# automatrix.net
KiCad netlist of a schematic drawn in EAGLE
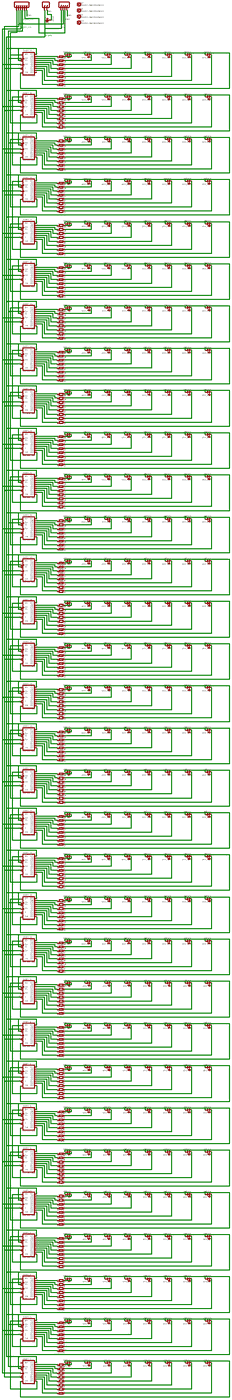
[diagram p0: schematic, sheet 1, overview]
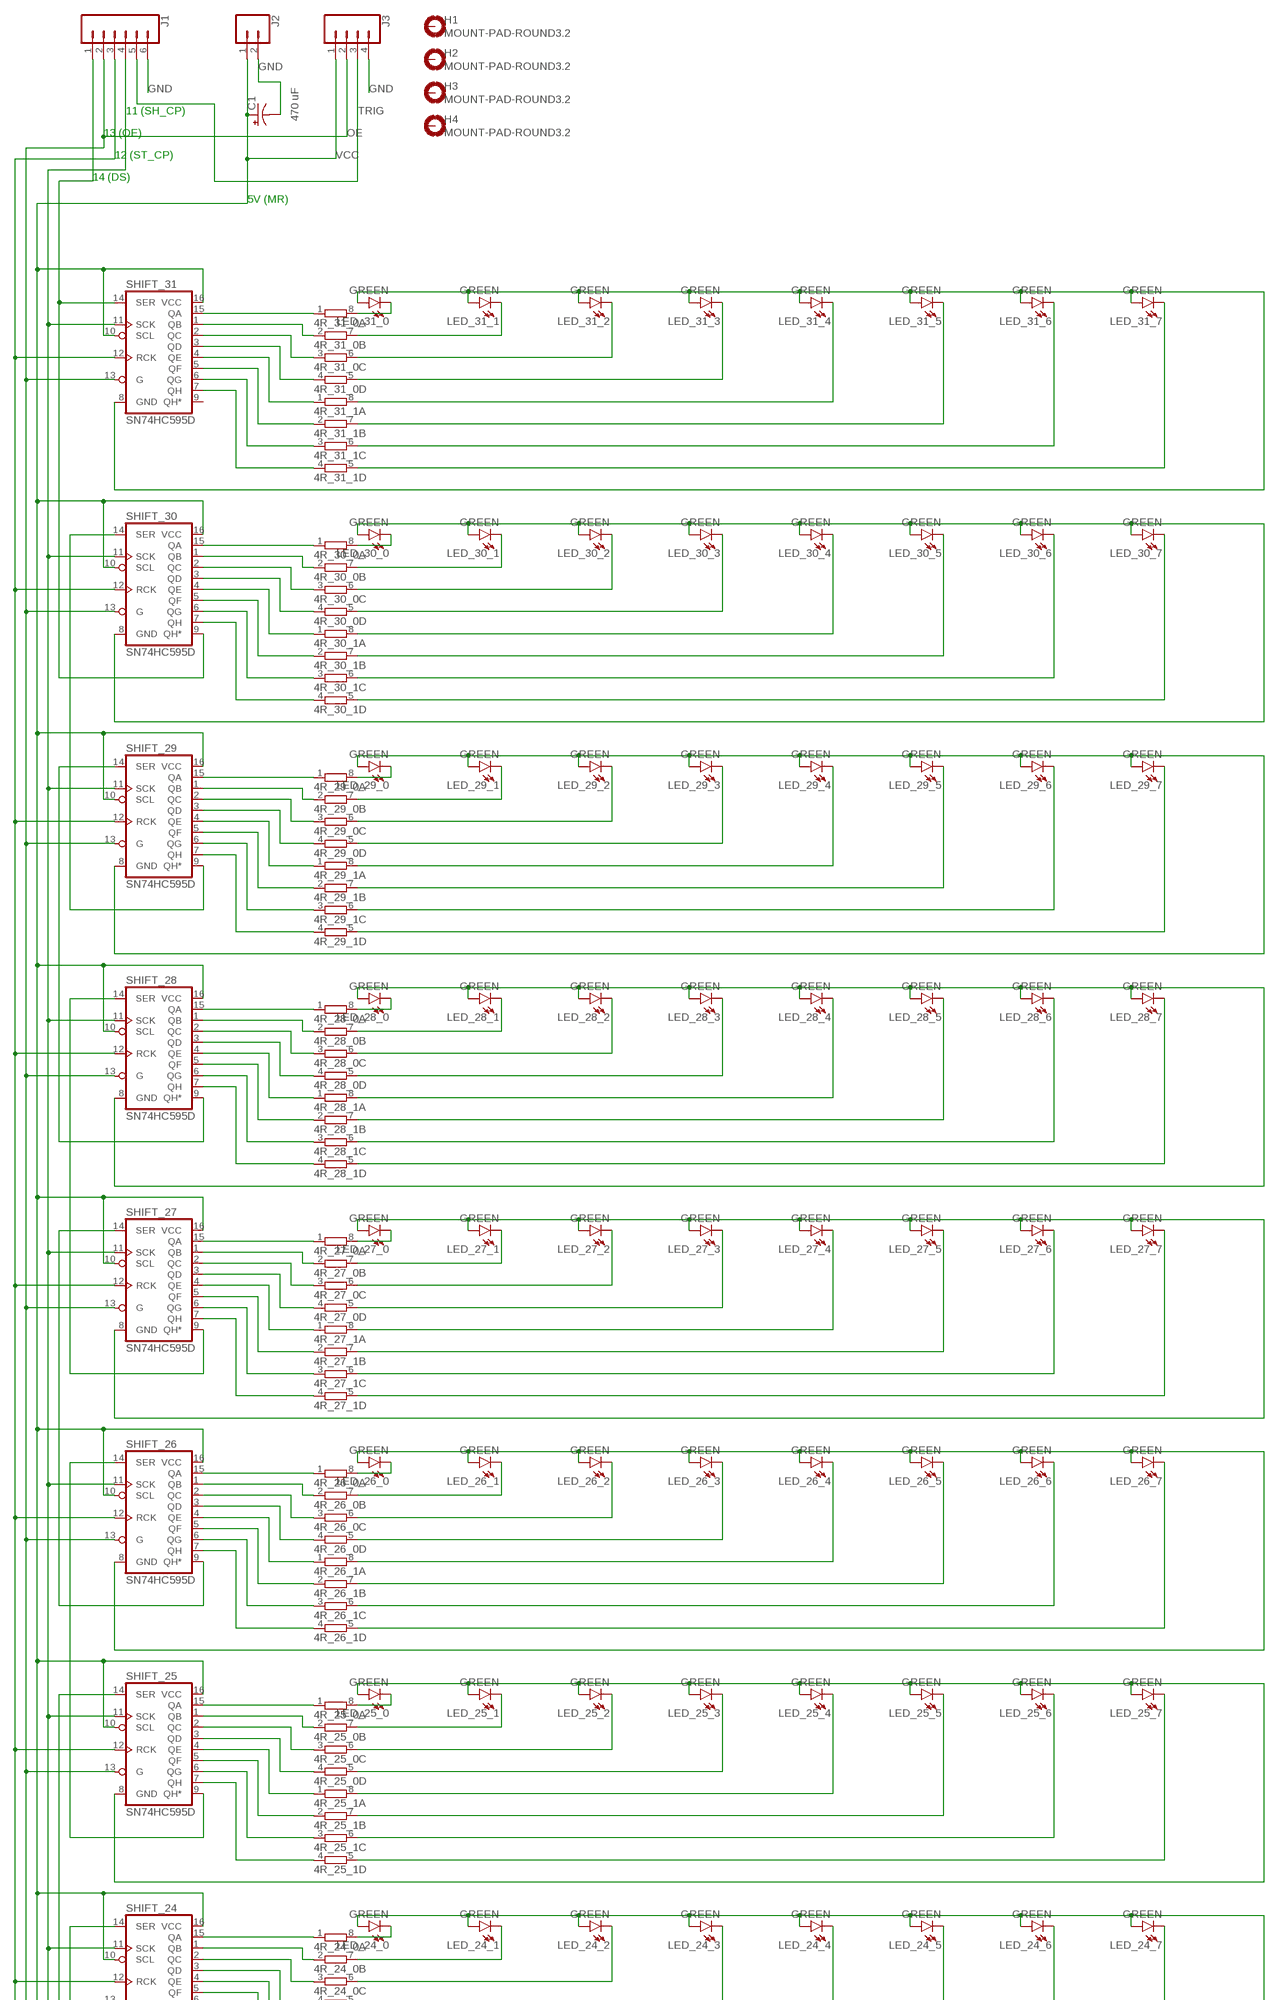
[diagram p1: schematic, sheet 1, part 1 of 4]
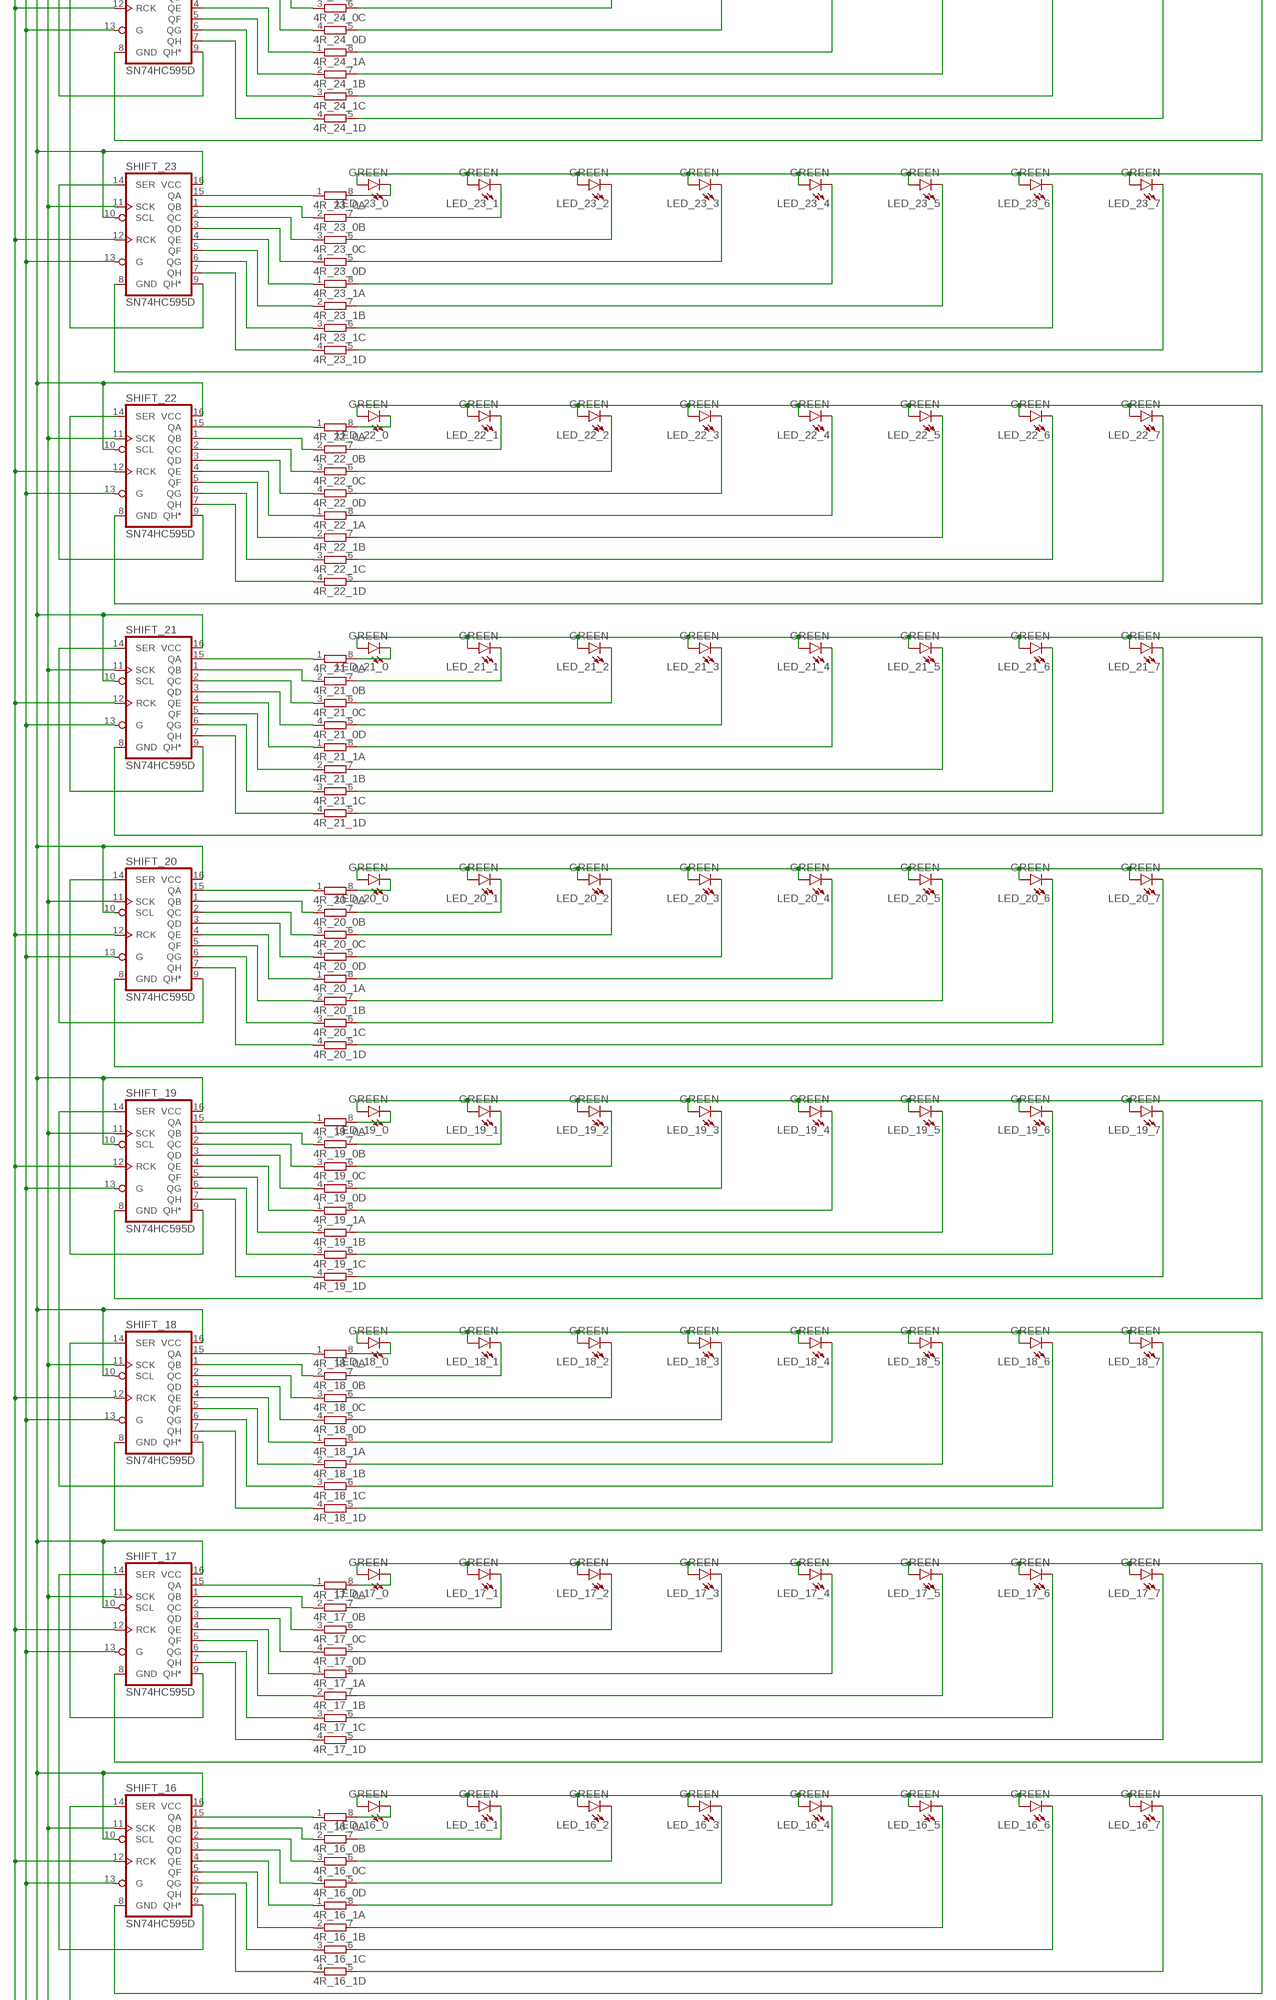
[diagram p2: schematic, sheet 1, part 2 of 4]
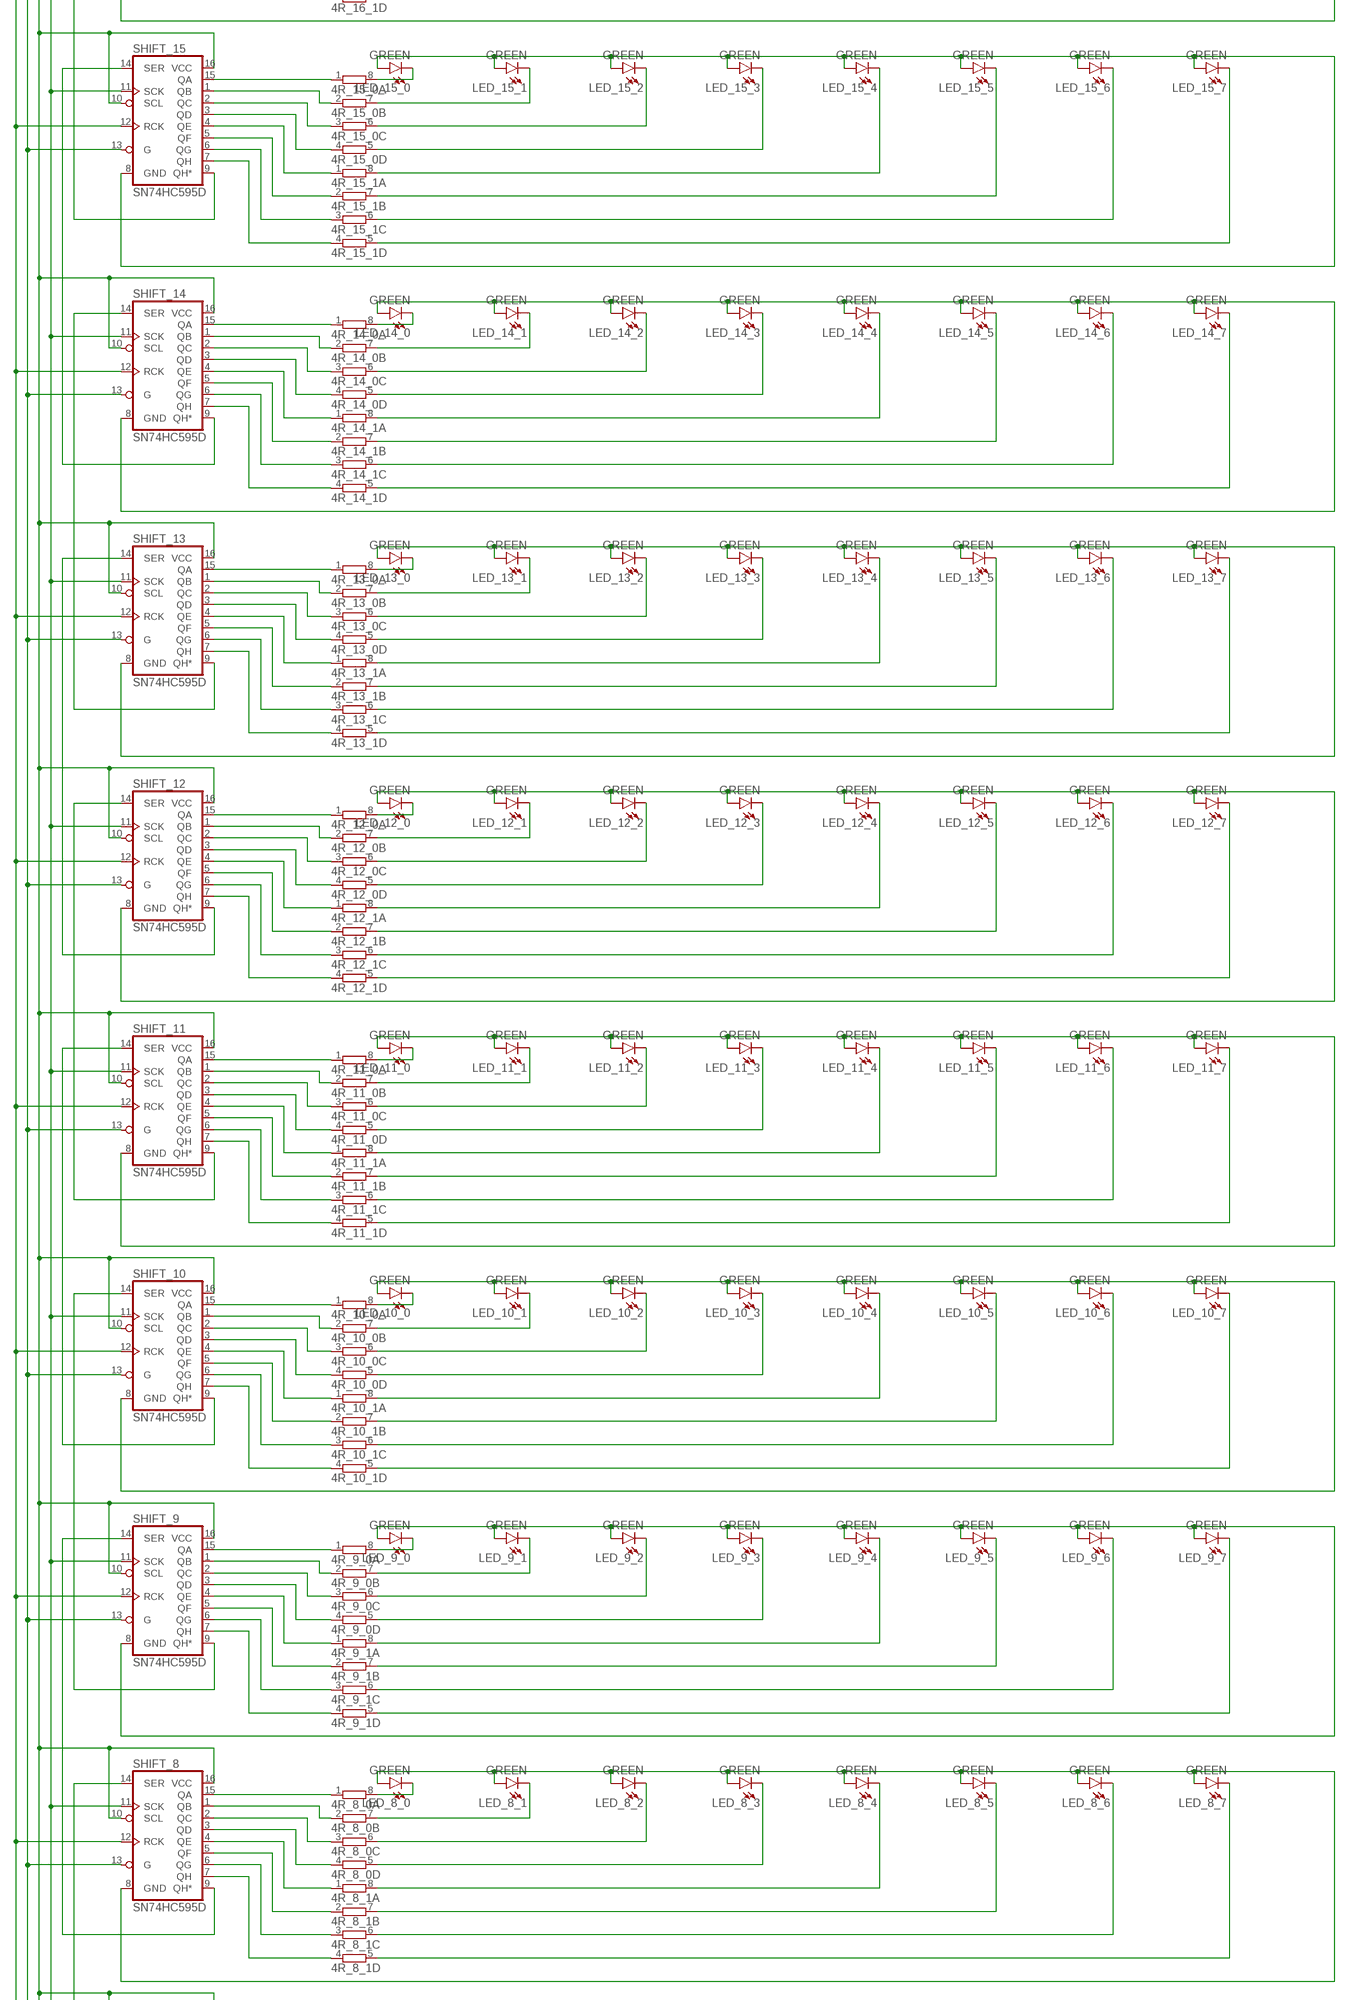
[diagram p3: schematic, sheet 1, part 3 of 4]
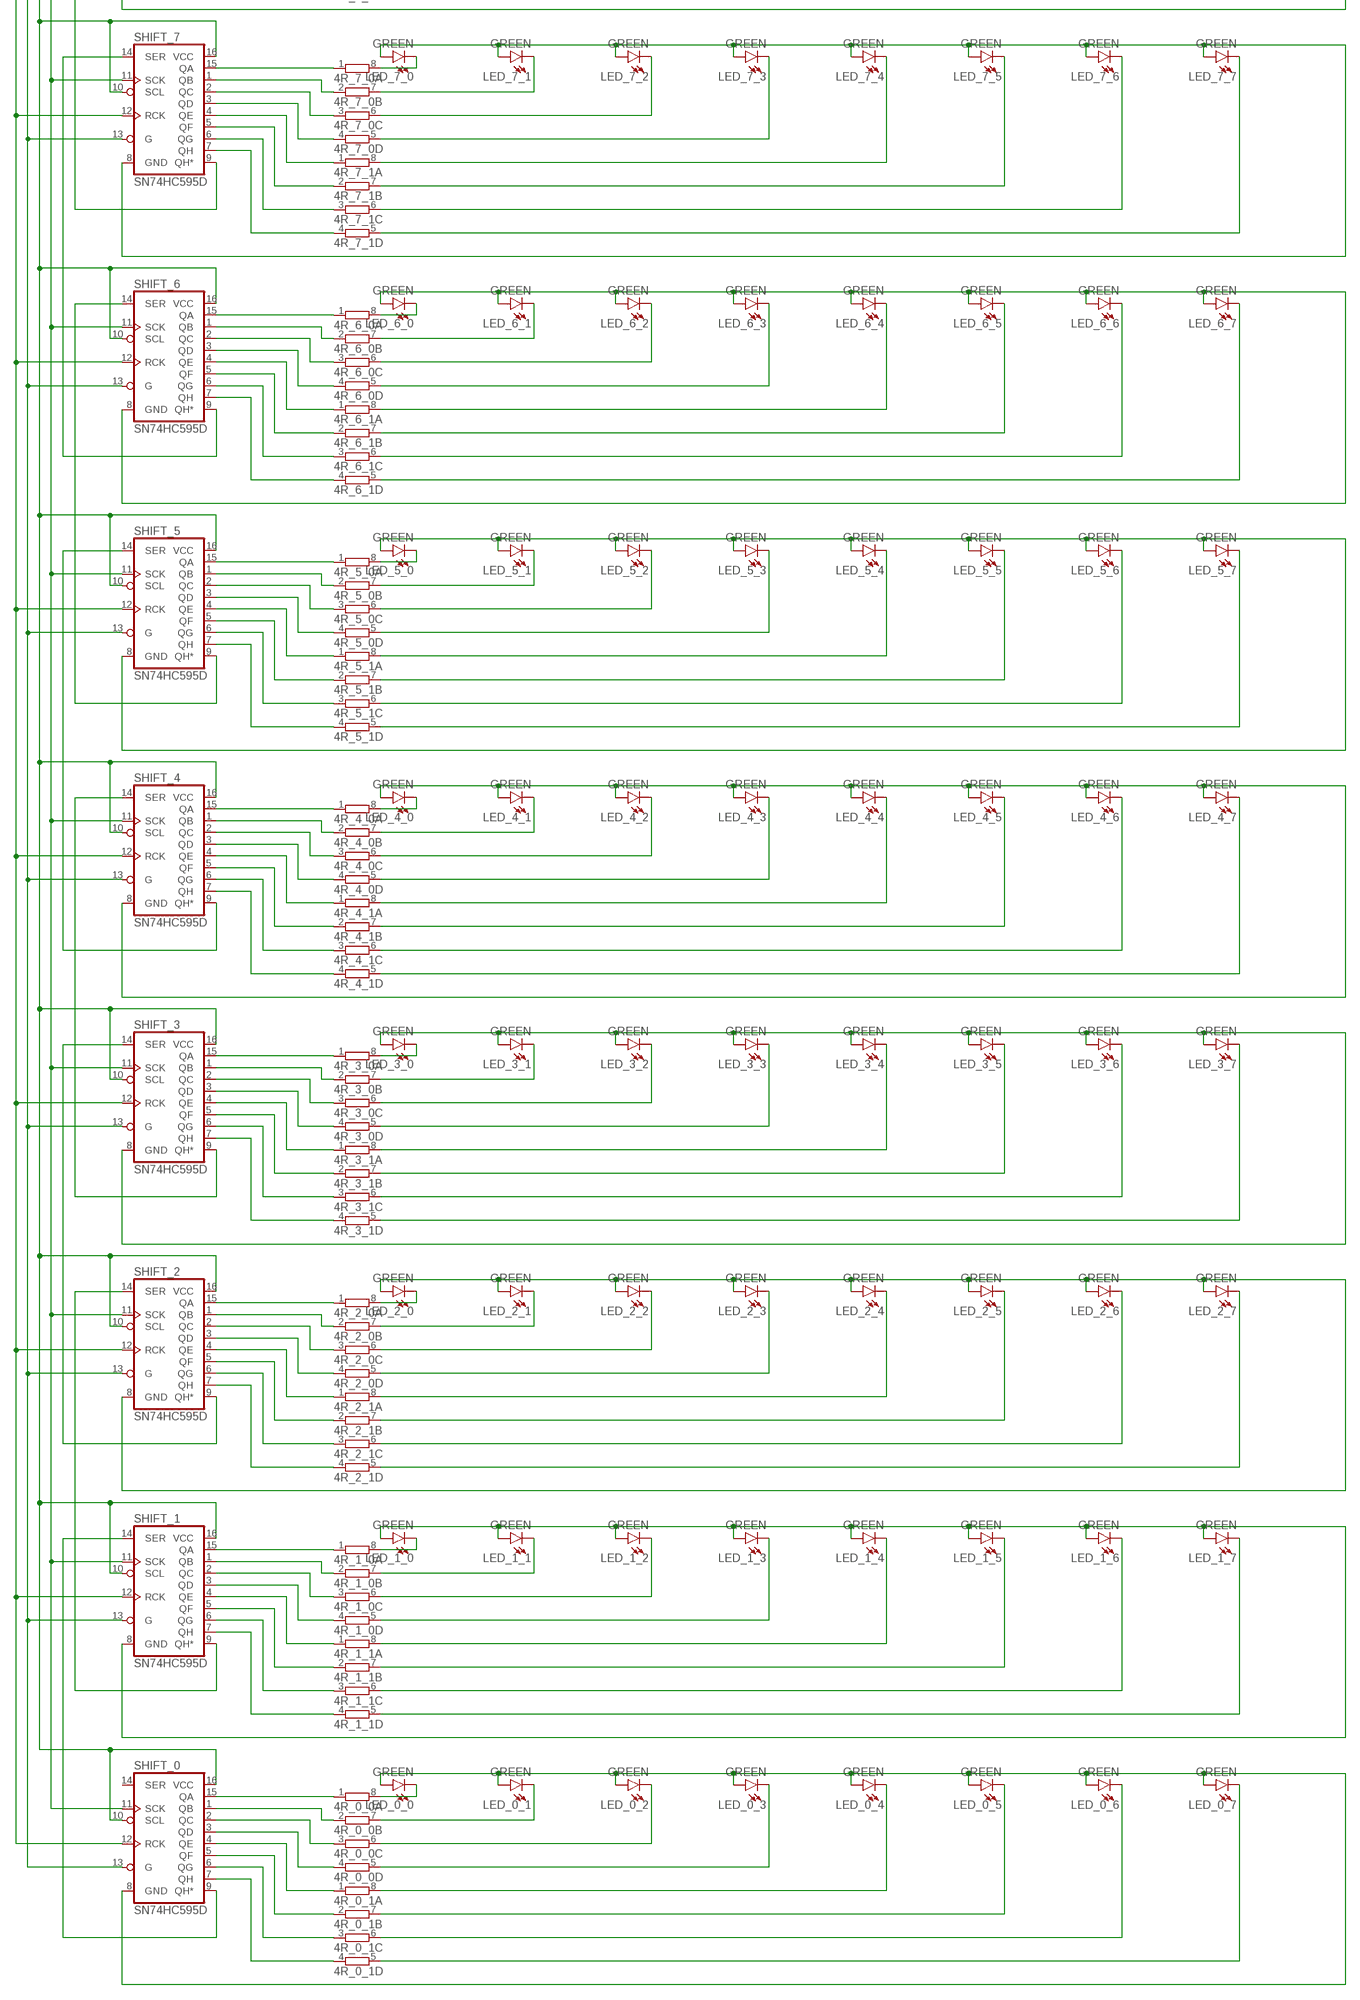
[diagram p4: schematic, sheet 1, part 4 of 4]

(export (version "E")
  (design (tool "Eeschema 10.0.6"))
  (components
    (comp (ref "4R_0_0")
      (value "4R-N0603-ARC")
      (footprint "eagle-import:0603-ARC")
      (libsource (lib "eagle-import") (part "4R-N0603-ARC"))
    )
    (comp (ref "4R_0_1")
      (value "4R-N0603-ARC")
      (footprint "eagle-import:0603-ARC")
      (libsource (lib "eagle-import") (part "4R-N0603-ARC"))
    )
    (comp (ref "4R_1_0")
      (value "4R-N0603-ARC")
      (footprint "eagle-import:0603-ARC")
      (libsource (lib "eagle-import") (part "4R-N0603-ARC"))
    )
    (comp (ref "4R_1_1")
      (value "4R-N0603-ARC")
      (footprint "eagle-import:0603-ARC")
      (libsource (lib "eagle-import") (part "4R-N0603-ARC"))
    )
    (comp (ref "4R_2_0")
      (value "4R-N0603-ARC")
      (footprint "eagle-import:0603-ARC")
      (libsource (lib "eagle-import") (part "4R-N0603-ARC"))
    )
    (comp (ref "4R_2_1")
      (value "4R-N0603-ARC")
      (footprint "eagle-import:0603-ARC")
      (libsource (lib "eagle-import") (part "4R-N0603-ARC"))
    )
    (comp (ref "4R_3_0")
      (value "4R-N0603-ARC")
      (footprint "eagle-import:0603-ARC")
      (libsource (lib "eagle-import") (part "4R-N0603-ARC"))
    )
    (comp (ref "4R_3_1")
      (value "4R-N0603-ARC")
      (footprint "eagle-import:0603-ARC")
      (libsource (lib "eagle-import") (part "4R-N0603-ARC"))
    )
    (comp (ref "4R_4_0")
      (value "4R-N0603-ARC")
      (footprint "eagle-import:0603-ARC")
      (libsource (lib "eagle-import") (part "4R-N0603-ARC"))
    )
    (comp (ref "4R_4_1")
      (value "4R-N0603-ARC")
      (footprint "eagle-import:0603-ARC")
      (libsource (lib "eagle-import") (part "4R-N0603-ARC"))
    )
    (comp (ref "4R_5_0")
      (value "4R-N0603-ARC")
      (footprint "eagle-import:0603-ARC")
      (libsource (lib "eagle-import") (part "4R-N0603-ARC"))
    )
    (comp (ref "4R_5_1")
      (value "4R-N0603-ARC")
      (footprint "eagle-import:0603-ARC")
      (libsource (lib "eagle-import") (part "4R-N0603-ARC"))
    )
    (comp (ref "4R_6_0")
      (value "4R-N0603-ARC")
      (footprint "eagle-import:0603-ARC")
      (libsource (lib "eagle-import") (part "4R-N0603-ARC"))
    )
    (comp (ref "4R_6_1")
      (value "4R-N0603-ARC")
      (footprint "eagle-import:0603-ARC")
      (libsource (lib "eagle-import") (part "4R-N0603-ARC"))
    )
    (comp (ref "4R_7_0")
      (value "4R-N0603-ARC")
      (footprint "eagle-import:0603-ARC")
      (libsource (lib "eagle-import") (part "4R-N0603-ARC"))
    )
    (comp (ref "4R_7_1")
      (value "4R-N0603-ARC")
      (footprint "eagle-import:0603-ARC")
      (libsource (lib "eagle-import") (part "4R-N0603-ARC"))
    )
    (comp (ref "4R_8_0")
      (value "4R-N0603-ARC")
      (footprint "eagle-import:0603-ARC")
      (libsource (lib "eagle-import") (part "4R-N0603-ARC"))
    )
    (comp (ref "4R_8_1")
      (value "4R-N0603-ARC")
      (footprint "eagle-import:0603-ARC")
      (libsource (lib "eagle-import") (part "4R-N0603-ARC"))
    )
    (comp (ref "4R_9_0")
      (value "4R-N0603-ARC")
      (footprint "eagle-import:0603-ARC")
      (libsource (lib "eagle-import") (part "4R-N0603-ARC"))
    )
    (comp (ref "4R_9_1")
      (value "4R-N0603-ARC")
      (footprint "eagle-import:0603-ARC")
      (libsource (lib "eagle-import") (part "4R-N0603-ARC"))
    )
    (comp (ref "4R_10_0")
      (value "4R-N0603-ARC")
      (footprint "eagle-import:0603-ARC")
      (libsource (lib "eagle-import") (part "4R-N0603-ARC"))
    )
    (comp (ref "4R_10_1")
      (value "4R-N0603-ARC")
      (footprint "eagle-import:0603-ARC")
      (libsource (lib "eagle-import") (part "4R-N0603-ARC"))
    )
    (comp (ref "4R_11_0")
      (value "4R-N0603-ARC")
      (footprint "eagle-import:0603-ARC")
      (libsource (lib "eagle-import") (part "4R-N0603-ARC"))
    )
    (comp (ref "4R_11_1")
      (value "4R-N0603-ARC")
      (footprint "eagle-import:0603-ARC")
      (libsource (lib "eagle-import") (part "4R-N0603-ARC"))
    )
    (comp (ref "4R_12_0")
      (value "4R-N0603-ARC")
      (footprint "eagle-import:0603-ARC")
      (libsource (lib "eagle-import") (part "4R-N0603-ARC"))
    )
    (comp (ref "4R_12_1")
      (value "4R-N0603-ARC")
      (footprint "eagle-import:0603-ARC")
      (libsource (lib "eagle-import") (part "4R-N0603-ARC"))
    )
    (comp (ref "4R_13_0")
      (value "4R-N0603-ARC")
      (footprint "eagle-import:0603-ARC")
      (libsource (lib "eagle-import") (part "4R-N0603-ARC"))
    )
    (comp (ref "4R_13_1")
      (value "4R-N0603-ARC")
      (footprint "eagle-import:0603-ARC")
      (libsource (lib "eagle-import") (part "4R-N0603-ARC"))
    )
    (comp (ref "4R_14_0")
      (value "4R-N0603-ARC")
      (footprint "eagle-import:0603-ARC")
      (libsource (lib "eagle-import") (part "4R-N0603-ARC"))
    )
    (comp (ref "4R_14_1")
      (value "4R-N0603-ARC")
      (footprint "eagle-import:0603-ARC")
      (libsource (lib "eagle-import") (part "4R-N0603-ARC"))
    )
    (comp (ref "4R_15_0")
      (value "4R-N0603-ARC")
      (footprint "eagle-import:0603-ARC")
      (libsource (lib "eagle-import") (part "4R-N0603-ARC"))
    )
    (comp (ref "4R_15_1")
      (value "4R-N0603-ARC")
      (footprint "eagle-import:0603-ARC")
      (libsource (lib "eagle-import") (part "4R-N0603-ARC"))
    )
    (comp (ref "4R_16_0")
      (value "4R-N0603-ARC")
      (footprint "eagle-import:0603-ARC")
      (libsource (lib "eagle-import") (part "4R-N0603-ARC"))
    )
    (comp (ref "4R_16_1")
      (value "4R-N0603-ARC")
      (footprint "eagle-import:0603-ARC")
      (libsource (lib "eagle-import") (part "4R-N0603-ARC"))
    )
    (comp (ref "4R_17_0")
      (value "4R-N0603-ARC")
      (footprint "eagle-import:0603-ARC")
      (libsource (lib "eagle-import") (part "4R-N0603-ARC"))
    )
    (comp (ref "4R_17_1")
      (value "4R-N0603-ARC")
      (footprint "eagle-import:0603-ARC")
      (libsource (lib "eagle-import") (part "4R-N0603-ARC"))
    )
    (comp (ref "4R_18_0")
      (value "4R-N0603-ARC")
      (footprint "eagle-import:0603-ARC")
      (libsource (lib "eagle-import") (part "4R-N0603-ARC"))
    )
    (comp (ref "4R_18_1")
      (value "4R-N0603-ARC")
      (footprint "eagle-import:0603-ARC")
      (libsource (lib "eagle-import") (part "4R-N0603-ARC"))
    )
    (comp (ref "4R_19_0")
      (value "4R-N0603-ARC")
      (footprint "eagle-import:0603-ARC")
      (libsource (lib "eagle-import") (part "4R-N0603-ARC"))
    )
    (comp (ref "4R_19_1")
      (value "4R-N0603-ARC")
      (footprint "eagle-import:0603-ARC")
      (libsource (lib "eagle-import") (part "4R-N0603-ARC"))
    )
    (comp (ref "4R_20_0")
      (value "4R-N0603-ARC")
      (footprint "eagle-import:0603-ARC")
      (libsource (lib "eagle-import") (part "4R-N0603-ARC"))
    )
    (comp (ref "4R_20_1")
      (value "4R-N0603-ARC")
      (footprint "eagle-import:0603-ARC")
      (libsource (lib "eagle-import") (part "4R-N0603-ARC"))
    )
    (comp (ref "4R_21_0")
      (value "4R-N0603-ARC")
      (footprint "eagle-import:0603-ARC")
      (libsource (lib "eagle-import") (part "4R-N0603-ARC"))
    )
    (comp (ref "4R_21_1")
      (value "4R-N0603-ARC")
      (footprint "eagle-import:0603-ARC")
      (libsource (lib "eagle-import") (part "4R-N0603-ARC"))
    )
    (comp (ref "4R_22_0")
      (value "4R-N0603-ARC")
      (footprint "eagle-import:0603-ARC")
      (libsource (lib "eagle-import") (part "4R-N0603-ARC"))
    )
    (comp (ref "4R_22_1")
      (value "4R-N0603-ARC")
      (footprint "eagle-import:0603-ARC")
      (libsource (lib "eagle-import") (part "4R-N0603-ARC"))
    )
    (comp (ref "4R_23_0")
      (value "4R-N0603-ARC")
      (footprint "eagle-import:0603-ARC")
      (libsource (lib "eagle-import") (part "4R-N0603-ARC"))
    )
    (comp (ref "4R_23_1")
      (value "4R-N0603-ARC")
      (footprint "eagle-import:0603-ARC")
      (libsource (lib "eagle-import") (part "4R-N0603-ARC"))
    )
    (comp (ref "4R_24_0")
      (value "4R-N0603-ARC")
      (footprint "eagle-import:0603-ARC")
      (libsource (lib "eagle-import") (part "4R-N0603-ARC"))
    )
    (comp (ref "4R_24_1")
      (value "4R-N0603-ARC")
      (footprint "eagle-import:0603-ARC")
      (libsource (lib "eagle-import") (part "4R-N0603-ARC"))
    )
    (comp (ref "4R_25_0")
      (value "4R-N0603-ARC")
      (footprint "eagle-import:0603-ARC")
      (libsource (lib "eagle-import") (part "4R-N0603-ARC"))
    )
    (comp (ref "4R_25_1")
      (value "4R-N0603-ARC")
      (footprint "eagle-import:0603-ARC")
      (libsource (lib "eagle-import") (part "4R-N0603-ARC"))
    )
    (comp (ref "4R_26_0")
      (value "4R-N0603-ARC")
      (footprint "eagle-import:0603-ARC")
      (libsource (lib "eagle-import") (part "4R-N0603-ARC"))
    )
    (comp (ref "4R_26_1")
      (value "4R-N0603-ARC")
      (footprint "eagle-import:0603-ARC")
      (libsource (lib "eagle-import") (part "4R-N0603-ARC"))
    )
    (comp (ref "4R_27_0")
      (value "4R-N0603-ARC")
      (footprint "eagle-import:0603-ARC")
      (libsource (lib "eagle-import") (part "4R-N0603-ARC"))
    )
    (comp (ref "4R_27_1")
      (value "4R-N0603-ARC")
      (footprint "eagle-import:0603-ARC")
      (libsource (lib "eagle-import") (part "4R-N0603-ARC"))
    )
    (comp (ref "4R_28_0")
      (value "4R-N0603-ARC")
      (footprint "eagle-import:0603-ARC")
      (libsource (lib "eagle-import") (part "4R-N0603-ARC"))
    )
    (comp (ref "4R_28_1")
      (value "4R-N0603-ARC")
      (footprint "eagle-import:0603-ARC")
      (libsource (lib "eagle-import") (part "4R-N0603-ARC"))
    )
    (comp (ref "4R_29_0")
      (value "4R-N0603-ARC")
      (footprint "eagle-import:0603-ARC")
      (libsource (lib "eagle-import") (part "4R-N0603-ARC"))
    )
    (comp (ref "4R_29_1")
      (value "4R-N0603-ARC")
      (footprint "eagle-import:0603-ARC")
      (libsource (lib "eagle-import") (part "4R-N0603-ARC"))
    )
    (comp (ref "4R_30_0")
      (value "4R-N0603-ARC")
      (footprint "eagle-import:0603-ARC")
      (libsource (lib "eagle-import") (part "4R-N0603-ARC"))
    )
    (comp (ref "4R_30_1")
      (value "4R-N0603-ARC")
      (footprint "eagle-import:0603-ARC")
      (libsource (lib "eagle-import") (part "4R-N0603-ARC"))
    )
    (comp (ref "4R_31_0")
      (value "4R-N0603-ARC")
      (footprint "eagle-import:0603-ARC")
      (libsource (lib "eagle-import") (part "4R-N0603-ARC"))
    )
    (comp (ref "4R_31_1")
      (value "4R-N0603-ARC")
      (footprint "eagle-import:0603-ARC")
      (libsource (lib "eagle-import") (part "4R-N0603-ARC"))
    )
    (comp (ref "C1")
      (value "470 uF")
      (footprint "eagle-import:CPOL-RADIAL-5MM-10MM")
      (libsource (lib "eagle-import") (part "1000UF-RADIAL-5MM-25V-20%"))
    )
    (comp (ref "H1")
      (value "MOUNT-PAD-ROUND3.2")
      (footprint "eagle-import:3,2-PAD")
      (libsource (lib "eagle-import") (part "MOUNT-PAD-ROUND3.2"))
    )
    (comp (ref "H2")
      (value "MOUNT-PAD-ROUND3.2")
      (footprint "eagle-import:3,2-PAD")
      (libsource (lib "eagle-import") (part "MOUNT-PAD-ROUND3.2"))
    )
    (comp (ref "H3")
      (value "MOUNT-PAD-ROUND3.2")
      (footprint "eagle-import:3,2-PAD")
      (libsource (lib "eagle-import") (part "MOUNT-PAD-ROUND3.2"))
    )
    (comp (ref "H4")
      (value "MOUNT-PAD-ROUND3.2")
      (footprint "eagle-import:3,2-PAD")
      (libsource (lib "eagle-import") (part "MOUNT-PAD-ROUND3.2"))
    )
    (comp (ref "J1")
      (value "CONN_06NO_SILK_FEMALE_PTH")
      (footprint "eagle-import:1X06_NO_SILK")
      (libsource (lib "eagle-import") (part "CONN_06NO_SILK_FEMALE_PTH"))
    )
    (comp (ref "J2")
      (value "CONN_021X02_NO_SILK")
      (footprint "eagle-import:1X02_NO_SILK")
      (libsource (lib "eagle-import") (part "CONN_021X02_NO_SILK"))
    )
    (comp (ref "J3")
      (value "CONN_041X04_NO_SILK")
      (footprint "eagle-import:1X04_NO_SILK")
      (libsource (lib "eagle-import") (part "CONN_041X04_NO_SILK"))
    )
    (comp (ref "LED_0_0")
      (value "GREEN")
      (footprint "eagle-import:LED-0603")
      (libsource (lib "eagle-import") (part "LED-GREEN0603"))
    )
    (comp (ref "LED_0_1")
      (value "GREEN")
      (footprint "eagle-import:LED-0603")
      (libsource (lib "eagle-import") (part "LED-GREEN0603"))
    )
    (comp (ref "LED_0_2")
      (value "GREEN")
      (footprint "eagle-import:LED-0603")
      (libsource (lib "eagle-import") (part "LED-GREEN0603"))
    )
    (comp (ref "LED_0_3")
      (value "GREEN")
      (footprint "eagle-import:LED-0603")
      (libsource (lib "eagle-import") (part "LED-GREEN0603"))
    )
    (comp (ref "LED_0_4")
      (value "GREEN")
      (footprint "eagle-import:LED-0603")
      (libsource (lib "eagle-import") (part "LED-GREEN0603"))
    )
    (comp (ref "LED_0_5")
      (value "GREEN")
      (footprint "eagle-import:LED-0603")
      (libsource (lib "eagle-import") (part "LED-GREEN0603"))
    )
    (comp (ref "LED_0_6")
      (value "GREEN")
      (footprint "eagle-import:LED-0603")
      (libsource (lib "eagle-import") (part "LED-GREEN0603"))
    )
    (comp (ref "LED_0_7")
      (value "GREEN")
      (footprint "eagle-import:LED-0603")
      (libsource (lib "eagle-import") (part "LED-GREEN0603"))
    )
    (comp (ref "LED_1_0")
      (value "GREEN")
      (footprint "eagle-import:LED-0603")
      (libsource (lib "eagle-import") (part "LED-GREEN0603"))
    )
    (comp (ref "LED_1_1")
      (value "GREEN")
      (footprint "eagle-import:LED-0603")
      (libsource (lib "eagle-import") (part "LED-GREEN0603"))
    )
    (comp (ref "LED_1_2")
      (value "GREEN")
      (footprint "eagle-import:LED-0603")
      (libsource (lib "eagle-import") (part "LED-GREEN0603"))
    )
    (comp (ref "LED_1_3")
      (value "GREEN")
      (footprint "eagle-import:LED-0603")
      (libsource (lib "eagle-import") (part "LED-GREEN0603"))
    )
    (comp (ref "LED_1_4")
      (value "GREEN")
      (footprint "eagle-import:LED-0603")
      (libsource (lib "eagle-import") (part "LED-GREEN0603"))
    )
    (comp (ref "LED_1_5")
      (value "GREEN")
      (footprint "eagle-import:LED-0603")
      (libsource (lib "eagle-import") (part "LED-GREEN0603"))
    )
    (comp (ref "LED_1_6")
      (value "GREEN")
      (footprint "eagle-import:LED-0603")
      (libsource (lib "eagle-import") (part "LED-GREEN0603"))
    )
    (comp (ref "LED_1_7")
      (value "GREEN")
      (footprint "eagle-import:LED-0603")
      (libsource (lib "eagle-import") (part "LED-GREEN0603"))
    )
    (comp (ref "LED_2_0")
      (value "GREEN")
      (footprint "eagle-import:LED-0603")
      (libsource (lib "eagle-import") (part "LED-GREEN0603"))
    )
    (comp (ref "LED_2_1")
      (value "GREEN")
      (footprint "eagle-import:LED-0603")
      (libsource (lib "eagle-import") (part "LED-GREEN0603"))
    )
    (comp (ref "LED_2_2")
      (value "GREEN")
      (footprint "eagle-import:LED-0603")
      (libsource (lib "eagle-import") (part "LED-GREEN0603"))
    )
    (comp (ref "LED_2_3")
      (value "GREEN")
      (footprint "eagle-import:LED-0603")
      (libsource (lib "eagle-import") (part "LED-GREEN0603"))
    )
    (comp (ref "LED_2_4")
      (value "GREEN")
      (footprint "eagle-import:LED-0603")
      (libsource (lib "eagle-import") (part "LED-GREEN0603"))
    )
    (comp (ref "LED_2_5")
      (value "GREEN")
      (footprint "eagle-import:LED-0603")
      (libsource (lib "eagle-import") (part "LED-GREEN0603"))
    )
    (comp (ref "LED_2_6")
      (value "GREEN")
      (footprint "eagle-import:LED-0603")
      (libsource (lib "eagle-import") (part "LED-GREEN0603"))
    )
    (comp (ref "LED_2_7")
      (value "GREEN")
      (footprint "eagle-import:LED-0603")
      (libsource (lib "eagle-import") (part "LED-GREEN0603"))
    )
    (comp (ref "LED_3_0")
      (value "GREEN")
      (footprint "eagle-import:LED-0603")
      (libsource (lib "eagle-import") (part "LED-GREEN0603"))
    )
    (comp (ref "LED_3_1")
      (value "GREEN")
      (footprint "eagle-import:LED-0603")
      (libsource (lib "eagle-import") (part "LED-GREEN0603"))
    )
    (comp (ref "LED_3_2")
      (value "GREEN")
      (footprint "eagle-import:LED-0603")
      (libsource (lib "eagle-import") (part "LED-GREEN0603"))
    )
    (comp (ref "LED_3_3")
      (value "GREEN")
      (footprint "eagle-import:LED-0603")
      (libsource (lib "eagle-import") (part "LED-GREEN0603"))
    )
    (comp (ref "LED_3_4")
      (value "GREEN")
      (footprint "eagle-import:LED-0603")
      (libsource (lib "eagle-import") (part "LED-GREEN0603"))
    )
    (comp (ref "LED_3_5")
      (value "GREEN")
      (footprint "eagle-import:LED-0603")
      (libsource (lib "eagle-import") (part "LED-GREEN0603"))
    )
    (comp (ref "LED_3_6")
      (value "GREEN")
      (footprint "eagle-import:LED-0603")
      (libsource (lib "eagle-import") (part "LED-GREEN0603"))
    )
    (comp (ref "LED_3_7")
      (value "GREEN")
      (footprint "eagle-import:LED-0603")
      (libsource (lib "eagle-import") (part "LED-GREEN0603"))
    )
    (comp (ref "LED_4_0")
      (value "GREEN")
      (footprint "eagle-import:LED-0603")
      (libsource (lib "eagle-import") (part "LED-GREEN0603"))
    )
    (comp (ref "LED_4_1")
      (value "GREEN")
      (footprint "eagle-import:LED-0603")
      (libsource (lib "eagle-import") (part "LED-GREEN0603"))
    )
    (comp (ref "LED_4_2")
      (value "GREEN")
      (footprint "eagle-import:LED-0603")
      (libsource (lib "eagle-import") (part "LED-GREEN0603"))
    )
    (comp (ref "LED_4_3")
      (value "GREEN")
      (footprint "eagle-import:LED-0603")
      (libsource (lib "eagle-import") (part "LED-GREEN0603"))
    )
    (comp (ref "LED_4_4")
      (value "GREEN")
      (footprint "eagle-import:LED-0603")
      (libsource (lib "eagle-import") (part "LED-GREEN0603"))
    )
    (comp (ref "LED_4_5")
      (value "GREEN")
      (footprint "eagle-import:LED-0603")
      (libsource (lib "eagle-import") (part "LED-GREEN0603"))
    )
    (comp (ref "LED_4_6")
      (value "GREEN")
      (footprint "eagle-import:LED-0603")
      (libsource (lib "eagle-import") (part "LED-GREEN0603"))
    )
    (comp (ref "LED_4_7")
      (value "GREEN")
      (footprint "eagle-import:LED-0603")
      (libsource (lib "eagle-import") (part "LED-GREEN0603"))
    )
    (comp (ref "LED_5_0")
      (value "GREEN")
      (footprint "eagle-import:LED-0603")
      (libsource (lib "eagle-import") (part "LED-GREEN0603"))
    )
    (comp (ref "LED_5_1")
      (value "GREEN")
      (footprint "eagle-import:LED-0603")
      (libsource (lib "eagle-import") (part "LED-GREEN0603"))
    )
    (comp (ref "LED_5_2")
      (value "GREEN")
      (footprint "eagle-import:LED-0603")
      (libsource (lib "eagle-import") (part "LED-GREEN0603"))
    )
    (comp (ref "LED_5_3")
      (value "GREEN")
      (footprint "eagle-import:LED-0603")
      (libsource (lib "eagle-import") (part "LED-GREEN0603"))
    )
    (comp (ref "LED_5_4")
      (value "GREEN")
      (footprint "eagle-import:LED-0603")
      (libsource (lib "eagle-import") (part "LED-GREEN0603"))
    )
    (comp (ref "LED_5_5")
      (value "GREEN")
      (footprint "eagle-import:LED-0603")
      (libsource (lib "eagle-import") (part "LED-GREEN0603"))
    )
    (comp (ref "LED_5_6")
      (value "GREEN")
      (footprint "eagle-import:LED-0603")
      (libsource (lib "eagle-import") (part "LED-GREEN0603"))
    )
    (comp (ref "LED_5_7")
      (value "GREEN")
      (footprint "eagle-import:LED-0603")
      (libsource (lib "eagle-import") (part "LED-GREEN0603"))
    )
    (comp (ref "LED_6_0")
      (value "GREEN")
      (footprint "eagle-import:LED-0603")
      (libsource (lib "eagle-import") (part "LED-GREEN0603"))
    )
    (comp (ref "LED_6_1")
      (value "GREEN")
      (footprint "eagle-import:LED-0603")
      (libsource (lib "eagle-import") (part "LED-GREEN0603"))
    )
    (comp (ref "LED_6_2")
      (value "GREEN")
      (footprint "eagle-import:LED-0603")
      (libsource (lib "eagle-import") (part "LED-GREEN0603"))
    )
    (comp (ref "LED_6_3")
      (value "GREEN")
      (footprint "eagle-import:LED-0603")
      (libsource (lib "eagle-import") (part "LED-GREEN0603"))
    )
    (comp (ref "LED_6_4")
      (value "GREEN")
      (footprint "eagle-import:LED-0603")
      (libsource (lib "eagle-import") (part "LED-GREEN0603"))
    )
    (comp (ref "LED_6_5")
      (value "GREEN")
      (footprint "eagle-import:LED-0603")
      (libsource (lib "eagle-import") (part "LED-GREEN0603"))
    )
    (comp (ref "LED_6_6")
      (value "GREEN")
      (footprint "eagle-import:LED-0603")
      (libsource (lib "eagle-import") (part "LED-GREEN0603"))
    )
    (comp (ref "LED_6_7")
      (value "GREEN")
      (footprint "eagle-import:LED-0603")
      (libsource (lib "eagle-import") (part "LED-GREEN0603"))
    )
    (comp (ref "LED_7_0")
      (value "GREEN")
      (footprint "eagle-import:LED-0603")
      (libsource (lib "eagle-import") (part "LED-GREEN0603"))
    )
    (comp (ref "LED_7_1")
      (value "GREEN")
      (footprint "eagle-import:LED-0603")
      (libsource (lib "eagle-import") (part "LED-GREEN0603"))
    )
    (comp (ref "LED_7_2")
      (value "GREEN")
      (footprint "eagle-import:LED-0603")
      (libsource (lib "eagle-import") (part "LED-GREEN0603"))
    )
    (comp (ref "LED_7_3")
      (value "GREEN")
      (footprint "eagle-import:LED-0603")
      (libsource (lib "eagle-import") (part "LED-GREEN0603"))
    )
    (comp (ref "LED_7_4")
      (value "GREEN")
      (footprint "eagle-import:LED-0603")
      (libsource (lib "eagle-import") (part "LED-GREEN0603"))
    )
    (comp (ref "LED_7_5")
      (value "GREEN")
      (footprint "eagle-import:LED-0603")
      (libsource (lib "eagle-import") (part "LED-GREEN0603"))
    )
    (comp (ref "LED_7_6")
      (value "GREEN")
      (footprint "eagle-import:LED-0603")
      (libsource (lib "eagle-import") (part "LED-GREEN0603"))
    )
    (comp (ref "LED_7_7")
      (value "GREEN")
      (footprint "eagle-import:LED-0603")
      (libsource (lib "eagle-import") (part "LED-GREEN0603"))
    )
    (comp (ref "LED_8_0")
      (value "GREEN")
      (footprint "eagle-import:LED-0603")
      (libsource (lib "eagle-import") (part "LED-GREEN0603"))
    )
    (comp (ref "LED_8_1")
      (value "GREEN")
      (footprint "eagle-import:LED-0603")
      (libsource (lib "eagle-import") (part "LED-GREEN0603"))
    )
    (comp (ref "LED_8_2")
      (value "GREEN")
      (footprint "eagle-import:LED-0603")
      (libsource (lib "eagle-import") (part "LED-GREEN0603"))
    )
    (comp (ref "LED_8_3")
      (value "GREEN")
      (footprint "eagle-import:LED-0603")
      (libsource (lib "eagle-import") (part "LED-GREEN0603"))
    )
    (comp (ref "LED_8_4")
      (value "GREEN")
      (footprint "eagle-import:LED-0603")
      (libsource (lib "eagle-import") (part "LED-GREEN0603"))
    )
    (comp (ref "LED_8_5")
      (value "GREEN")
      (footprint "eagle-import:LED-0603")
      (libsource (lib "eagle-import") (part "LED-GREEN0603"))
    )
    (comp (ref "LED_8_6")
      (value "GREEN")
      (footprint "eagle-import:LED-0603")
      (libsource (lib "eagle-import") (part "LED-GREEN0603"))
    )
    (comp (ref "LED_8_7")
      (value "GREEN")
      (footprint "eagle-import:LED-0603")
      (libsource (lib "eagle-import") (part "LED-GREEN0603"))
    )
    (comp (ref "LED_9_0")
      (value "GREEN")
      (footprint "eagle-import:LED-0603")
      (libsource (lib "eagle-import") (part "LED-GREEN0603"))
    )
    (comp (ref "LED_9_1")
      (value "GREEN")
      (footprint "eagle-import:LED-0603")
      (libsource (lib "eagle-import") (part "LED-GREEN0603"))
    )
    (comp (ref "LED_9_2")
      (value "GREEN")
      (footprint "eagle-import:LED-0603")
      (libsource (lib "eagle-import") (part "LED-GREEN0603"))
    )
    (comp (ref "LED_9_3")
      (value "GREEN")
      (footprint "eagle-import:LED-0603")
      (libsource (lib "eagle-import") (part "LED-GREEN0603"))
    )
    (comp (ref "LED_9_4")
      (value "GREEN")
      (footprint "eagle-import:LED-0603")
      (libsource (lib "eagle-import") (part "LED-GREEN0603"))
    )
    (comp (ref "LED_9_5")
      (value "GREEN")
      (footprint "eagle-import:LED-0603")
      (libsource (lib "eagle-import") (part "LED-GREEN0603"))
    )
    (comp (ref "LED_9_6")
      (value "GREEN")
      (footprint "eagle-import:LED-0603")
      (libsource (lib "eagle-import") (part "LED-GREEN0603"))
    )
    (comp (ref "LED_9_7")
      (value "GREEN")
      (footprint "eagle-import:LED-0603")
      (libsource (lib "eagle-import") (part "LED-GREEN0603"))
    )
    (comp (ref "LED_10_0")
      (value "GREEN")
      (footprint "eagle-import:LED-0603")
      (libsource (lib "eagle-import") (part "LED-GREEN0603"))
    )
    (comp (ref "LED_10_1")
      (value "GREEN")
      (footprint "eagle-import:LED-0603")
      (libsource (lib "eagle-import") (part "LED-GREEN0603"))
    )
    (comp (ref "LED_10_2")
      (value "GREEN")
      (footprint "eagle-import:LED-0603")
      (libsource (lib "eagle-import") (part "LED-GREEN0603"))
    )
    (comp (ref "LED_10_3")
      (value "GREEN")
      (footprint "eagle-import:LED-0603")
      (libsource (lib "eagle-import") (part "LED-GREEN0603"))
    )
    (comp (ref "LED_10_4")
      (value "GREEN")
      (footprint "eagle-import:LED-0603")
      (libsource (lib "eagle-import") (part "LED-GREEN0603"))
    )
    (comp (ref "LED_10_5")
      (value "GREEN")
      (footprint "eagle-import:LED-0603")
      (libsource (lib "eagle-import") (part "LED-GREEN0603"))
    )
    (comp (ref "LED_10_6")
      (value "GREEN")
      (footprint "eagle-import:LED-0603")
      (libsource (lib "eagle-import") (part "LED-GREEN0603"))
    )
    (comp (ref "LED_10_7")
      (value "GREEN")
      (footprint "eagle-import:LED-0603")
      (libsource (lib "eagle-import") (part "LED-GREEN0603"))
    )
    (comp (ref "LED_11_0")
      (value "GREEN")
      (footprint "eagle-import:LED-0603")
      (libsource (lib "eagle-import") (part "LED-GREEN0603"))
    )
    (comp (ref "LED_11_1")
      (value "GREEN")
      (footprint "eagle-import:LED-0603")
      (libsource (lib "eagle-import") (part "LED-GREEN0603"))
    )
    (comp (ref "LED_11_2")
      (value "GREEN")
      (footprint "eagle-import:LED-0603")
      (libsource (lib "eagle-import") (part "LED-GREEN0603"))
    )
    (comp (ref "LED_11_3")
      (value "GREEN")
      (footprint "eagle-import:LED-0603")
      (libsource (lib "eagle-import") (part "LED-GREEN0603"))
    )
    (comp (ref "LED_11_4")
      (value "GREEN")
      (footprint "eagle-import:LED-0603")
      (libsource (lib "eagle-import") (part "LED-GREEN0603"))
    )
    (comp (ref "LED_11_5")
      (value "GREEN")
      (footprint "eagle-import:LED-0603")
      (libsource (lib "eagle-import") (part "LED-GREEN0603"))
    )
    (comp (ref "LED_11_6")
      (value "GREEN")
      (footprint "eagle-import:LED-0603")
      (libsource (lib "eagle-import") (part "LED-GREEN0603"))
    )
    (comp (ref "LED_11_7")
      (value "GREEN")
      (footprint "eagle-import:LED-0603")
      (libsource (lib "eagle-import") (part "LED-GREEN0603"))
    )
    (comp (ref "LED_12_0")
      (value "GREEN")
      (footprint "eagle-import:LED-0603")
      (libsource (lib "eagle-import") (part "LED-GREEN0603"))
    )
    (comp (ref "LED_12_1")
      (value "GREEN")
      (footprint "eagle-import:LED-0603")
      (libsource (lib "eagle-import") (part "LED-GREEN0603"))
    )
    (comp (ref "LED_12_2")
      (value "GREEN")
      (footprint "eagle-import:LED-0603")
      (libsource (lib "eagle-import") (part "LED-GREEN0603"))
    )
    (comp (ref "LED_12_3")
      (value "GREEN")
      (footprint "eagle-import:LED-0603")
      (libsource (lib "eagle-import") (part "LED-GREEN0603"))
    )
    (comp (ref "LED_12_4")
      (value "GREEN")
      (footprint "eagle-import:LED-0603")
      (libsource (lib "eagle-import") (part "LED-GREEN0603"))
    )
    (comp (ref "LED_12_5")
      (value "GREEN")
      (footprint "eagle-import:LED-0603")
      (libsource (lib "eagle-import") (part "LED-GREEN0603"))
    )
    (comp (ref "LED_12_6")
      (value "GREEN")
      (footprint "eagle-import:LED-0603")
      (libsource (lib "eagle-import") (part "LED-GREEN0603"))
    )
    (comp (ref "LED_12_7")
      (value "GREEN")
      (footprint "eagle-import:LED-0603")
      (libsource (lib "eagle-import") (part "LED-GREEN0603"))
    )
    (comp (ref "LED_13_0")
      (value "GREEN")
      (footprint "eagle-import:LED-0603")
      (libsource (lib "eagle-import") (part "LED-GREEN0603"))
    )
    (comp (ref "LED_13_1")
      (value "GREEN")
      (footprint "eagle-import:LED-0603")
      (libsource (lib "eagle-import") (part "LED-GREEN0603"))
    )
    (comp (ref "LED_13_2")
      (value "GREEN")
      (footprint "eagle-import:LED-0603")
      (libsource (lib "eagle-import") (part "LED-GREEN0603"))
    )
    (comp (ref "LED_13_3")
      (value "GREEN")
      (footprint "eagle-import:LED-0603")
      (libsource (lib "eagle-import") (part "LED-GREEN0603"))
    )
    (comp (ref "LED_13_4")
      (value "GREEN")
      (footprint "eagle-import:LED-0603")
      (libsource (lib "eagle-import") (part "LED-GREEN0603"))
    )
    (comp (ref "LED_13_5")
      (value "GREEN")
      (footprint "eagle-import:LED-0603")
      (libsource (lib "eagle-import") (part "LED-GREEN0603"))
    )
    (comp (ref "LED_13_6")
      (value "GREEN")
      (footprint "eagle-import:LED-0603")
      (libsource (lib "eagle-import") (part "LED-GREEN0603"))
    )
    (comp (ref "LED_13_7")
      (value "GREEN")
      (footprint "eagle-import:LED-0603")
      (libsource (lib "eagle-import") (part "LED-GREEN0603"))
    )
    (comp (ref "LED_14_0")
      (value "GREEN")
      (footprint "eagle-import:LED-0603")
      (libsource (lib "eagle-import") (part "LED-GREEN0603"))
    )
    (comp (ref "LED_14_1")
      (value "GREEN")
      (footprint "eagle-import:LED-0603")
      (libsource (lib "eagle-import") (part "LED-GREEN0603"))
    )
    (comp (ref "LED_14_2")
      (value "GREEN")
      (footprint "eagle-import:LED-0603")
      (libsource (lib "eagle-import") (part "LED-GREEN0603"))
    )
    (comp (ref "LED_14_3")
      (value "GREEN")
      (footprint "eagle-import:LED-0603")
      (libsource (lib "eagle-import") (part "LED-GREEN0603"))
    )
    (comp (ref "LED_14_4")
      (value "GREEN")
      (footprint "eagle-import:LED-0603")
      (libsource (lib "eagle-import") (part "LED-GREEN0603"))
    )
    (comp (ref "LED_14_5")
      (value "GREEN")
      (footprint "eagle-import:LED-0603")
      (libsource (lib "eagle-import") (part "LED-GREEN0603"))
    )
    (comp (ref "LED_14_6")
      (value "GREEN")
      (footprint "eagle-import:LED-0603")
      (libsource (lib "eagle-import") (part "LED-GREEN0603"))
    )
    (comp (ref "LED_14_7")
      (value "GREEN")
      (footprint "eagle-import:LED-0603")
      (libsource (lib "eagle-import") (part "LED-GREEN0603"))
    )
    (comp (ref "LED_15_0")
      (value "GREEN")
      (footprint "eagle-import:LED-0603")
      (libsource (lib "eagle-import") (part "LED-GREEN0603"))
    )
    (comp (ref "LED_15_1")
      (value "GREEN")
      (footprint "eagle-import:LED-0603")
      (libsource (lib "eagle-import") (part "LED-GREEN0603"))
    )
    (comp (ref "LED_15_2")
      (value "GREEN")
      (footprint "eagle-import:LED-0603")
      (libsource (lib "eagle-import") (part "LED-GREEN0603"))
    )
    (comp (ref "LED_15_3")
      (value "GREEN")
      (footprint "eagle-import:LED-0603")
      (libsource (lib "eagle-import") (part "LED-GREEN0603"))
    )
    (comp (ref "LED_15_4")
      (value "GREEN")
      (footprint "eagle-import:LED-0603")
      (libsource (lib "eagle-import") (part "LED-GREEN0603"))
    )
    (comp (ref "LED_15_5")
      (value "GREEN")
      (footprint "eagle-import:LED-0603")
      (libsource (lib "eagle-import") (part "LED-GREEN0603"))
    )
    (comp (ref "LED_15_6")
      (value "GREEN")
      (footprint "eagle-import:LED-0603")
      (libsource (lib "eagle-import") (part "LED-GREEN0603"))
    )
    (comp (ref "LED_15_7")
      (value "GREEN")
      (footprint "eagle-import:LED-0603")
      (libsource (lib "eagle-import") (part "LED-GREEN0603"))
    )
    (comp (ref "LED_16_0")
      (value "GREEN")
      (footprint "eagle-import:LED-0603")
      (libsource (lib "eagle-import") (part "LED-GREEN0603"))
    )
    (comp (ref "LED_16_1")
      (value "GREEN")
      (footprint "eagle-import:LED-0603")
      (libsource (lib "eagle-import") (part "LED-GREEN0603"))
    )
    (comp (ref "LED_16_2")
      (value "GREEN")
      (footprint "eagle-import:LED-0603")
      (libsource (lib "eagle-import") (part "LED-GREEN0603"))
    )
    (comp (ref "LED_16_3")
      (value "GREEN")
      (footprint "eagle-import:LED-0603")
      (libsource (lib "eagle-import") (part "LED-GREEN0603"))
    )
    (comp (ref "LED_16_4")
      (value "GREEN")
      (footprint "eagle-import:LED-0603")
      (libsource (lib "eagle-import") (part "LED-GREEN0603"))
    )
    (comp (ref "LED_16_5")
      (value "GREEN")
      (footprint "eagle-import:LED-0603")
      (libsource (lib "eagle-import") (part "LED-GREEN0603"))
    )
    (comp (ref "LED_16_6")
      (value "GREEN")
      (footprint "eagle-import:LED-0603")
      (libsource (lib "eagle-import") (part "LED-GREEN0603"))
    )
    (comp (ref "LED_16_7")
      (value "GREEN")
      (footprint "eagle-import:LED-0603")
      (libsource (lib "eagle-import") (part "LED-GREEN0603"))
    )
    (comp (ref "LED_17_0")
      (value "GREEN")
      (footprint "eagle-import:LED-0603")
      (libsource (lib "eagle-import") (part "LED-GREEN0603"))
    )
    (comp (ref "LED_17_1")
      (value "GREEN")
      (footprint "eagle-import:LED-0603")
      (libsource (lib "eagle-import") (part "LED-GREEN0603"))
    )
    (comp (ref "LED_17_2")
      (value "GREEN")
      (footprint "eagle-import:LED-0603")
      (libsource (lib "eagle-import") (part "LED-GREEN0603"))
    )
    (comp (ref "LED_17_3")
      (value "GREEN")
      (footprint "eagle-import:LED-0603")
      (libsource (lib "eagle-import") (part "LED-GREEN0603"))
    )
    (comp (ref "LED_17_4")
      (value "GREEN")
      (footprint "eagle-import:LED-0603")
      (libsource (lib "eagle-import") (part "LED-GREEN0603"))
    )
    (comp (ref "LED_17_5")
      (value "GREEN")
      (footprint "eagle-import:LED-0603")
      (libsource (lib "eagle-import") (part "LED-GREEN0603"))
    )
    (comp (ref "LED_17_6")
      (value "GREEN")
      (footprint "eagle-import:LED-0603")
      (libsource (lib "eagle-import") (part "LED-GREEN0603"))
    )
    (comp (ref "LED_17_7")
      (value "GREEN")
      (footprint "eagle-import:LED-0603")
      (libsource (lib "eagle-import") (part "LED-GREEN0603"))
    )
    (comp (ref "LED_18_0")
      (value "GREEN")
      (footprint "eagle-import:LED-0603")
      (libsource (lib "eagle-import") (part "LED-GREEN0603"))
    )
    (comp (ref "LED_18_1")
      (value "GREEN")
      (footprint "eagle-import:LED-0603")
      (libsource (lib "eagle-import") (part "LED-GREEN0603"))
    )
    (comp (ref "LED_18_2")
      (value "GREEN")
      (footprint "eagle-import:LED-0603")
      (libsource (lib "eagle-import") (part "LED-GREEN0603"))
    )
    (comp (ref "LED_18_3")
      (value "GREEN")
      (footprint "eagle-import:LED-0603")
      (libsource (lib "eagle-import") (part "LED-GREEN0603"))
    )
    (comp (ref "LED_18_4")
      (value "GREEN")
      (footprint "eagle-import:LED-0603")
      (libsource (lib "eagle-import") (part "LED-GREEN0603"))
    )
    (comp (ref "LED_18_5")
      (value "GREEN")
      (footprint "eagle-import:LED-0603")
      (libsource (lib "eagle-import") (part "LED-GREEN0603"))
    )
    (comp (ref "LED_18_6")
      (value "GREEN")
      (footprint "eagle-import:LED-0603")
      (libsource (lib "eagle-import") (part "LED-GREEN0603"))
    )
    (comp (ref "LED_18_7")
      (value "GREEN")
      (footprint "eagle-import:LED-0603")
      (libsource (lib "eagle-import") (part "LED-GREEN0603"))
    )
    (comp (ref "LED_19_0")
      (value "GREEN")
      (footprint "eagle-import:LED-0603")
      (libsource (lib "eagle-import") (part "LED-GREEN0603"))
    )
    (comp (ref "LED_19_1")
      (value "GREEN")
      (footprint "eagle-import:LED-0603")
      (libsource (lib "eagle-import") (part "LED-GREEN0603"))
    )
    (comp (ref "LED_19_2")
      (value "GREEN")
      (footprint "eagle-import:LED-0603")
      (libsource (lib "eagle-import") (part "LED-GREEN0603"))
    )
    (comp (ref "LED_19_3")
      (value "GREEN")
      (footprint "eagle-import:LED-0603")
      (libsource (lib "eagle-import") (part "LED-GREEN0603"))
    )
    (comp (ref "LED_19_4")
      (value "GREEN")
      (footprint "eagle-import:LED-0603")
      (libsource (lib "eagle-import") (part "LED-GREEN0603"))
    )
    (comp (ref "LED_19_5")
      (value "GREEN")
      (footprint "eagle-import:LED-0603")
      (libsource (lib "eagle-import") (part "LED-GREEN0603"))
    )
    (comp (ref "LED_19_6")
      (value "GREEN")
      (footprint "eagle-import:LED-0603")
      (libsource (lib "eagle-import") (part "LED-GREEN0603"))
    )
    (comp (ref "LED_19_7")
      (value "GREEN")
      (footprint "eagle-import:LED-0603")
      (libsource (lib "eagle-import") (part "LED-GREEN0603"))
    )
    (comp (ref "LED_20_0")
      (value "GREEN")
      (footprint "eagle-import:LED-0603")
      (libsource (lib "eagle-import") (part "LED-GREEN0603"))
    )
    (comp (ref "LED_20_1")
      (value "GREEN")
      (footprint "eagle-import:LED-0603")
      (libsource (lib "eagle-import") (part "LED-GREEN0603"))
    )
    (comp (ref "LED_20_2")
      (value "GREEN")
      (footprint "eagle-import:LED-0603")
      (libsource (lib "eagle-import") (part "LED-GREEN0603"))
    )
    (comp (ref "LED_20_3")
      (value "GREEN")
      (footprint "eagle-import:LED-0603")
      (libsource (lib "eagle-import") (part "LED-GREEN0603"))
    )
    (comp (ref "LED_20_4")
      (value "GREEN")
      (footprint "eagle-import:LED-0603")
      (libsource (lib "eagle-import") (part "LED-GREEN0603"))
    )
    (comp (ref "LED_20_5")
      (value "GREEN")
      (footprint "eagle-import:LED-0603")
      (libsource (lib "eagle-import") (part "LED-GREEN0603"))
    )
    (comp (ref "LED_20_6")
      (value "GREEN")
      (footprint "eagle-import:LED-0603")
      (libsource (lib "eagle-import") (part "LED-GREEN0603"))
    )
    (comp (ref "LED_20_7")
      (value "GREEN")
      (footprint "eagle-import:LED-0603")
      (libsource (lib "eagle-import") (part "LED-GREEN0603"))
    )
    (comp (ref "LED_21_0")
      (value "GREEN")
      (footprint "eagle-import:LED-0603")
      (libsource (lib "eagle-import") (part "LED-GREEN0603"))
    )
    (comp (ref "LED_21_1")
      (value "GREEN")
      (footprint "eagle-import:LED-0603")
      (libsource (lib "eagle-import") (part "LED-GREEN0603"))
    )
    (comp (ref "LED_21_2")
      (value "GREEN")
      (footprint "eagle-import:LED-0603")
      (libsource (lib "eagle-import") (part "LED-GREEN0603"))
    )
    (comp (ref "LED_21_3")
      (value "GREEN")
      (footprint "eagle-import:LED-0603")
      (libsource (lib "eagle-import") (part "LED-GREEN0603"))
    )
    (comp (ref "LED_21_4")
      (value "GREEN")
      (footprint "eagle-import:LED-0603")
      (libsource (lib "eagle-import") (part "LED-GREEN0603"))
    )
    (comp (ref "LED_21_5")
      (value "GREEN")
      (footprint "eagle-import:LED-0603")
      (libsource (lib "eagle-import") (part "LED-GREEN0603"))
    )
    (comp (ref "LED_21_6")
      (value "GREEN")
      (footprint "eagle-import:LED-0603")
      (libsource (lib "eagle-import") (part "LED-GREEN0603"))
    )
    (comp (ref "LED_21_7")
      (value "GREEN")
      (footprint "eagle-import:LED-0603")
      (libsource (lib "eagle-import") (part "LED-GREEN0603"))
    )
    (comp (ref "LED_22_0")
      (value "GREEN")
      (footprint "eagle-import:LED-0603")
      (libsource (lib "eagle-import") (part "LED-GREEN0603"))
    )
    (comp (ref "LED_22_1")
      (value "GREEN")
      (footprint "eagle-import:LED-0603")
      (libsource (lib "eagle-import") (part "LED-GREEN0603"))
    )
    (comp (ref "LED_22_2")
      (value "GREEN")
      (footprint "eagle-import:LED-0603")
      (libsource (lib "eagle-import") (part "LED-GREEN0603"))
    )
    (comp (ref "LED_22_3")
      (value "GREEN")
      (footprint "eagle-import:LED-0603")
      (libsource (lib "eagle-import") (part "LED-GREEN0603"))
    )
    (comp (ref "LED_22_4")
      (value "GREEN")
      (footprint "eagle-import:LED-0603")
      (libsource (lib "eagle-import") (part "LED-GREEN0603"))
    )
    (comp (ref "LED_22_5")
      (value "GREEN")
      (footprint "eagle-import:LED-0603")
      (libsource (lib "eagle-import") (part "LED-GREEN0603"))
    )
    (comp (ref "LED_22_6")
      (value "GREEN")
      (footprint "eagle-import:LED-0603")
      (libsource (lib "eagle-import") (part "LED-GREEN0603"))
    )
    (comp (ref "LED_22_7")
      (value "GREEN")
      (footprint "eagle-import:LED-0603")
      (libsource (lib "eagle-import") (part "LED-GREEN0603"))
    )
    (comp (ref "LED_23_0")
      (value "GREEN")
      (footprint "eagle-import:LED-0603")
      (libsource (lib "eagle-import") (part "LED-GREEN0603"))
    )
    (comp (ref "LED_23_1")
      (value "GREEN")
      (footprint "eagle-import:LED-0603")
      (libsource (lib "eagle-import") (part "LED-GREEN0603"))
    )
    (comp (ref "LED_23_2")
      (value "GREEN")
      (footprint "eagle-import:LED-0603")
      (libsource (lib "eagle-import") (part "LED-GREEN0603"))
    )
    (comp (ref "LED_23_3")
      (value "GREEN")
      (footprint "eagle-import:LED-0603")
      (libsource (lib "eagle-import") (part "LED-GREEN0603"))
    )
    (comp (ref "LED_23_4")
      (value "GREEN")
      (footprint "eagle-import:LED-0603")
      (libsource (lib "eagle-import") (part "LED-GREEN0603"))
    )
    (comp (ref "LED_23_5")
      (value "GREEN")
      (footprint "eagle-import:LED-0603")
      (libsource (lib "eagle-import") (part "LED-GREEN0603"))
    )
    (comp (ref "LED_23_6")
      (value "GREEN")
      (footprint "eagle-import:LED-0603")
      (libsource (lib "eagle-import") (part "LED-GREEN0603"))
    )
    (comp (ref "LED_23_7")
      (value "GREEN")
      (footprint "eagle-import:LED-0603")
      (libsource (lib "eagle-import") (part "LED-GREEN0603"))
    )
    (comp (ref "LED_24_0")
      (value "GREEN")
      (footprint "eagle-import:LED-0603")
      (libsource (lib "eagle-import") (part "LED-GREEN0603"))
    )
    (comp (ref "LED_24_1")
      (value "GREEN")
      (footprint "eagle-import:LED-0603")
      (libsource (lib "eagle-import") (part "LED-GREEN0603"))
    )
    (comp (ref "LED_24_2")
      (value "GREEN")
      (footprint "eagle-import:LED-0603")
      (libsource (lib "eagle-import") (part "LED-GREEN0603"))
    )
    (comp (ref "LED_24_3")
      (value "GREEN")
      (footprint "eagle-import:LED-0603")
      (libsource (lib "eagle-import") (part "LED-GREEN0603"))
    )
    (comp (ref "LED_24_4")
      (value "GREEN")
      (footprint "eagle-import:LED-0603")
      (libsource (lib "eagle-import") (part "LED-GREEN0603"))
    )
    (comp (ref "LED_24_5")
      (value "GREEN")
      (footprint "eagle-import:LED-0603")
      (libsource (lib "eagle-import") (part "LED-GREEN0603"))
    )
    (comp (ref "LED_24_6")
      (value "GREEN")
      (footprint "eagle-import:LED-0603")
      (libsource (lib "eagle-import") (part "LED-GREEN0603"))
    )
    (comp (ref "LED_24_7")
      (value "GREEN")
      (footprint "eagle-import:LED-0603")
      (libsource (lib "eagle-import") (part "LED-GREEN0603"))
    )
    (comp (ref "LED_25_0")
      (value "GREEN")
      (footprint "eagle-import:LED-0603")
      (libsource (lib "eagle-import") (part "LED-GREEN0603"))
    )
    (comp (ref "LED_25_1")
      (value "GREEN")
      (footprint "eagle-import:LED-0603")
      (libsource (lib "eagle-import") (part "LED-GREEN0603"))
    )
    (comp (ref "LED_25_2")
      (value "GREEN")
      (footprint "eagle-import:LED-0603")
      (libsource (lib "eagle-import") (part "LED-GREEN0603"))
    )
    (comp (ref "LED_25_3")
      (value "GREEN")
      (footprint "eagle-import:LED-0603")
      (libsource (lib "eagle-import") (part "LED-GREEN0603"))
    )
    (comp (ref "LED_25_4")
      (value "GREEN")
      (footprint "eagle-import:LED-0603")
      (libsource (lib "eagle-import") (part "LED-GREEN0603"))
    )
    (comp (ref "LED_25_5")
      (value "GREEN")
      (footprint "eagle-import:LED-0603")
      (libsource (lib "eagle-import") (part "LED-GREEN0603"))
    )
    (comp (ref "LED_25_6")
      (value "GREEN")
      (footprint "eagle-import:LED-0603")
      (libsource (lib "eagle-import") (part "LED-GREEN0603"))
    )
    (comp (ref "LED_25_7")
      (value "GREEN")
      (footprint "eagle-import:LED-0603")
      (libsource (lib "eagle-import") (part "LED-GREEN0603"))
    )
    (comp (ref "LED_26_0")
      (value "GREEN")
      (footprint "eagle-import:LED-0603")
      (libsource (lib "eagle-import") (part "LED-GREEN0603"))
    )
    (comp (ref "LED_26_1")
      (value "GREEN")
      (footprint "eagle-import:LED-0603")
      (libsource (lib "eagle-import") (part "LED-GREEN0603"))
    )
    (comp (ref "LED_26_2")
      (value "GREEN")
      (footprint "eagle-import:LED-0603")
      (libsource (lib "eagle-import") (part "LED-GREEN0603"))
    )
    (comp (ref "LED_26_3")
      (value "GREEN")
      (footprint "eagle-import:LED-0603")
      (libsource (lib "eagle-import") (part "LED-GREEN0603"))
    )
    (comp (ref "LED_26_4")
      (value "GREEN")
      (footprint "eagle-import:LED-0603")
      (libsource (lib "eagle-import") (part "LED-GREEN0603"))
    )
    (comp (ref "LED_26_5")
      (value "GREEN")
      (footprint "eagle-import:LED-0603")
      (libsource (lib "eagle-import") (part "LED-GREEN0603"))
    )
    (comp (ref "LED_26_6")
      (value "GREEN")
      (footprint "eagle-import:LED-0603")
      (libsource (lib "eagle-import") (part "LED-GREEN0603"))
    )
    (comp (ref "LED_26_7")
      (value "GREEN")
      (footprint "eagle-import:LED-0603")
      (libsource (lib "eagle-import") (part "LED-GREEN0603"))
    )
    (comp (ref "LED_27_0")
      (value "GREEN")
      (footprint "eagle-import:LED-0603")
      (libsource (lib "eagle-import") (part "LED-GREEN0603"))
    )
    (comp (ref "LED_27_1")
      (value "GREEN")
      (footprint "eagle-import:LED-0603")
      (libsource (lib "eagle-import") (part "LED-GREEN0603"))
    )
    (comp (ref "LED_27_2")
      (value "GREEN")
      (footprint "eagle-import:LED-0603")
      (libsource (lib "eagle-import") (part "LED-GREEN0603"))
    )
    (comp (ref "LED_27_3")
      (value "GREEN")
      (footprint "eagle-import:LED-0603")
      (libsource (lib "eagle-import") (part "LED-GREEN0603"))
    )
    (comp (ref "LED_27_4")
      (value "GREEN")
      (footprint "eagle-import:LED-0603")
      (libsource (lib "eagle-import") (part "LED-GREEN0603"))
    )
    (comp (ref "LED_27_5")
      (value "GREEN")
      (footprint "eagle-import:LED-0603")
      (libsource (lib "eagle-import") (part "LED-GREEN0603"))
    )
    (comp (ref "LED_27_6")
      (value "GREEN")
      (footprint "eagle-import:LED-0603")
      (libsource (lib "eagle-import") (part "LED-GREEN0603"))
    )
    (comp (ref "LED_27_7")
      (value "GREEN")
      (footprint "eagle-import:LED-0603")
      (libsource (lib "eagle-import") (part "LED-GREEN0603"))
    )
    (comp (ref "LED_28_0")
      (value "GREEN")
      (footprint "eagle-import:LED-0603")
      (libsource (lib "eagle-import") (part "LED-GREEN0603"))
    )
    (comp (ref "LED_28_1")
      (value "GREEN")
      (footprint "eagle-import:LED-0603")
      (libsource (lib "eagle-import") (part "LED-GREEN0603"))
    )
    (comp (ref "LED_28_2")
      (value "GREEN")
      (footprint "eagle-import:LED-0603")
      (libsource (lib "eagle-import") (part "LED-GREEN0603"))
    )
    (comp (ref "LED_28_3")
      (value "GREEN")
      (footprint "eagle-import:LED-0603")
      (libsource (lib "eagle-import") (part "LED-GREEN0603"))
    )
    (comp (ref "LED_28_4")
      (value "GREEN")
      (footprint "eagle-import:LED-0603")
      (libsource (lib "eagle-import") (part "LED-GREEN0603"))
    )
    (comp (ref "LED_28_5")
      (value "GREEN")
      (footprint "eagle-import:LED-0603")
      (libsource (lib "eagle-import") (part "LED-GREEN0603"))
    )
    (comp (ref "LED_28_6")
      (value "GREEN")
      (footprint "eagle-import:LED-0603")
      (libsource (lib "eagle-import") (part "LED-GREEN0603"))
    )
    (comp (ref "LED_28_7")
      (value "GREEN")
      (footprint "eagle-import:LED-0603")
      (libsource (lib "eagle-import") (part "LED-GREEN0603"))
    )
    (comp (ref "LED_29_0")
      (value "GREEN")
      (footprint "eagle-import:LED-0603")
      (libsource (lib "eagle-import") (part "LED-GREEN0603"))
    )
    (comp (ref "LED_29_1")
      (value "GREEN")
      (footprint "eagle-import:LED-0603")
      (libsource (lib "eagle-import") (part "LED-GREEN0603"))
    )
    (comp (ref "LED_29_2")
      (value "GREEN")
      (footprint "eagle-import:LED-0603")
      (libsource (lib "eagle-import") (part "LED-GREEN0603"))
    )
    (comp (ref "LED_29_3")
      (value "GREEN")
      (footprint "eagle-import:LED-0603")
      (libsource (lib "eagle-import") (part "LED-GREEN0603"))
    )
    (comp (ref "LED_29_4")
      (value "GREEN")
      (footprint "eagle-import:LED-0603")
      (libsource (lib "eagle-import") (part "LED-GREEN0603"))
    )
    (comp (ref "LED_29_5")
      (value "GREEN")
      (footprint "eagle-import:LED-0603")
      (libsource (lib "eagle-import") (part "LED-GREEN0603"))
    )
    (comp (ref "LED_29_6")
      (value "GREEN")
      (footprint "eagle-import:LED-0603")
      (libsource (lib "eagle-import") (part "LED-GREEN0603"))
    )
    (comp (ref "LED_29_7")
      (value "GREEN")
      (footprint "eagle-import:LED-0603")
      (libsource (lib "eagle-import") (part "LED-GREEN0603"))
    )
    (comp (ref "LED_30_0")
      (value "GREEN")
      (footprint "eagle-import:LED-0603")
      (libsource (lib "eagle-import") (part "LED-GREEN0603"))
    )
    (comp (ref "LED_30_1")
      (value "GREEN")
      (footprint "eagle-import:LED-0603")
      (libsource (lib "eagle-import") (part "LED-GREEN0603"))
    )
    (comp (ref "LED_30_2")
      (value "GREEN")
      (footprint "eagle-import:LED-0603")
      (libsource (lib "eagle-import") (part "LED-GREEN0603"))
    )
    (comp (ref "LED_30_3")
      (value "GREEN")
      (footprint "eagle-import:LED-0603")
      (libsource (lib "eagle-import") (part "LED-GREEN0603"))
    )
    (comp (ref "LED_30_4")
      (value "GREEN")
      (footprint "eagle-import:LED-0603")
      (libsource (lib "eagle-import") (part "LED-GREEN0603"))
    )
    (comp (ref "LED_30_5")
      (value "GREEN")
      (footprint "eagle-import:LED-0603")
      (libsource (lib "eagle-import") (part "LED-GREEN0603"))
    )
    (comp (ref "LED_30_6")
      (value "GREEN")
      (footprint "eagle-import:LED-0603")
      (libsource (lib "eagle-import") (part "LED-GREEN0603"))
    )
    (comp (ref "LED_30_7")
      (value "GREEN")
      (footprint "eagle-import:LED-0603")
      (libsource (lib "eagle-import") (part "LED-GREEN0603"))
    )
    (comp (ref "LED_31_0")
      (value "GREEN")
      (footprint "eagle-import:LED-0603")
      (libsource (lib "eagle-import") (part "LED-GREEN0603"))
    )
    (comp (ref "LED_31_1")
      (value "GREEN")
      (footprint "eagle-import:LED-0603")
      (libsource (lib "eagle-import") (part "LED-GREEN0603"))
    )
    (comp (ref "LED_31_2")
      (value "GREEN")
      (footprint "eagle-import:LED-0603")
      (libsource (lib "eagle-import") (part "LED-GREEN0603"))
    )
    (comp (ref "LED_31_3")
      (value "GREEN")
      (footprint "eagle-import:LED-0603")
      (libsource (lib "eagle-import") (part "LED-GREEN0603"))
    )
    (comp (ref "LED_31_4")
      (value "GREEN")
      (footprint "eagle-import:LED-0603")
      (libsource (lib "eagle-import") (part "LED-GREEN0603"))
    )
    (comp (ref "LED_31_5")
      (value "GREEN")
      (footprint "eagle-import:LED-0603")
      (libsource (lib "eagle-import") (part "LED-GREEN0603"))
    )
    (comp (ref "LED_31_6")
      (value "GREEN")
      (footprint "eagle-import:LED-0603")
      (libsource (lib "eagle-import") (part "LED-GREEN0603"))
    )
    (comp (ref "LED_31_7")
      (value "GREEN")
      (footprint "eagle-import:LED-0603")
      (libsource (lib "eagle-import") (part "LED-GREEN0603"))
    )
    (comp (ref "SHIFT_0")
      (value "SN74HC595D")
      (footprint "eagle-import:SO16")
      (libsource (lib "eagle-import") (part "74595DHC"))
    )
    (comp (ref "SHIFT_1")
      (value "SN74HC595D")
      (footprint "eagle-import:SO16")
      (libsource (lib "eagle-import") (part "74595DHC"))
    )
    (comp (ref "SHIFT_2")
      (value "SN74HC595D")
      (footprint "eagle-import:SO16")
      (libsource (lib "eagle-import") (part "74595DHC"))
    )
    (comp (ref "SHIFT_3")
      (value "SN74HC595D")
      (footprint "eagle-import:SO16")
      (libsource (lib "eagle-import") (part "74595DHC"))
    )
    (comp (ref "SHIFT_4")
      (value "SN74HC595D")
      (footprint "eagle-import:SO16")
      (libsource (lib "eagle-import") (part "74595DHC"))
    )
    (comp (ref "SHIFT_5")
      (value "SN74HC595D")
      (footprint "eagle-import:SO16")
      (libsource (lib "eagle-import") (part "74595DHC"))
    )
    (comp (ref "SHIFT_6")
      (value "SN74HC595D")
      (footprint "eagle-import:SO16")
      (libsource (lib "eagle-import") (part "74595DHC"))
    )
    (comp (ref "SHIFT_7")
      (value "SN74HC595D")
      (footprint "eagle-import:SO16")
      (libsource (lib "eagle-import") (part "74595DHC"))
    )
    (comp (ref "SHIFT_8")
      (value "SN74HC595D")
      (footprint "eagle-import:SO16")
      (libsource (lib "eagle-import") (part "74595DHC"))
    )
    (comp (ref "SHIFT_9")
      (value "SN74HC595D")
      (footprint "eagle-import:SO16")
      (libsource (lib "eagle-import") (part "74595DHC"))
    )
    (comp (ref "SHIFT_10")
      (value "SN74HC595D")
      (footprint "eagle-import:SO16")
      (libsource (lib "eagle-import") (part "74595DHC"))
    )
    (comp (ref "SHIFT_11")
      (value "SN74HC595D")
      (footprint "eagle-import:SO16")
      (libsource (lib "eagle-import") (part "74595DHC"))
    )
    (comp (ref "SHIFT_12")
      (value "SN74HC595D")
      (footprint "eagle-import:SO16")
      (libsource (lib "eagle-import") (part "74595DHC"))
    )
    (comp (ref "SHIFT_13")
      (value "SN74HC595D")
      (footprint "eagle-import:SO16")
      (libsource (lib "eagle-import") (part "74595DHC"))
    )
    (comp (ref "SHIFT_14")
      (value "SN74HC595D")
      (footprint "eagle-import:SO16")
      (libsource (lib "eagle-import") (part "74595DHC"))
    )
    (comp (ref "SHIFT_15")
      (value "SN74HC595D")
      (footprint "eagle-import:SO16")
      (libsource (lib "eagle-import") (part "74595DHC"))
    )
    (comp (ref "SHIFT_16")
      (value "SN74HC595D")
      (footprint "eagle-import:SO16")
      (libsource (lib "eagle-import") (part "74595DHC"))
    )
    (comp (ref "SHIFT_17")
      (value "SN74HC595D")
      (footprint "eagle-import:SO16")
      (libsource (lib "eagle-import") (part "74595DHC"))
    )
    (comp (ref "SHIFT_18")
      (value "SN74HC595D")
      (footprint "eagle-import:SO16")
      (libsource (lib "eagle-import") (part "74595DHC"))
    )
    (comp (ref "SHIFT_19")
      (value "SN74HC595D")
      (footprint "eagle-import:SO16")
      (libsource (lib "eagle-import") (part "74595DHC"))
    )
    (comp (ref "SHIFT_20")
      (value "SN74HC595D")
      (footprint "eagle-import:SO16")
      (libsource (lib "eagle-import") (part "74595DHC"))
    )
    (comp (ref "SHIFT_21")
      (value "SN74HC595D")
      (footprint "eagle-import:SO16")
      (libsource (lib "eagle-import") (part "74595DHC"))
    )
    (comp (ref "SHIFT_22")
      (value "SN74HC595D")
      (footprint "eagle-import:SO16")
      (libsource (lib "eagle-import") (part "74595DHC"))
    )
    (comp (ref "SHIFT_23")
      (value "SN74HC595D")
      (footprint "eagle-import:SO16")
      (libsource (lib "eagle-import") (part "74595DHC"))
    )
    (comp (ref "SHIFT_24")
      (value "SN74HC595D")
      (footprint "eagle-import:SO16")
      (libsource (lib "eagle-import") (part "74595DHC"))
    )
    (comp (ref "SHIFT_25")
      (value "SN74HC595D")
      (footprint "eagle-import:SO16")
      (libsource (lib "eagle-import") (part "74595DHC"))
    )
    (comp (ref "SHIFT_26")
      (value "SN74HC595D")
      (footprint "eagle-import:SO16")
      (libsource (lib "eagle-import") (part "74595DHC"))
    )
    (comp (ref "SHIFT_27")
      (value "SN74HC595D")
      (footprint "eagle-import:SO16")
      (libsource (lib "eagle-import") (part "74595DHC"))
    )
    (comp (ref "SHIFT_28")
      (value "SN74HC595D")
      (footprint "eagle-import:SO16")
      (libsource (lib "eagle-import") (part "74595DHC"))
    )
    (comp (ref "SHIFT_29")
      (value "SN74HC595D")
      (footprint "eagle-import:SO16")
      (libsource (lib "eagle-import") (part "74595DHC"))
    )
    (comp (ref "SHIFT_30")
      (value "SN74HC595D")
      (footprint "eagle-import:SO16")
      (libsource (lib "eagle-import") (part "74595DHC"))
    )
    (comp (ref "SHIFT_31")
      (value "SN74HC595D")
      (footprint "eagle-import:SO16")
      (libsource (lib "eagle-import") (part "74595DHC"))
    )
  )
  (nets
    (net (code "1") (name "/GND") (class "Default")
      (node (ref "C1") (pin "-") (pinfunction "-_-") (pintype "passive"))
      (node (ref "J1") (pin "6") (pinfunction "6_6") (pintype "passive"))
      (node (ref "J2") (pin "2") (pinfunction "2_2") (pintype "passive"))
      (node (ref "J3") (pin "4") (pinfunction "4_4") (pintype "passive"))
      (node (ref "LED_0_0") (pin "A") (pinfunction "A_A") (pintype "passive"))
      (node (ref "LED_0_1") (pin "A") (pinfunction "A_A") (pintype "passive"))
      (node (ref "LED_0_2") (pin "A") (pinfunction "A_A") (pintype "passive"))
      (node (ref "LED_0_3") (pin "A") (pinfunction "A_A") (pintype "passive"))
      (node (ref "LED_0_4") (pin "A") (pinfunction "A_A") (pintype "passive"))
      (node (ref "LED_0_5") (pin "A") (pinfunction "A_A") (pintype "passive"))
      (node (ref "LED_0_6") (pin "A") (pinfunction "A_A") (pintype "passive"))
      (node (ref "LED_0_7") (pin "A") (pinfunction "A_A") (pintype "passive"))
      (node (ref "LED_10_0") (pin "A") (pinfunction "A_A") (pintype "passive"))
      (node (ref "LED_10_1") (pin "A") (pinfunction "A_A") (pintype "passive"))
      (node (ref "LED_10_2") (pin "A") (pinfunction "A_A") (pintype "passive"))
      (node (ref "LED_10_3") (pin "A") (pinfunction "A_A") (pintype "passive"))
      (node (ref "LED_10_4") (pin "A") (pinfunction "A_A") (pintype "passive"))
      (node (ref "LED_10_5") (pin "A") (pinfunction "A_A") (pintype "passive"))
      (node (ref "LED_10_6") (pin "A") (pinfunction "A_A") (pintype "passive"))
      (node (ref "LED_10_7") (pin "A") (pinfunction "A_A") (pintype "passive"))
      (node (ref "LED_11_0") (pin "A") (pinfunction "A_A") (pintype "passive"))
      (node (ref "LED_11_1") (pin "A") (pinfunction "A_A") (pintype "passive"))
      (node (ref "LED_11_2") (pin "A") (pinfunction "A_A") (pintype "passive"))
      (node (ref "LED_11_3") (pin "A") (pinfunction "A_A") (pintype "passive"))
      (node (ref "LED_11_4") (pin "A") (pinfunction "A_A") (pintype "passive"))
      (node (ref "LED_11_5") (pin "A") (pinfunction "A_A") (pintype "passive"))
      (node (ref "LED_11_6") (pin "A") (pinfunction "A_A") (pintype "passive"))
      (node (ref "LED_11_7") (pin "A") (pinfunction "A_A") (pintype "passive"))
      (node (ref "LED_12_0") (pin "A") (pinfunction "A_A") (pintype "passive"))
      (node (ref "LED_12_1") (pin "A") (pinfunction "A_A") (pintype "passive"))
      (node (ref "LED_12_2") (pin "A") (pinfunction "A_A") (pintype "passive"))
      (node (ref "LED_12_3") (pin "A") (pinfunction "A_A") (pintype "passive"))
      (node (ref "LED_12_4") (pin "A") (pinfunction "A_A") (pintype "passive"))
      (node (ref "LED_12_5") (pin "A") (pinfunction "A_A") (pintype "passive"))
      (node (ref "LED_12_6") (pin "A") (pinfunction "A_A") (pintype "passive"))
      (node (ref "LED_12_7") (pin "A") (pinfunction "A_A") (pintype "passive"))
      (node (ref "LED_13_0") (pin "A") (pinfunction "A_A") (pintype "passive"))
      (node (ref "LED_13_1") (pin "A") (pinfunction "A_A") (pintype "passive"))
      (node (ref "LED_13_2") (pin "A") (pinfunction "A_A") (pintype "passive"))
      (node (ref "LED_13_3") (pin "A") (pinfunction "A_A") (pintype "passive"))
      (node (ref "LED_13_4") (pin "A") (pinfunction "A_A") (pintype "passive"))
      (node (ref "LED_13_5") (pin "A") (pinfunction "A_A") (pintype "passive"))
      (node (ref "LED_13_6") (pin "A") (pinfunction "A_A") (pintype "passive"))
      (node (ref "LED_13_7") (pin "A") (pinfunction "A_A") (pintype "passive"))
      (node (ref "LED_14_0") (pin "A") (pinfunction "A_A") (pintype "passive"))
      (node (ref "LED_14_1") (pin "A") (pinfunction "A_A") (pintype "passive"))
      (node (ref "LED_14_2") (pin "A") (pinfunction "A_A") (pintype "passive"))
      (node (ref "LED_14_3") (pin "A") (pinfunction "A_A") (pintype "passive"))
      (node (ref "LED_14_4") (pin "A") (pinfunction "A_A") (pintype "passive"))
      (node (ref "LED_14_5") (pin "A") (pinfunction "A_A") (pintype "passive"))
      (node (ref "LED_14_6") (pin "A") (pinfunction "A_A") (pintype "passive"))
      (node (ref "LED_14_7") (pin "A") (pinfunction "A_A") (pintype "passive"))
      (node (ref "LED_15_0") (pin "A") (pinfunction "A_A") (pintype "passive"))
      (node (ref "LED_15_1") (pin "A") (pinfunction "A_A") (pintype "passive"))
      (node (ref "LED_15_2") (pin "A") (pinfunction "A_A") (pintype "passive"))
      (node (ref "LED_15_3") (pin "A") (pinfunction "A_A") (pintype "passive"))
      (node (ref "LED_15_4") (pin "A") (pinfunction "A_A") (pintype "passive"))
      (node (ref "LED_15_5") (pin "A") (pinfunction "A_A") (pintype "passive"))
      (node (ref "LED_15_6") (pin "A") (pinfunction "A_A") (pintype "passive"))
      (node (ref "LED_15_7") (pin "A") (pinfunction "A_A") (pintype "passive"))
      (node (ref "LED_16_0") (pin "A") (pinfunction "A_A") (pintype "passive"))
      (node (ref "LED_16_1") (pin "A") (pinfunction "A_A") (pintype "passive"))
      (node (ref "LED_16_2") (pin "A") (pinfunction "A_A") (pintype "passive"))
      (node (ref "LED_16_3") (pin "A") (pinfunction "A_A") (pintype "passive"))
      (node (ref "LED_16_4") (pin "A") (pinfunction "A_A") (pintype "passive"))
      (node (ref "LED_16_5") (pin "A") (pinfunction "A_A") (pintype "passive"))
      (node (ref "LED_16_6") (pin "A") (pinfunction "A_A") (pintype "passive"))
      (node (ref "LED_16_7") (pin "A") (pinfunction "A_A") (pintype "passive"))
      (node (ref "LED_17_0") (pin "A") (pinfunction "A_A") (pintype "passive"))
      (node (ref "LED_17_1") (pin "A") (pinfunction "A_A") (pintype "passive"))
      (node (ref "LED_17_2") (pin "A") (pinfunction "A_A") (pintype "passive"))
      (node (ref "LED_17_3") (pin "A") (pinfunction "A_A") (pintype "passive"))
      (node (ref "LED_17_4") (pin "A") (pinfunction "A_A") (pintype "passive"))
      (node (ref "LED_17_5") (pin "A") (pinfunction "A_A") (pintype "passive"))
      (node (ref "LED_17_6") (pin "A") (pinfunction "A_A") (pintype "passive"))
      (node (ref "LED_17_7") (pin "A") (pinfunction "A_A") (pintype "passive"))
      (node (ref "LED_18_0") (pin "A") (pinfunction "A_A") (pintype "passive"))
      (node (ref "LED_18_1") (pin "A") (pinfunction "A_A") (pintype "passive"))
      (node (ref "LED_18_2") (pin "A") (pinfunction "A_A") (pintype "passive"))
      (node (ref "LED_18_3") (pin "A") (pinfunction "A_A") (pintype "passive"))
      (node (ref "LED_18_4") (pin "A") (pinfunction "A_A") (pintype "passive"))
      (node (ref "LED_18_5") (pin "A") (pinfunction "A_A") (pintype "passive"))
      (node (ref "LED_18_6") (pin "A") (pinfunction "A_A") (pintype "passive"))
      (node (ref "LED_18_7") (pin "A") (pinfunction "A_A") (pintype "passive"))
      (node (ref "LED_19_0") (pin "A") (pinfunction "A_A") (pintype "passive"))
      (node (ref "LED_19_1") (pin "A") (pinfunction "A_A") (pintype "passive"))
      (node (ref "LED_19_2") (pin "A") (pinfunction "A_A") (pintype "passive"))
      (node (ref "LED_19_3") (pin "A") (pinfunction "A_A") (pintype "passive"))
      (node (ref "LED_19_4") (pin "A") (pinfunction "A_A") (pintype "passive"))
      (node (ref "LED_19_5") (pin "A") (pinfunction "A_A") (pintype "passive"))
      (node (ref "LED_19_6") (pin "A") (pinfunction "A_A") (pintype "passive"))
      (node (ref "LED_19_7") (pin "A") (pinfunction "A_A") (pintype "passive"))
      (node (ref "LED_1_0") (pin "A") (pinfunction "A_A") (pintype "passive"))
      (node (ref "LED_1_1") (pin "A") (pinfunction "A_A") (pintype "passive"))
      (node (ref "LED_1_2") (pin "A") (pinfunction "A_A") (pintype "passive"))
      (node (ref "LED_1_3") (pin "A") (pinfunction "A_A") (pintype "passive"))
      (node (ref "LED_1_4") (pin "A") (pinfunction "A_A") (pintype "passive"))
      (node (ref "LED_1_5") (pin "A") (pinfunction "A_A") (pintype "passive"))
      (node (ref "LED_1_6") (pin "A") (pinfunction "A_A") (pintype "passive"))
      (node (ref "LED_1_7") (pin "A") (pinfunction "A_A") (pintype "passive"))
      (node (ref "LED_20_0") (pin "A") (pinfunction "A_A") (pintype "passive"))
      (node (ref "LED_20_1") (pin "A") (pinfunction "A_A") (pintype "passive"))
      (node (ref "LED_20_2") (pin "A") (pinfunction "A_A") (pintype "passive"))
      (node (ref "LED_20_3") (pin "A") (pinfunction "A_A") (pintype "passive"))
      (node (ref "LED_20_4") (pin "A") (pinfunction "A_A") (pintype "passive"))
      (node (ref "LED_20_5") (pin "A") (pinfunction "A_A") (pintype "passive"))
      (node (ref "LED_20_6") (pin "A") (pinfunction "A_A") (pintype "passive"))
      (node (ref "LED_20_7") (pin "A") (pinfunction "A_A") (pintype "passive"))
      (node (ref "LED_21_0") (pin "A") (pinfunction "A_A") (pintype "passive"))
      (node (ref "LED_21_1") (pin "A") (pinfunction "A_A") (pintype "passive"))
      (node (ref "LED_21_2") (pin "A") (pinfunction "A_A") (pintype "passive"))
      (node (ref "LED_21_3") (pin "A") (pinfunction "A_A") (pintype "passive"))
      (node (ref "LED_21_4") (pin "A") (pinfunction "A_A") (pintype "passive"))
      (node (ref "LED_21_5") (pin "A") (pinfunction "A_A") (pintype "passive"))
      (node (ref "LED_21_6") (pin "A") (pinfunction "A_A") (pintype "passive"))
      (node (ref "LED_21_7") (pin "A") (pinfunction "A_A") (pintype "passive"))
      (node (ref "LED_22_0") (pin "A") (pinfunction "A_A") (pintype "passive"))
      (node (ref "LED_22_1") (pin "A") (pinfunction "A_A") (pintype "passive"))
      (node (ref "LED_22_2") (pin "A") (pinfunction "A_A") (pintype "passive"))
      (node (ref "LED_22_3") (pin "A") (pinfunction "A_A") (pintype "passive"))
      (node (ref "LED_22_4") (pin "A") (pinfunction "A_A") (pintype "passive"))
      (node (ref "LED_22_5") (pin "A") (pinfunction "A_A") (pintype "passive"))
      (node (ref "LED_22_6") (pin "A") (pinfunction "A_A") (pintype "passive"))
      (node (ref "LED_22_7") (pin "A") (pinfunction "A_A") (pintype "passive"))
      (node (ref "LED_23_0") (pin "A") (pinfunction "A_A") (pintype "passive"))
      (node (ref "LED_23_1") (pin "A") (pinfunction "A_A") (pintype "passive"))
      (node (ref "LED_23_2") (pin "A") (pinfunction "A_A") (pintype "passive"))
      (node (ref "LED_23_3") (pin "A") (pinfunction "A_A") (pintype "passive"))
      (node (ref "LED_23_4") (pin "A") (pinfunction "A_A") (pintype "passive"))
      (node (ref "LED_23_5") (pin "A") (pinfunction "A_A") (pintype "passive"))
      (node (ref "LED_23_6") (pin "A") (pinfunction "A_A") (pintype "passive"))
      (node (ref "LED_23_7") (pin "A") (pinfunction "A_A") (pintype "passive"))
      (node (ref "LED_24_0") (pin "A") (pinfunction "A_A") (pintype "passive"))
      (node (ref "LED_24_1") (pin "A") (pinfunction "A_A") (pintype "passive"))
      (node (ref "LED_24_2") (pin "A") (pinfunction "A_A") (pintype "passive"))
      (node (ref "LED_24_3") (pin "A") (pinfunction "A_A") (pintype "passive"))
      (node (ref "LED_24_4") (pin "A") (pinfunction "A_A") (pintype "passive"))
      (node (ref "LED_24_5") (pin "A") (pinfunction "A_A") (pintype "passive"))
      (node (ref "LED_24_6") (pin "A") (pinfunction "A_A") (pintype "passive"))
      (node (ref "LED_24_7") (pin "A") (pinfunction "A_A") (pintype "passive"))
      (node (ref "LED_25_0") (pin "A") (pinfunction "A_A") (pintype "passive"))
      (node (ref "LED_25_1") (pin "A") (pinfunction "A_A") (pintype "passive"))
      (node (ref "LED_25_2") (pin "A") (pinfunction "A_A") (pintype "passive"))
      (node (ref "LED_25_3") (pin "A") (pinfunction "A_A") (pintype "passive"))
      (node (ref "LED_25_4") (pin "A") (pinfunction "A_A") (pintype "passive"))
      (node (ref "LED_25_5") (pin "A") (pinfunction "A_A") (pintype "passive"))
      (node (ref "LED_25_6") (pin "A") (pinfunction "A_A") (pintype "passive"))
      (node (ref "LED_25_7") (pin "A") (pinfunction "A_A") (pintype "passive"))
      (node (ref "LED_26_0") (pin "A") (pinfunction "A_A") (pintype "passive"))
      (node (ref "LED_26_1") (pin "A") (pinfunction "A_A") (pintype "passive"))
      (node (ref "LED_26_2") (pin "A") (pinfunction "A_A") (pintype "passive"))
      (node (ref "LED_26_3") (pin "A") (pinfunction "A_A") (pintype "passive"))
      (node (ref "LED_26_4") (pin "A") (pinfunction "A_A") (pintype "passive"))
      (node (ref "LED_26_5") (pin "A") (pinfunction "A_A") (pintype "passive"))
      (node (ref "LED_26_6") (pin "A") (pinfunction "A_A") (pintype "passive"))
      (node (ref "LED_26_7") (pin "A") (pinfunction "A_A") (pintype "passive"))
      (node (ref "LED_27_0") (pin "A") (pinfunction "A_A") (pintype "passive"))
      (node (ref "LED_27_1") (pin "A") (pinfunction "A_A") (pintype "passive"))
      (node (ref "LED_27_2") (pin "A") (pinfunction "A_A") (pintype "passive"))
      (node (ref "LED_27_3") (pin "A") (pinfunction "A_A") (pintype "passive"))
      (node (ref "LED_27_4") (pin "A") (pinfunction "A_A") (pintype "passive"))
      (node (ref "LED_27_5") (pin "A") (pinfunction "A_A") (pintype "passive"))
      (node (ref "LED_27_6") (pin "A") (pinfunction "A_A") (pintype "passive"))
      (node (ref "LED_27_7") (pin "A") (pinfunction "A_A") (pintype "passive"))
      (node (ref "LED_28_0") (pin "A") (pinfunction "A_A") (pintype "passive"))
      (node (ref "LED_28_1") (pin "A") (pinfunction "A_A") (pintype "passive"))
      (node (ref "LED_28_2") (pin "A") (pinfunction "A_A") (pintype "passive"))
      (node (ref "LED_28_3") (pin "A") (pinfunction "A_A") (pintype "passive"))
      (node (ref "LED_28_4") (pin "A") (pinfunction "A_A") (pintype "passive"))
      (node (ref "LED_28_5") (pin "A") (pinfunction "A_A") (pintype "passive"))
      (node (ref "LED_28_6") (pin "A") (pinfunction "A_A") (pintype "passive"))
      (node (ref "LED_28_7") (pin "A") (pinfunction "A_A") (pintype "passive"))
      (node (ref "LED_29_0") (pin "A") (pinfunction "A_A") (pintype "passive"))
      (node (ref "LED_29_1") (pin "A") (pinfunction "A_A") (pintype "passive"))
      (node (ref "LED_29_2") (pin "A") (pinfunction "A_A") (pintype "passive"))
      (node (ref "LED_29_3") (pin "A") (pinfunction "A_A") (pintype "passive"))
      (node (ref "LED_29_4") (pin "A") (pinfunction "A_A") (pintype "passive"))
      (node (ref "LED_29_5") (pin "A") (pinfunction "A_A") (pintype "passive"))
      (node (ref "LED_29_6") (pin "A") (pinfunction "A_A") (pintype "passive"))
      (node (ref "LED_29_7") (pin "A") (pinfunction "A_A") (pintype "passive"))
      (node (ref "LED_2_0") (pin "A") (pinfunction "A_A") (pintype "passive"))
      (node (ref "LED_2_1") (pin "A") (pinfunction "A_A") (pintype "passive"))
      (node (ref "LED_2_2") (pin "A") (pinfunction "A_A") (pintype "passive"))
      (node (ref "LED_2_3") (pin "A") (pinfunction "A_A") (pintype "passive"))
      (node (ref "LED_2_4") (pin "A") (pinfunction "A_A") (pintype "passive"))
      (node (ref "LED_2_5") (pin "A") (pinfunction "A_A") (pintype "passive"))
      (node (ref "LED_2_6") (pin "A") (pinfunction "A_A") (pintype "passive"))
      (node (ref "LED_2_7") (pin "A") (pinfunction "A_A") (pintype "passive"))
      (node (ref "LED_30_0") (pin "A") (pinfunction "A_A") (pintype "passive"))
      (node (ref "LED_30_1") (pin "A") (pinfunction "A_A") (pintype "passive"))
      (node (ref "LED_30_2") (pin "A") (pinfunction "A_A") (pintype "passive"))
      (node (ref "LED_30_3") (pin "A") (pinfunction "A_A") (pintype "passive"))
      (node (ref "LED_30_4") (pin "A") (pinfunction "A_A") (pintype "passive"))
      (node (ref "LED_30_5") (pin "A") (pinfunction "A_A") (pintype "passive"))
      (node (ref "LED_30_6") (pin "A") (pinfunction "A_A") (pintype "passive"))
      (node (ref "LED_30_7") (pin "A") (pinfunction "A_A") (pintype "passive"))
      (node (ref "LED_31_0") (pin "A") (pinfunction "A_A") (pintype "passive"))
      (node (ref "LED_31_1") (pin "A") (pinfunction "A_A") (pintype "passive"))
      (node (ref "LED_31_2") (pin "A") (pinfunction "A_A") (pintype "passive"))
      (node (ref "LED_31_3") (pin "A") (pinfunction "A_A") (pintype "passive"))
      (node (ref "LED_31_4") (pin "A") (pinfunction "A_A") (pintype "passive"))
      (node (ref "LED_31_5") (pin "A") (pinfunction "A_A") (pintype "passive"))
      (node (ref "LED_31_6") (pin "A") (pinfunction "A_A") (pintype "passive"))
      (node (ref "LED_31_7") (pin "A") (pinfunction "A_A") (pintype "passive"))
      (node (ref "LED_3_0") (pin "A") (pinfunction "A_A") (pintype "passive"))
      (node (ref "LED_3_1") (pin "A") (pinfunction "A_A") (pintype "passive"))
      (node (ref "LED_3_2") (pin "A") (pinfunction "A_A") (pintype "passive"))
      (node (ref "LED_3_3") (pin "A") (pinfunction "A_A") (pintype "passive"))
      (node (ref "LED_3_4") (pin "A") (pinfunction "A_A") (pintype "passive"))
      (node (ref "LED_3_5") (pin "A") (pinfunction "A_A") (pintype "passive"))
      (node (ref "LED_3_6") (pin "A") (pinfunction "A_A") (pintype "passive"))
      (node (ref "LED_3_7") (pin "A") (pinfunction "A_A") (pintype "passive"))
      (node (ref "LED_4_0") (pin "A") (pinfunction "A_A") (pintype "passive"))
      (node (ref "LED_4_1") (pin "A") (pinfunction "A_A") (pintype "passive"))
      (node (ref "LED_4_2") (pin "A") (pinfunction "A_A") (pintype "passive"))
      (node (ref "LED_4_3") (pin "A") (pinfunction "A_A") (pintype "passive"))
      (node (ref "LED_4_4") (pin "A") (pinfunction "A_A") (pintype "passive"))
      (node (ref "LED_4_5") (pin "A") (pinfunction "A_A") (pintype "passive"))
      (node (ref "LED_4_6") (pin "A") (pinfunction "A_A") (pintype "passive"))
      (node (ref "LED_4_7") (pin "A") (pinfunction "A_A") (pintype "passive"))
      (node (ref "LED_5_0") (pin "A") (pinfunction "A_A") (pintype "passive"))
      (node (ref "LED_5_1") (pin "A") (pinfunction "A_A") (pintype "passive"))
      (node (ref "LED_5_2") (pin "A") (pinfunction "A_A") (pintype "passive"))
      (node (ref "LED_5_3") (pin "A") (pinfunction "A_A") (pintype "passive"))
      (node (ref "LED_5_4") (pin "A") (pinfunction "A_A") (pintype "passive"))
      (node (ref "LED_5_5") (pin "A") (pinfunction "A_A") (pintype "passive"))
      (node (ref "LED_5_6") (pin "A") (pinfunction "A_A") (pintype "passive"))
      (node (ref "LED_5_7") (pin "A") (pinfunction "A_A") (pintype "passive"))
      (node (ref "LED_6_0") (pin "A") (pinfunction "A_A") (pintype "passive"))
      (node (ref "LED_6_1") (pin "A") (pinfunction "A_A") (pintype "passive"))
      (node (ref "LED_6_2") (pin "A") (pinfunction "A_A") (pintype "passive"))
      (node (ref "LED_6_3") (pin "A") (pinfunction "A_A") (pintype "passive"))
      (node (ref "LED_6_4") (pin "A") (pinfunction "A_A") (pintype "passive"))
      (node (ref "LED_6_5") (pin "A") (pinfunction "A_A") (pintype "passive"))
      (node (ref "LED_6_6") (pin "A") (pinfunction "A_A") (pintype "passive"))
      (node (ref "LED_6_7") (pin "A") (pinfunction "A_A") (pintype "passive"))
      (node (ref "LED_7_0") (pin "A") (pinfunction "A_A") (pintype "passive"))
      (node (ref "LED_7_1") (pin "A") (pinfunction "A_A") (pintype "passive"))
      (node (ref "LED_7_2") (pin "A") (pinfunction "A_A") (pintype "passive"))
      (node (ref "LED_7_3") (pin "A") (pinfunction "A_A") (pintype "passive"))
      (node (ref "LED_7_4") (pin "A") (pinfunction "A_A") (pintype "passive"))
      (node (ref "LED_7_5") (pin "A") (pinfunction "A_A") (pintype "passive"))
      (node (ref "LED_7_6") (pin "A") (pinfunction "A_A") (pintype "passive"))
      (node (ref "LED_7_7") (pin "A") (pinfunction "A_A") (pintype "passive"))
      (node (ref "LED_8_0") (pin "A") (pinfunction "A_A") (pintype "passive"))
      (node (ref "LED_8_1") (pin "A") (pinfunction "A_A") (pintype "passive"))
      (node (ref "LED_8_2") (pin "A") (pinfunction "A_A") (pintype "passive"))
      (node (ref "LED_8_3") (pin "A") (pinfunction "A_A") (pintype "passive"))
      (node (ref "LED_8_4") (pin "A") (pinfunction "A_A") (pintype "passive"))
      (node (ref "LED_8_5") (pin "A") (pinfunction "A_A") (pintype "passive"))
      (node (ref "LED_8_6") (pin "A") (pinfunction "A_A") (pintype "passive"))
      (node (ref "LED_8_7") (pin "A") (pinfunction "A_A") (pintype "passive"))
      (node (ref "LED_9_0") (pin "A") (pinfunction "A_A") (pintype "passive"))
      (node (ref "LED_9_1") (pin "A") (pinfunction "A_A") (pintype "passive"))
      (node (ref "LED_9_2") (pin "A") (pinfunction "A_A") (pintype "passive"))
      (node (ref "LED_9_3") (pin "A") (pinfunction "A_A") (pintype "passive"))
      (node (ref "LED_9_4") (pin "A") (pinfunction "A_A") (pintype "passive"))
      (node (ref "LED_9_5") (pin "A") (pinfunction "A_A") (pintype "passive"))
      (node (ref "LED_9_6") (pin "A") (pinfunction "A_A") (pintype "passive"))
      (node (ref "LED_9_7") (pin "A") (pinfunction "A_A") (pintype "passive"))
      (node (ref "SHIFT_0") (pin "8") (pinfunction "GND_8") (pintype "power_in"))
      (node (ref "SHIFT_1") (pin "8") (pinfunction "GND_8") (pintype "power_in"))
      (node (ref "SHIFT_10") (pin "8") (pinfunction "GND_8") (pintype "power_in"))
      (node (ref "SHIFT_11") (pin "8") (pinfunction "GND_8") (pintype "power_in"))
      (node (ref "SHIFT_12") (pin "8") (pinfunction "GND_8") (pintype "power_in"))
      (node (ref "SHIFT_13") (pin "8") (pinfunction "GND_8") (pintype "power_in"))
      (node (ref "SHIFT_14") (pin "8") (pinfunction "GND_8") (pintype "power_in"))
      (node (ref "SHIFT_15") (pin "8") (pinfunction "GND_8") (pintype "power_in"))
      (node (ref "SHIFT_16") (pin "8") (pinfunction "GND_8") (pintype "power_in"))
      (node (ref "SHIFT_17") (pin "8") (pinfunction "GND_8") (pintype "power_in"))
      (node (ref "SHIFT_18") (pin "8") (pinfunction "GND_8") (pintype "power_in"))
      (node (ref "SHIFT_19") (pin "8") (pinfunction "GND_8") (pintype "power_in"))
      (node (ref "SHIFT_2") (pin "8") (pinfunction "GND_8") (pintype "power_in"))
      (node (ref "SHIFT_20") (pin "8") (pinfunction "GND_8") (pintype "power_in"))
      (node (ref "SHIFT_21") (pin "8") (pinfunction "GND_8") (pintype "power_in"))
      (node (ref "SHIFT_22") (pin "8") (pinfunction "GND_8") (pintype "power_in"))
      (node (ref "SHIFT_23") (pin "8") (pinfunction "GND_8") (pintype "power_in"))
      (node (ref "SHIFT_24") (pin "8") (pinfunction "GND_8") (pintype "power_in"))
      (node (ref "SHIFT_25") (pin "8") (pinfunction "GND_8") (pintype "power_in"))
      (node (ref "SHIFT_26") (pin "8") (pinfunction "GND_8") (pintype "power_in"))
      (node (ref "SHIFT_27") (pin "8") (pinfunction "GND_8") (pintype "power_in"))
      (node (ref "SHIFT_28") (pin "8") (pinfunction "GND_8") (pintype "power_in"))
      (node (ref "SHIFT_29") (pin "8") (pinfunction "GND_8") (pintype "power_in"))
      (node (ref "SHIFT_3") (pin "8") (pinfunction "GND_8") (pintype "power_in"))
      (node (ref "SHIFT_30") (pin "8") (pinfunction "GND_8") (pintype "power_in"))
      (node (ref "SHIFT_31") (pin "8") (pinfunction "GND_8") (pintype "power_in"))
      (node (ref "SHIFT_4") (pin "8") (pinfunction "GND_8") (pintype "power_in"))
      (node (ref "SHIFT_5") (pin "8") (pinfunction "GND_8") (pintype "power_in"))
      (node (ref "SHIFT_6") (pin "8") (pinfunction "GND_8") (pintype "power_in"))
      (node (ref "SHIFT_7") (pin "8") (pinfunction "GND_8") (pintype "power_in"))
      (node (ref "SHIFT_8") (pin "8") (pinfunction "GND_8") (pintype "power_in"))
      (node (ref "SHIFT_9") (pin "8") (pinfunction "GND_8") (pintype "power_in"))
    )
    (net (code "2") (name "/OE") (class "Default")
      (node (ref "J1") (pin "2") (pinfunction "2_2") (pintype "passive"))
      (node (ref "J3") (pin "2") (pinfunction "2_2") (pintype "passive"))
      (node (ref "SHIFT_0") (pin "13") (pinfunction "G_13") (pintype "input"))
      (node (ref "SHIFT_1") (pin "13") (pinfunction "G_13") (pintype "input"))
      (node (ref "SHIFT_10") (pin "13") (pinfunction "G_13") (pintype "input"))
      (node (ref "SHIFT_11") (pin "13") (pinfunction "G_13") (pintype "input"))
      (node (ref "SHIFT_12") (pin "13") (pinfunction "G_13") (pintype "input"))
      (node (ref "SHIFT_13") (pin "13") (pinfunction "G_13") (pintype "input"))
      (node (ref "SHIFT_14") (pin "13") (pinfunction "G_13") (pintype "input"))
      (node (ref "SHIFT_15") (pin "13") (pinfunction "G_13") (pintype "input"))
      (node (ref "SHIFT_16") (pin "13") (pinfunction "G_13") (pintype "input"))
      (node (ref "SHIFT_17") (pin "13") (pinfunction "G_13") (pintype "input"))
      (node (ref "SHIFT_18") (pin "13") (pinfunction "G_13") (pintype "input"))
      (node (ref "SHIFT_19") (pin "13") (pinfunction "G_13") (pintype "input"))
      (node (ref "SHIFT_2") (pin "13") (pinfunction "G_13") (pintype "input"))
      (node (ref "SHIFT_20") (pin "13") (pinfunction "G_13") (pintype "input"))
      (node (ref "SHIFT_21") (pin "13") (pinfunction "G_13") (pintype "input"))
      (node (ref "SHIFT_22") (pin "13") (pinfunction "G_13") (pintype "input"))
      (node (ref "SHIFT_23") (pin "13") (pinfunction "G_13") (pintype "input"))
      (node (ref "SHIFT_24") (pin "13") (pinfunction "G_13") (pintype "input"))
      (node (ref "SHIFT_25") (pin "13") (pinfunction "G_13") (pintype "input"))
      (node (ref "SHIFT_26") (pin "13") (pinfunction "G_13") (pintype "input"))
      (node (ref "SHIFT_27") (pin "13") (pinfunction "G_13") (pintype "input"))
      (node (ref "SHIFT_28") (pin "13") (pinfunction "G_13") (pintype "input"))
      (node (ref "SHIFT_29") (pin "13") (pinfunction "G_13") (pintype "input"))
      (node (ref "SHIFT_3") (pin "13") (pinfunction "G_13") (pintype "input"))
      (node (ref "SHIFT_30") (pin "13") (pinfunction "G_13") (pintype "input"))
      (node (ref "SHIFT_31") (pin "13") (pinfunction "G_13") (pintype "input"))
      (node (ref "SHIFT_4") (pin "13") (pinfunction "G_13") (pintype "input"))
      (node (ref "SHIFT_5") (pin "13") (pinfunction "G_13") (pintype "input"))
      (node (ref "SHIFT_6") (pin "13") (pinfunction "G_13") (pintype "input"))
      (node (ref "SHIFT_7") (pin "13") (pinfunction "G_13") (pintype "input"))
      (node (ref "SHIFT_8") (pin "13") (pinfunction "G_13") (pintype "input"))
      (node (ref "SHIFT_9") (pin "13") (pinfunction "G_13") (pintype "input"))
    )
    (net (code "3") (name "/Q0_0") (class "Default")
      (node (ref "4R_0_0") (pin "1") (pinfunction "1_1") (pintype "passive"))
      (node (ref "4R_0_0") (pin "8") (pinfunction "2_8") (pintype "passive"))
      (node (ref "LED_0_0") (pin "C") (pinfunction "C_C") (pintype "passive"))
      (node (ref "SHIFT_0") (pin "15") (pinfunction "QA_15") (pintype "tri_state"))
    )
    (net (code "4") (name "/Q0_1") (class "Default")
      (node (ref "4R_0_0") (pin "2") (pinfunction "1_2") (pintype "passive"))
      (node (ref "4R_0_0") (pin "7") (pinfunction "2_7") (pintype "passive"))
      (node (ref "LED_0_1") (pin "C") (pinfunction "C_C") (pintype "passive"))
      (node (ref "SHIFT_0") (pin "1") (pinfunction "QB_1") (pintype "tri_state"))
    )
    (net (code "5") (name "/Q0_2") (class "Default")
      (node (ref "4R_0_0") (pin "3") (pinfunction "1_3") (pintype "passive"))
      (node (ref "4R_0_0") (pin "6") (pinfunction "2_6") (pintype "passive"))
      (node (ref "LED_0_2") (pin "C") (pinfunction "C_C") (pintype "passive"))
      (node (ref "SHIFT_0") (pin "2") (pinfunction "QC_2") (pintype "tri_state"))
    )
    (net (code "6") (name "/Q0_3") (class "Default")
      (node (ref "4R_0_0") (pin "4") (pinfunction "1_4") (pintype "passive"))
      (node (ref "4R_0_0") (pin "5") (pinfunction "2_5") (pintype "passive"))
      (node (ref "LED_0_3") (pin "C") (pinfunction "C_C") (pintype "passive"))
      (node (ref "SHIFT_0") (pin "3") (pinfunction "QD_3") (pintype "tri_state"))
    )
    (net (code "7") (name "/Q0_4") (class "Default")
      (node (ref "4R_0_1") (pin "1") (pinfunction "1_1") (pintype "passive"))
      (node (ref "4R_0_1") (pin "8") (pinfunction "2_8") (pintype "passive"))
      (node (ref "LED_0_4") (pin "C") (pinfunction "C_C") (pintype "passive"))
      (node (ref "SHIFT_0") (pin "4") (pinfunction "QE_4") (pintype "tri_state"))
    )
    (net (code "8") (name "/Q0_5") (class "Default")
      (node (ref "4R_0_1") (pin "2") (pinfunction "1_2") (pintype "passive"))
      (node (ref "4R_0_1") (pin "7") (pinfunction "2_7") (pintype "passive"))
      (node (ref "LED_0_5") (pin "C") (pinfunction "C_C") (pintype "passive"))
      (node (ref "SHIFT_0") (pin "5") (pinfunction "QF_5") (pintype "tri_state"))
    )
    (net (code "9") (name "/Q0_6") (class "Default")
      (node (ref "4R_0_1") (pin "3") (pinfunction "1_3") (pintype "passive"))
      (node (ref "4R_0_1") (pin "6") (pinfunction "2_6") (pintype "passive"))
      (node (ref "LED_0_6") (pin "C") (pinfunction "C_C") (pintype "passive"))
      (node (ref "SHIFT_0") (pin "6") (pinfunction "QG_6") (pintype "tri_state"))
    )
    (net (code "10") (name "/Q0_7") (class "Default")
      (node (ref "4R_0_1") (pin "4") (pinfunction "1_4") (pintype "passive"))
      (node (ref "4R_0_1") (pin "5") (pinfunction "2_5") (pintype "passive"))
      (node (ref "LED_0_7") (pin "C") (pinfunction "C_C") (pintype "passive"))
      (node (ref "SHIFT_0") (pin "7") (pinfunction "QH_7") (pintype "tri_state"))
    )
    (net (code "11") (name "/Q1_0") (class "Default")
      (node (ref "4R_1_0") (pin "1") (pinfunction "1_1") (pintype "passive"))
      (node (ref "4R_1_0") (pin "8") (pinfunction "2_8") (pintype "passive"))
      (node (ref "LED_1_0") (pin "C") (pinfunction "C_C") (pintype "passive"))
      (node (ref "SHIFT_1") (pin "15") (pinfunction "QA_15") (pintype "tri_state"))
    )
    (net (code "12") (name "/Q1_1") (class "Default")
      (node (ref "4R_1_0") (pin "2") (pinfunction "1_2") (pintype "passive"))
      (node (ref "4R_1_0") (pin "7") (pinfunction "2_7") (pintype "passive"))
      (node (ref "LED_1_1") (pin "C") (pinfunction "C_C") (pintype "passive"))
      (node (ref "SHIFT_1") (pin "1") (pinfunction "QB_1") (pintype "tri_state"))
    )
    (net (code "13") (name "/Q1_2") (class "Default")
      (node (ref "4R_1_0") (pin "3") (pinfunction "1_3") (pintype "passive"))
      (node (ref "4R_1_0") (pin "6") (pinfunction "2_6") (pintype "passive"))
      (node (ref "LED_1_2") (pin "C") (pinfunction "C_C") (pintype "passive"))
      (node (ref "SHIFT_1") (pin "2") (pinfunction "QC_2") (pintype "tri_state"))
    )
    (net (code "14") (name "/Q1_3") (class "Default")
      (node (ref "4R_1_0") (pin "4") (pinfunction "1_4") (pintype "passive"))
      (node (ref "4R_1_0") (pin "5") (pinfunction "2_5") (pintype "passive"))
      (node (ref "LED_1_3") (pin "C") (pinfunction "C_C") (pintype "passive"))
      (node (ref "SHIFT_1") (pin "3") (pinfunction "QD_3") (pintype "tri_state"))
    )
    (net (code "15") (name "/Q1_4") (class "Default")
      (node (ref "4R_1_1") (pin "1") (pinfunction "1_1") (pintype "passive"))
      (node (ref "4R_1_1") (pin "8") (pinfunction "2_8") (pintype "passive"))
      (node (ref "LED_1_4") (pin "C") (pinfunction "C_C") (pintype "passive"))
      (node (ref "SHIFT_1") (pin "4") (pinfunction "QE_4") (pintype "tri_state"))
    )
    (net (code "16") (name "/Q1_5") (class "Default")
      (node (ref "4R_1_1") (pin "2") (pinfunction "1_2") (pintype "passive"))
      (node (ref "4R_1_1") (pin "7") (pinfunction "2_7") (pintype "passive"))
      (node (ref "LED_1_5") (pin "C") (pinfunction "C_C") (pintype "passive"))
      (node (ref "SHIFT_1") (pin "5") (pinfunction "QF_5") (pintype "tri_state"))
    )
    (net (code "17") (name "/Q1_6") (class "Default")
      (node (ref "4R_1_1") (pin "3") (pinfunction "1_3") (pintype "passive"))
      (node (ref "4R_1_1") (pin "6") (pinfunction "2_6") (pintype "passive"))
      (node (ref "LED_1_6") (pin "C") (pinfunction "C_C") (pintype "passive"))
      (node (ref "SHIFT_1") (pin "6") (pinfunction "QG_6") (pintype "tri_state"))
    )
    (net (code "18") (name "/Q1_7") (class "Default")
      (node (ref "4R_1_1") (pin "4") (pinfunction "1_4") (pintype "passive"))
      (node (ref "4R_1_1") (pin "5") (pinfunction "2_5") (pintype "passive"))
      (node (ref "LED_1_7") (pin "C") (pinfunction "C_C") (pintype "passive"))
      (node (ref "SHIFT_1") (pin "7") (pinfunction "QH_7") (pintype "tri_state"))
    )
    (net (code "19") (name "/Q2_0") (class "Default")
      (node (ref "4R_2_0") (pin "1") (pinfunction "1_1") (pintype "passive"))
      (node (ref "4R_2_0") (pin "8") (pinfunction "2_8") (pintype "passive"))
      (node (ref "LED_2_0") (pin "C") (pinfunction "C_C") (pintype "passive"))
      (node (ref "SHIFT_2") (pin "15") (pinfunction "QA_15") (pintype "tri_state"))
    )
    (net (code "20") (name "/Q2_1") (class "Default")
      (node (ref "4R_2_0") (pin "2") (pinfunction "1_2") (pintype "passive"))
      (node (ref "4R_2_0") (pin "7") (pinfunction "2_7") (pintype "passive"))
      (node (ref "LED_2_1") (pin "C") (pinfunction "C_C") (pintype "passive"))
      (node (ref "SHIFT_2") (pin "1") (pinfunction "QB_1") (pintype "tri_state"))
    )
    (net (code "21") (name "/Q2_2") (class "Default")
      (node (ref "4R_2_0") (pin "3") (pinfunction "1_3") (pintype "passive"))
      (node (ref "4R_2_0") (pin "6") (pinfunction "2_6") (pintype "passive"))
      (node (ref "LED_2_2") (pin "C") (pinfunction "C_C") (pintype "passive"))
      (node (ref "SHIFT_2") (pin "2") (pinfunction "QC_2") (pintype "tri_state"))
    )
    (net (code "22") (name "/Q2_3") (class "Default")
      (node (ref "4R_2_0") (pin "4") (pinfunction "1_4") (pintype "passive"))
      (node (ref "4R_2_0") (pin "5") (pinfunction "2_5") (pintype "passive"))
      (node (ref "LED_2_3") (pin "C") (pinfunction "C_C") (pintype "passive"))
      (node (ref "SHIFT_2") (pin "3") (pinfunction "QD_3") (pintype "tri_state"))
    )
    (net (code "23") (name "/Q2_4") (class "Default")
      (node (ref "4R_2_1") (pin "1") (pinfunction "1_1") (pintype "passive"))
      (node (ref "4R_2_1") (pin "8") (pinfunction "2_8") (pintype "passive"))
      (node (ref "LED_2_4") (pin "C") (pinfunction "C_C") (pintype "passive"))
      (node (ref "SHIFT_2") (pin "4") (pinfunction "QE_4") (pintype "tri_state"))
    )
    (net (code "24") (name "/Q2_5") (class "Default")
      (node (ref "4R_2_1") (pin "2") (pinfunction "1_2") (pintype "passive"))
      (node (ref "4R_2_1") (pin "7") (pinfunction "2_7") (pintype "passive"))
      (node (ref "LED_2_5") (pin "C") (pinfunction "C_C") (pintype "passive"))
      (node (ref "SHIFT_2") (pin "5") (pinfunction "QF_5") (pintype "tri_state"))
    )
    (net (code "25") (name "/Q2_6") (class "Default")
      (node (ref "4R_2_1") (pin "3") (pinfunction "1_3") (pintype "passive"))
      (node (ref "4R_2_1") (pin "6") (pinfunction "2_6") (pintype "passive"))
      (node (ref "LED_2_6") (pin "C") (pinfunction "C_C") (pintype "passive"))
      (node (ref "SHIFT_2") (pin "6") (pinfunction "QG_6") (pintype "tri_state"))
    )
    (net (code "26") (name "/Q2_7") (class "Default")
      (node (ref "4R_2_1") (pin "4") (pinfunction "1_4") (pintype "passive"))
      (node (ref "4R_2_1") (pin "5") (pinfunction "2_5") (pintype "passive"))
      (node (ref "LED_2_7") (pin "C") (pinfunction "C_C") (pintype "passive"))
      (node (ref "SHIFT_2") (pin "7") (pinfunction "QH_7") (pintype "tri_state"))
    )
    (net (code "27") (name "/Q3_0") (class "Default")
      (node (ref "4R_3_0") (pin "1") (pinfunction "1_1") (pintype "passive"))
      (node (ref "4R_3_0") (pin "8") (pinfunction "2_8") (pintype "passive"))
      (node (ref "LED_3_0") (pin "C") (pinfunction "C_C") (pintype "passive"))
      (node (ref "SHIFT_3") (pin "15") (pinfunction "QA_15") (pintype "tri_state"))
    )
    (net (code "28") (name "/Q3_1") (class "Default")
      (node (ref "4R_3_0") (pin "2") (pinfunction "1_2") (pintype "passive"))
      (node (ref "4R_3_0") (pin "7") (pinfunction "2_7") (pintype "passive"))
      (node (ref "LED_3_1") (pin "C") (pinfunction "C_C") (pintype "passive"))
      (node (ref "SHIFT_3") (pin "1") (pinfunction "QB_1") (pintype "tri_state"))
    )
    (net (code "29") (name "/Q3_2") (class "Default")
      (node (ref "4R_3_0") (pin "3") (pinfunction "1_3") (pintype "passive"))
      (node (ref "4R_3_0") (pin "6") (pinfunction "2_6") (pintype "passive"))
      (node (ref "LED_3_2") (pin "C") (pinfunction "C_C") (pintype "passive"))
      (node (ref "SHIFT_3") (pin "2") (pinfunction "QC_2") (pintype "tri_state"))
    )
    (net (code "30") (name "/Q3_3") (class "Default")
      (node (ref "4R_3_0") (pin "4") (pinfunction "1_4") (pintype "passive"))
      (node (ref "4R_3_0") (pin "5") (pinfunction "2_5") (pintype "passive"))
      (node (ref "LED_3_3") (pin "C") (pinfunction "C_C") (pintype "passive"))
      (node (ref "SHIFT_3") (pin "3") (pinfunction "QD_3") (pintype "tri_state"))
    )
    (net (code "31") (name "/Q3_4") (class "Default")
      (node (ref "4R_3_1") (pin "1") (pinfunction "1_1") (pintype "passive"))
      (node (ref "4R_3_1") (pin "8") (pinfunction "2_8") (pintype "passive"))
      (node (ref "LED_3_4") (pin "C") (pinfunction "C_C") (pintype "passive"))
      (node (ref "SHIFT_3") (pin "4") (pinfunction "QE_4") (pintype "tri_state"))
    )
    (net (code "32") (name "/Q3_5") (class "Default")
      (node (ref "4R_3_1") (pin "2") (pinfunction "1_2") (pintype "passive"))
      (node (ref "4R_3_1") (pin "7") (pinfunction "2_7") (pintype "passive"))
      (node (ref "LED_3_5") (pin "C") (pinfunction "C_C") (pintype "passive"))
      (node (ref "SHIFT_3") (pin "5") (pinfunction "QF_5") (pintype "tri_state"))
    )
    (net (code "33") (name "/Q3_6") (class "Default")
      (node (ref "4R_3_1") (pin "3") (pinfunction "1_3") (pintype "passive"))
      (node (ref "4R_3_1") (pin "6") (pinfunction "2_6") (pintype "passive"))
      (node (ref "LED_3_6") (pin "C") (pinfunction "C_C") (pintype "passive"))
      (node (ref "SHIFT_3") (pin "6") (pinfunction "QG_6") (pintype "tri_state"))
    )
    (net (code "34") (name "/Q3_7") (class "Default")
      (node (ref "4R_3_1") (pin "4") (pinfunction "1_4") (pintype "passive"))
      (node (ref "4R_3_1") (pin "5") (pinfunction "2_5") (pintype "passive"))
      (node (ref "LED_3_7") (pin "C") (pinfunction "C_C") (pintype "passive"))
      (node (ref "SHIFT_3") (pin "7") (pinfunction "QH_7") (pintype "tri_state"))
    )
    (net (code "35") (name "/Q4_0") (class "Default")
      (node (ref "4R_4_0") (pin "1") (pinfunction "1_1") (pintype "passive"))
      (node (ref "4R_4_0") (pin "8") (pinfunction "2_8") (pintype "passive"))
      (node (ref "LED_4_0") (pin "C") (pinfunction "C_C") (pintype "passive"))
      (node (ref "SHIFT_4") (pin "15") (pinfunction "QA_15") (pintype "tri_state"))
    )
    (net (code "36") (name "/Q4_1") (class "Default")
      (node (ref "4R_4_0") (pin "2") (pinfunction "1_2") (pintype "passive"))
      (node (ref "4R_4_0") (pin "7") (pinfunction "2_7") (pintype "passive"))
      (node (ref "LED_4_1") (pin "C") (pinfunction "C_C") (pintype "passive"))
      (node (ref "SHIFT_4") (pin "1") (pinfunction "QB_1") (pintype "tri_state"))
    )
    (net (code "37") (name "/Q4_2") (class "Default")
      (node (ref "4R_4_0") (pin "3") (pinfunction "1_3") (pintype "passive"))
      (node (ref "4R_4_0") (pin "6") (pinfunction "2_6") (pintype "passive"))
      (node (ref "LED_4_2") (pin "C") (pinfunction "C_C") (pintype "passive"))
      (node (ref "SHIFT_4") (pin "2") (pinfunction "QC_2") (pintype "tri_state"))
    )
    (net (code "38") (name "/Q4_3") (class "Default")
      (node (ref "4R_4_0") (pin "4") (pinfunction "1_4") (pintype "passive"))
      (node (ref "4R_4_0") (pin "5") (pinfunction "2_5") (pintype "passive"))
      (node (ref "LED_4_3") (pin "C") (pinfunction "C_C") (pintype "passive"))
      (node (ref "SHIFT_4") (pin "3") (pinfunction "QD_3") (pintype "tri_state"))
    )
    (net (code "39") (name "/Q4_4") (class "Default")
      (node (ref "4R_4_1") (pin "1") (pinfunction "1_1") (pintype "passive"))
      (node (ref "4R_4_1") (pin "8") (pinfunction "2_8") (pintype "passive"))
      (node (ref "LED_4_4") (pin "C") (pinfunction "C_C") (pintype "passive"))
      (node (ref "SHIFT_4") (pin "4") (pinfunction "QE_4") (pintype "tri_state"))
    )
    (net (code "40") (name "/Q4_5") (class "Default")
      (node (ref "4R_4_1") (pin "2") (pinfunction "1_2") (pintype "passive"))
      (node (ref "4R_4_1") (pin "7") (pinfunction "2_7") (pintype "passive"))
      (node (ref "LED_4_5") (pin "C") (pinfunction "C_C") (pintype "passive"))
      (node (ref "SHIFT_4") (pin "5") (pinfunction "QF_5") (pintype "tri_state"))
    )
    (net (code "41") (name "/Q4_6") (class "Default")
      (node (ref "4R_4_1") (pin "3") (pinfunction "1_3") (pintype "passive"))
      (node (ref "4R_4_1") (pin "6") (pinfunction "2_6") (pintype "passive"))
      (node (ref "LED_4_6") (pin "C") (pinfunction "C_C") (pintype "passive"))
      (node (ref "SHIFT_4") (pin "6") (pinfunction "QG_6") (pintype "tri_state"))
    )
    (net (code "42") (name "/Q4_7") (class "Default")
      (node (ref "4R_4_1") (pin "4") (pinfunction "1_4") (pintype "passive"))
      (node (ref "4R_4_1") (pin "5") (pinfunction "2_5") (pintype "passive"))
      (node (ref "LED_4_7") (pin "C") (pinfunction "C_C") (pintype "passive"))
      (node (ref "SHIFT_4") (pin "7") (pinfunction "QH_7") (pintype "tri_state"))
    )
    (net (code "43") (name "/Q5_0") (class "Default")
      (node (ref "4R_5_0") (pin "1") (pinfunction "1_1") (pintype "passive"))
      (node (ref "4R_5_0") (pin "8") (pinfunction "2_8") (pintype "passive"))
      (node (ref "LED_5_0") (pin "C") (pinfunction "C_C") (pintype "passive"))
      (node (ref "SHIFT_5") (pin "15") (pinfunction "QA_15") (pintype "tri_state"))
    )
    (net (code "44") (name "/Q5_1") (class "Default")
      (node (ref "4R_5_0") (pin "2") (pinfunction "1_2") (pintype "passive"))
      (node (ref "4R_5_0") (pin "7") (pinfunction "2_7") (pintype "passive"))
      (node (ref "LED_5_1") (pin "C") (pinfunction "C_C") (pintype "passive"))
      (node (ref "SHIFT_5") (pin "1") (pinfunction "QB_1") (pintype "tri_state"))
    )
    (net (code "45") (name "/Q5_2") (class "Default")
      (node (ref "4R_5_0") (pin "3") (pinfunction "1_3") (pintype "passive"))
      (node (ref "4R_5_0") (pin "6") (pinfunction "2_6") (pintype "passive"))
      (node (ref "LED_5_2") (pin "C") (pinfunction "C_C") (pintype "passive"))
      (node (ref "SHIFT_5") (pin "2") (pinfunction "QC_2") (pintype "tri_state"))
    )
    (net (code "46") (name "/Q5_3") (class "Default")
      (node (ref "4R_5_0") (pin "4") (pinfunction "1_4") (pintype "passive"))
      (node (ref "4R_5_0") (pin "5") (pinfunction "2_5") (pintype "passive"))
      (node (ref "LED_5_3") (pin "C") (pinfunction "C_C") (pintype "passive"))
      (node (ref "SHIFT_5") (pin "3") (pinfunction "QD_3") (pintype "tri_state"))
    )
    (net (code "47") (name "/Q5_4") (class "Default")
      (node (ref "4R_5_1") (pin "1") (pinfunction "1_1") (pintype "passive"))
      (node (ref "4R_5_1") (pin "8") (pinfunction "2_8") (pintype "passive"))
      (node (ref "LED_5_4") (pin "C") (pinfunction "C_C") (pintype "passive"))
      (node (ref "SHIFT_5") (pin "4") (pinfunction "QE_4") (pintype "tri_state"))
    )
    (net (code "48") (name "/Q5_5") (class "Default")
      (node (ref "4R_5_1") (pin "2") (pinfunction "1_2") (pintype "passive"))
      (node (ref "4R_5_1") (pin "7") (pinfunction "2_7") (pintype "passive"))
      (node (ref "LED_5_5") (pin "C") (pinfunction "C_C") (pintype "passive"))
      (node (ref "SHIFT_5") (pin "5") (pinfunction "QF_5") (pintype "tri_state"))
    )
    (net (code "49") (name "/Q5_6") (class "Default")
      (node (ref "4R_5_1") (pin "3") (pinfunction "1_3") (pintype "passive"))
      (node (ref "4R_5_1") (pin "6") (pinfunction "2_6") (pintype "passive"))
      (node (ref "LED_5_6") (pin "C") (pinfunction "C_C") (pintype "passive"))
      (node (ref "SHIFT_5") (pin "6") (pinfunction "QG_6") (pintype "tri_state"))
    )
    (net (code "50") (name "/Q5_7") (class "Default")
      (node (ref "4R_5_1") (pin "4") (pinfunction "1_4") (pintype "passive"))
      (node (ref "4R_5_1") (pin "5") (pinfunction "2_5") (pintype "passive"))
      (node (ref "LED_5_7") (pin "C") (pinfunction "C_C") (pintype "passive"))
      (node (ref "SHIFT_5") (pin "7") (pinfunction "QH_7") (pintype "tri_state"))
    )
    (net (code "51") (name "/Q6_0") (class "Default")
      (node (ref "4R_6_0") (pin "1") (pinfunction "1_1") (pintype "passive"))
      (node (ref "4R_6_0") (pin "8") (pinfunction "2_8") (pintype "passive"))
      (node (ref "LED_6_0") (pin "C") (pinfunction "C_C") (pintype "passive"))
      (node (ref "SHIFT_6") (pin "15") (pinfunction "QA_15") (pintype "tri_state"))
    )
    (net (code "52") (name "/Q6_1") (class "Default")
      (node (ref "4R_6_0") (pin "2") (pinfunction "1_2") (pintype "passive"))
      (node (ref "4R_6_0") (pin "7") (pinfunction "2_7") (pintype "passive"))
      (node (ref "LED_6_1") (pin "C") (pinfunction "C_C") (pintype "passive"))
      (node (ref "SHIFT_6") (pin "1") (pinfunction "QB_1") (pintype "tri_state"))
    )
    (net (code "53") (name "/Q6_2") (class "Default")
      (node (ref "4R_6_0") (pin "3") (pinfunction "1_3") (pintype "passive"))
      (node (ref "4R_6_0") (pin "6") (pinfunction "2_6") (pintype "passive"))
      (node (ref "LED_6_2") (pin "C") (pinfunction "C_C") (pintype "passive"))
      (node (ref "SHIFT_6") (pin "2") (pinfunction "QC_2") (pintype "tri_state"))
    )
    (net (code "54") (name "/Q6_3") (class "Default")
      (node (ref "4R_6_0") (pin "4") (pinfunction "1_4") (pintype "passive"))
      (node (ref "4R_6_0") (pin "5") (pinfunction "2_5") (pintype "passive"))
      (node (ref "LED_6_3") (pin "C") (pinfunction "C_C") (pintype "passive"))
      (node (ref "SHIFT_6") (pin "3") (pinfunction "QD_3") (pintype "tri_state"))
    )
    (net (code "55") (name "/Q6_4") (class "Default")
      (node (ref "4R_6_1") (pin "1") (pinfunction "1_1") (pintype "passive"))
      (node (ref "4R_6_1") (pin "8") (pinfunction "2_8") (pintype "passive"))
      (node (ref "LED_6_4") (pin "C") (pinfunction "C_C") (pintype "passive"))
      (node (ref "SHIFT_6") (pin "4") (pinfunction "QE_4") (pintype "tri_state"))
    )
    (net (code "56") (name "/Q6_5") (class "Default")
      (node (ref "4R_6_1") (pin "2") (pinfunction "1_2") (pintype "passive"))
      (node (ref "4R_6_1") (pin "7") (pinfunction "2_7") (pintype "passive"))
      (node (ref "LED_6_5") (pin "C") (pinfunction "C_C") (pintype "passive"))
      (node (ref "SHIFT_6") (pin "5") (pinfunction "QF_5") (pintype "tri_state"))
    )
    (net (code "57") (name "/Q6_6") (class "Default")
      (node (ref "4R_6_1") (pin "3") (pinfunction "1_3") (pintype "passive"))
      (node (ref "4R_6_1") (pin "6") (pinfunction "2_6") (pintype "passive"))
      (node (ref "LED_6_6") (pin "C") (pinfunction "C_C") (pintype "passive"))
      (node (ref "SHIFT_6") (pin "6") (pinfunction "QG_6") (pintype "tri_state"))
    )
    (net (code "58") (name "/Q6_7") (class "Default")
      (node (ref "4R_6_1") (pin "4") (pinfunction "1_4") (pintype "passive"))
      (node (ref "4R_6_1") (pin "5") (pinfunction "2_5") (pintype "passive"))
      (node (ref "LED_6_7") (pin "C") (pinfunction "C_C") (pintype "passive"))
      (node (ref "SHIFT_6") (pin "7") (pinfunction "QH_7") (pintype "tri_state"))
    )
    (net (code "59") (name "/Q7_0") (class "Default")
      (node (ref "4R_7_0") (pin "1") (pinfunction "1_1") (pintype "passive"))
      (node (ref "4R_7_0") (pin "8") (pinfunction "2_8") (pintype "passive"))
      (node (ref "LED_7_0") (pin "C") (pinfunction "C_C") (pintype "passive"))
      (node (ref "SHIFT_7") (pin "15") (pinfunction "QA_15") (pintype "tri_state"))
    )
    (net (code "60") (name "/Q7_1") (class "Default")
      (node (ref "4R_7_0") (pin "2") (pinfunction "1_2") (pintype "passive"))
      (node (ref "4R_7_0") (pin "7") (pinfunction "2_7") (pintype "passive"))
      (node (ref "LED_7_1") (pin "C") (pinfunction "C_C") (pintype "passive"))
      (node (ref "SHIFT_7") (pin "1") (pinfunction "QB_1") (pintype "tri_state"))
    )
    (net (code "61") (name "/Q7_2") (class "Default")
      (node (ref "4R_7_0") (pin "3") (pinfunction "1_3") (pintype "passive"))
      (node (ref "4R_7_0") (pin "6") (pinfunction "2_6") (pintype "passive"))
      (node (ref "LED_7_2") (pin "C") (pinfunction "C_C") (pintype "passive"))
      (node (ref "SHIFT_7") (pin "2") (pinfunction "QC_2") (pintype "tri_state"))
    )
    (net (code "62") (name "/Q7_3") (class "Default")
      (node (ref "4R_7_0") (pin "4") (pinfunction "1_4") (pintype "passive"))
      (node (ref "4R_7_0") (pin "5") (pinfunction "2_5") (pintype "passive"))
      (node (ref "LED_7_3") (pin "C") (pinfunction "C_C") (pintype "passive"))
      (node (ref "SHIFT_7") (pin "3") (pinfunction "QD_3") (pintype "tri_state"))
    )
    (net (code "63") (name "/Q7_4") (class "Default")
      (node (ref "4R_7_1") (pin "1") (pinfunction "1_1") (pintype "passive"))
      (node (ref "4R_7_1") (pin "8") (pinfunction "2_8") (pintype "passive"))
      (node (ref "LED_7_4") (pin "C") (pinfunction "C_C") (pintype "passive"))
      (node (ref "SHIFT_7") (pin "4") (pinfunction "QE_4") (pintype "tri_state"))
    )
    (net (code "64") (name "/Q7_5") (class "Default")
      (node (ref "4R_7_1") (pin "2") (pinfunction "1_2") (pintype "passive"))
      (node (ref "4R_7_1") (pin "7") (pinfunction "2_7") (pintype "passive"))
      (node (ref "LED_7_5") (pin "C") (pinfunction "C_C") (pintype "passive"))
      (node (ref "SHIFT_7") (pin "5") (pinfunction "QF_5") (pintype "tri_state"))
    )
    (net (code "65") (name "/Q7_6") (class "Default")
      (node (ref "4R_7_1") (pin "3") (pinfunction "1_3") (pintype "passive"))
      (node (ref "4R_7_1") (pin "6") (pinfunction "2_6") (pintype "passive"))
      (node (ref "LED_7_6") (pin "C") (pinfunction "C_C") (pintype "passive"))
      (node (ref "SHIFT_7") (pin "6") (pinfunction "QG_6") (pintype "tri_state"))
    )
    (net (code "66") (name "/Q7_7") (class "Default")
      (node (ref "4R_7_1") (pin "4") (pinfunction "1_4") (pintype "passive"))
      (node (ref "4R_7_1") (pin "5") (pinfunction "2_5") (pintype "passive"))
      (node (ref "LED_7_7") (pin "C") (pinfunction "C_C") (pintype "passive"))
      (node (ref "SHIFT_7") (pin "7") (pinfunction "QH_7") (pintype "tri_state"))
    )
    (net (code "67") (name "/Q8_0") (class "Default")
      (node (ref "4R_8_0") (pin "1") (pinfunction "1_1") (pintype "passive"))
      (node (ref "4R_8_0") (pin "8") (pinfunction "2_8") (pintype "passive"))
      (node (ref "LED_8_0") (pin "C") (pinfunction "C_C") (pintype "passive"))
      (node (ref "SHIFT_8") (pin "15") (pinfunction "QA_15") (pintype "tri_state"))
    )
    (net (code "68") (name "/Q8_1") (class "Default")
      (node (ref "4R_8_0") (pin "2") (pinfunction "1_2") (pintype "passive"))
      (node (ref "4R_8_0") (pin "7") (pinfunction "2_7") (pintype "passive"))
      (node (ref "LED_8_1") (pin "C") (pinfunction "C_C") (pintype "passive"))
      (node (ref "SHIFT_8") (pin "1") (pinfunction "QB_1") (pintype "tri_state"))
    )
    (net (code "69") (name "/Q8_2") (class "Default")
      (node (ref "4R_8_0") (pin "3") (pinfunction "1_3") (pintype "passive"))
      (node (ref "4R_8_0") (pin "6") (pinfunction "2_6") (pintype "passive"))
      (node (ref "LED_8_2") (pin "C") (pinfunction "C_C") (pintype "passive"))
      (node (ref "SHIFT_8") (pin "2") (pinfunction "QC_2") (pintype "tri_state"))
    )
    (net (code "70") (name "/Q8_3") (class "Default")
      (node (ref "4R_8_0") (pin "4") (pinfunction "1_4") (pintype "passive"))
      (node (ref "4R_8_0") (pin "5") (pinfunction "2_5") (pintype "passive"))
      (node (ref "LED_8_3") (pin "C") (pinfunction "C_C") (pintype "passive"))
      (node (ref "SHIFT_8") (pin "3") (pinfunction "QD_3") (pintype "tri_state"))
    )
    (net (code "71") (name "/Q8_4") (class "Default")
      (node (ref "4R_8_1") (pin "1") (pinfunction "1_1") (pintype "passive"))
      (node (ref "4R_8_1") (pin "8") (pinfunction "2_8") (pintype "passive"))
      (node (ref "LED_8_4") (pin "C") (pinfunction "C_C") (pintype "passive"))
      (node (ref "SHIFT_8") (pin "4") (pinfunction "QE_4") (pintype "tri_state"))
    )
    (net (code "72") (name "/Q8_5") (class "Default")
      (node (ref "4R_8_1") (pin "2") (pinfunction "1_2") (pintype "passive"))
      (node (ref "4R_8_1") (pin "7") (pinfunction "2_7") (pintype "passive"))
      (node (ref "LED_8_5") (pin "C") (pinfunction "C_C") (pintype "passive"))
      (node (ref "SHIFT_8") (pin "5") (pinfunction "QF_5") (pintype "tri_state"))
    )
    (net (code "73") (name "/Q8_6") (class "Default")
      (node (ref "4R_8_1") (pin "3") (pinfunction "1_3") (pintype "passive"))
      (node (ref "4R_8_1") (pin "6") (pinfunction "2_6") (pintype "passive"))
      (node (ref "LED_8_6") (pin "C") (pinfunction "C_C") (pintype "passive"))
      (node (ref "SHIFT_8") (pin "6") (pinfunction "QG_6") (pintype "tri_state"))
    )
    (net (code "74") (name "/Q8_7") (class "Default")
      (node (ref "4R_8_1") (pin "4") (pinfunction "1_4") (pintype "passive"))
      (node (ref "4R_8_1") (pin "5") (pinfunction "2_5") (pintype "passive"))
      (node (ref "LED_8_7") (pin "C") (pinfunction "C_C") (pintype "passive"))
      (node (ref "SHIFT_8") (pin "7") (pinfunction "QH_7") (pintype "tri_state"))
    )
    (net (code "75") (name "/Q9_0") (class "Default")
      (node (ref "4R_9_0") (pin "1") (pinfunction "1_1") (pintype "passive"))
      (node (ref "4R_9_0") (pin "8") (pinfunction "2_8") (pintype "passive"))
      (node (ref "LED_9_0") (pin "C") (pinfunction "C_C") (pintype "passive"))
      (node (ref "SHIFT_9") (pin "15") (pinfunction "QA_15") (pintype "tri_state"))
    )
    (net (code "76") (name "/Q9_1") (class "Default")
      (node (ref "4R_9_0") (pin "2") (pinfunction "1_2") (pintype "passive"))
      (node (ref "4R_9_0") (pin "7") (pinfunction "2_7") (pintype "passive"))
      (node (ref "LED_9_1") (pin "C") (pinfunction "C_C") (pintype "passive"))
      (node (ref "SHIFT_9") (pin "1") (pinfunction "QB_1") (pintype "tri_state"))
    )
    (net (code "77") (name "/Q9_2") (class "Default")
      (node (ref "4R_9_0") (pin "3") (pinfunction "1_3") (pintype "passive"))
      (node (ref "4R_9_0") (pin "6") (pinfunction "2_6") (pintype "passive"))
      (node (ref "LED_9_2") (pin "C") (pinfunction "C_C") (pintype "passive"))
      (node (ref "SHIFT_9") (pin "2") (pinfunction "QC_2") (pintype "tri_state"))
    )
    (net (code "78") (name "/Q9_3") (class "Default")
      (node (ref "4R_9_0") (pin "4") (pinfunction "1_4") (pintype "passive"))
      (node (ref "4R_9_0") (pin "5") (pinfunction "2_5") (pintype "passive"))
      (node (ref "LED_9_3") (pin "C") (pinfunction "C_C") (pintype "passive"))
      (node (ref "SHIFT_9") (pin "3") (pinfunction "QD_3") (pintype "tri_state"))
    )
    (net (code "79") (name "/Q9_4") (class "Default")
      (node (ref "4R_9_1") (pin "1") (pinfunction "1_1") (pintype "passive"))
      (node (ref "4R_9_1") (pin "8") (pinfunction "2_8") (pintype "passive"))
      (node (ref "LED_9_4") (pin "C") (pinfunction "C_C") (pintype "passive"))
      (node (ref "SHIFT_9") (pin "4") (pinfunction "QE_4") (pintype "tri_state"))
    )
    (net (code "80") (name "/Q9_5") (class "Default")
      (node (ref "4R_9_1") (pin "2") (pinfunction "1_2") (pintype "passive"))
      (node (ref "4R_9_1") (pin "7") (pinfunction "2_7") (pintype "passive"))
      (node (ref "LED_9_5") (pin "C") (pinfunction "C_C") (pintype "passive"))
      (node (ref "SHIFT_9") (pin "5") (pinfunction "QF_5") (pintype "tri_state"))
    )
    (net (code "81") (name "/Q9_6") (class "Default")
      (node (ref "4R_9_1") (pin "3") (pinfunction "1_3") (pintype "passive"))
      (node (ref "4R_9_1") (pin "6") (pinfunction "2_6") (pintype "passive"))
      (node (ref "LED_9_6") (pin "C") (pinfunction "C_C") (pintype "passive"))
      (node (ref "SHIFT_9") (pin "6") (pinfunction "QG_6") (pintype "tri_state"))
    )
    (net (code "82") (name "/Q9_7") (class "Default")
      (node (ref "4R_9_1") (pin "4") (pinfunction "1_4") (pintype "passive"))
      (node (ref "4R_9_1") (pin "5") (pinfunction "2_5") (pintype "passive"))
      (node (ref "LED_9_7") (pin "C") (pinfunction "C_C") (pintype "passive"))
      (node (ref "SHIFT_9") (pin "7") (pinfunction "QH_7") (pintype "tri_state"))
    )
    (net (code "83") (name "/Q10_0") (class "Default")
      (node (ref "4R_10_0") (pin "1") (pinfunction "1_1") (pintype "passive"))
      (node (ref "4R_10_0") (pin "8") (pinfunction "2_8") (pintype "passive"))
      (node (ref "LED_10_0") (pin "C") (pinfunction "C_C") (pintype "passive"))
      (node (ref "SHIFT_10") (pin "15") (pinfunction "QA_15") (pintype "tri_state"))
    )
    (net (code "84") (name "/Q10_1") (class "Default")
      (node (ref "4R_10_0") (pin "2") (pinfunction "1_2") (pintype "passive"))
      (node (ref "4R_10_0") (pin "7") (pinfunction "2_7") (pintype "passive"))
      (node (ref "LED_10_1") (pin "C") (pinfunction "C_C") (pintype "passive"))
      (node (ref "SHIFT_10") (pin "1") (pinfunction "QB_1") (pintype "tri_state"))
    )
    (net (code "85") (name "/Q10_2") (class "Default")
      (node (ref "4R_10_0") (pin "3") (pinfunction "1_3") (pintype "passive"))
      (node (ref "4R_10_0") (pin "6") (pinfunction "2_6") (pintype "passive"))
      (node (ref "LED_10_2") (pin "C") (pinfunction "C_C") (pintype "passive"))
      (node (ref "SHIFT_10") (pin "2") (pinfunction "QC_2") (pintype "tri_state"))
    )
    (net (code "86") (name "/Q10_3") (class "Default")
      (node (ref "4R_10_0") (pin "4") (pinfunction "1_4") (pintype "passive"))
      (node (ref "4R_10_0") (pin "5") (pinfunction "2_5") (pintype "passive"))
      (node (ref "LED_10_3") (pin "C") (pinfunction "C_C") (pintype "passive"))
      (node (ref "SHIFT_10") (pin "3") (pinfunction "QD_3") (pintype "tri_state"))
    )
    (net (code "87") (name "/Q10_4") (class "Default")
      (node (ref "4R_10_1") (pin "1") (pinfunction "1_1") (pintype "passive"))
      (node (ref "4R_10_1") (pin "8") (pinfunction "2_8") (pintype "passive"))
      (node (ref "LED_10_4") (pin "C") (pinfunction "C_C") (pintype "passive"))
      (node (ref "SHIFT_10") (pin "4") (pinfunction "QE_4") (pintype "tri_state"))
    )
    (net (code "88") (name "/Q10_5") (class "Default")
      (node (ref "4R_10_1") (pin "2") (pinfunction "1_2") (pintype "passive"))
      (node (ref "4R_10_1") (pin "7") (pinfunction "2_7") (pintype "passive"))
      (node (ref "LED_10_5") (pin "C") (pinfunction "C_C") (pintype "passive"))
      (node (ref "SHIFT_10") (pin "5") (pinfunction "QF_5") (pintype "tri_state"))
    )
    (net (code "89") (name "/Q10_6") (class "Default")
      (node (ref "4R_10_1") (pin "3") (pinfunction "1_3") (pintype "passive"))
      (node (ref "4R_10_1") (pin "6") (pinfunction "2_6") (pintype "passive"))
      (node (ref "LED_10_6") (pin "C") (pinfunction "C_C") (pintype "passive"))
      (node (ref "SHIFT_10") (pin "6") (pinfunction "QG_6") (pintype "tri_state"))
    )
    (net (code "90") (name "/Q10_7") (class "Default")
      (node (ref "4R_10_1") (pin "4") (pinfunction "1_4") (pintype "passive"))
      (node (ref "4R_10_1") (pin "5") (pinfunction "2_5") (pintype "passive"))
      (node (ref "LED_10_7") (pin "C") (pinfunction "C_C") (pintype "passive"))
      (node (ref "SHIFT_10") (pin "7") (pinfunction "QH_7") (pintype "tri_state"))
    )
    (net (code "91") (name "/Q11_0") (class "Default")
      (node (ref "4R_11_0") (pin "1") (pinfunction "1_1") (pintype "passive"))
      (node (ref "4R_11_0") (pin "8") (pinfunction "2_8") (pintype "passive"))
      (node (ref "LED_11_0") (pin "C") (pinfunction "C_C") (pintype "passive"))
      (node (ref "SHIFT_11") (pin "15") (pinfunction "QA_15") (pintype "tri_state"))
    )
    (net (code "92") (name "/Q11_1") (class "Default")
      (node (ref "4R_11_0") (pin "2") (pinfunction "1_2") (pintype "passive"))
      (node (ref "4R_11_0") (pin "7") (pinfunction "2_7") (pintype "passive"))
      (node (ref "LED_11_1") (pin "C") (pinfunction "C_C") (pintype "passive"))
      (node (ref "SHIFT_11") (pin "1") (pinfunction "QB_1") (pintype "tri_state"))
    )
    (net (code "93") (name "/Q11_2") (class "Default")
      (node (ref "4R_11_0") (pin "3") (pinfunction "1_3") (pintype "passive"))
      (node (ref "4R_11_0") (pin "6") (pinfunction "2_6") (pintype "passive"))
      (node (ref "LED_11_2") (pin "C") (pinfunction "C_C") (pintype "passive"))
      (node (ref "SHIFT_11") (pin "2") (pinfunction "QC_2") (pintype "tri_state"))
    )
    (net (code "94") (name "/Q11_3") (class "Default")
      (node (ref "4R_11_0") (pin "4") (pinfunction "1_4") (pintype "passive"))
      (node (ref "4R_11_0") (pin "5") (pinfunction "2_5") (pintype "passive"))
      (node (ref "LED_11_3") (pin "C") (pinfunction "C_C") (pintype "passive"))
      (node (ref "SHIFT_11") (pin "3") (pinfunction "QD_3") (pintype "tri_state"))
    )
    (net (code "95") (name "/Q11_4") (class "Default")
      (node (ref "4R_11_1") (pin "1") (pinfunction "1_1") (pintype "passive"))
      (node (ref "4R_11_1") (pin "8") (pinfunction "2_8") (pintype "passive"))
      (node (ref "LED_11_4") (pin "C") (pinfunction "C_C") (pintype "passive"))
      (node (ref "SHIFT_11") (pin "4") (pinfunction "QE_4") (pintype "tri_state"))
    )
    (net (code "96") (name "/Q11_5") (class "Default")
      (node (ref "4R_11_1") (pin "2") (pinfunction "1_2") (pintype "passive"))
      (node (ref "4R_11_1") (pin "7") (pinfunction "2_7") (pintype "passive"))
      (node (ref "LED_11_5") (pin "C") (pinfunction "C_C") (pintype "passive"))
      (node (ref "SHIFT_11") (pin "5") (pinfunction "QF_5") (pintype "tri_state"))
    )
    (net (code "97") (name "/Q11_6") (class "Default")
      (node (ref "4R_11_1") (pin "3") (pinfunction "1_3") (pintype "passive"))
      (node (ref "4R_11_1") (pin "6") (pinfunction "2_6") (pintype "passive"))
      (node (ref "LED_11_6") (pin "C") (pinfunction "C_C") (pintype "passive"))
      (node (ref "SHIFT_11") (pin "6") (pinfunction "QG_6") (pintype "tri_state"))
    )
    (net (code "98") (name "/Q11_7") (class "Default")
      (node (ref "4R_11_1") (pin "4") (pinfunction "1_4") (pintype "passive"))
      (node (ref "4R_11_1") (pin "5") (pinfunction "2_5") (pintype "passive"))
      (node (ref "LED_11_7") (pin "C") (pinfunction "C_C") (pintype "passive"))
      (node (ref "SHIFT_11") (pin "7") (pinfunction "QH_7") (pintype "tri_state"))
    )
    (net (code "99") (name "/Q12_0") (class "Default")
      (node (ref "4R_12_0") (pin "1") (pinfunction "1_1") (pintype "passive"))
      (node (ref "4R_12_0") (pin "8") (pinfunction "2_8") (pintype "passive"))
      (node (ref "LED_12_0") (pin "C") (pinfunction "C_C") (pintype "passive"))
      (node (ref "SHIFT_12") (pin "15") (pinfunction "QA_15") (pintype "tri_state"))
    )
    (net (code "100") (name "/Q12_1") (class "Default")
      (node (ref "4R_12_0") (pin "2") (pinfunction "1_2") (pintype "passive"))
      (node (ref "4R_12_0") (pin "7") (pinfunction "2_7") (pintype "passive"))
      (node (ref "LED_12_1") (pin "C") (pinfunction "C_C") (pintype "passive"))
      (node (ref "SHIFT_12") (pin "1") (pinfunction "QB_1") (pintype "tri_state"))
    )
    (net (code "101") (name "/Q12_2") (class "Default")
      (node (ref "4R_12_0") (pin "3") (pinfunction "1_3") (pintype "passive"))
      (node (ref "4R_12_0") (pin "6") (pinfunction "2_6") (pintype "passive"))
      (node (ref "LED_12_2") (pin "C") (pinfunction "C_C") (pintype "passive"))
      (node (ref "SHIFT_12") (pin "2") (pinfunction "QC_2") (pintype "tri_state"))
    )
    (net (code "102") (name "/Q12_3") (class "Default")
      (node (ref "4R_12_0") (pin "4") (pinfunction "1_4") (pintype "passive"))
      (node (ref "4R_12_0") (pin "5") (pinfunction "2_5") (pintype "passive"))
      (node (ref "LED_12_3") (pin "C") (pinfunction "C_C") (pintype "passive"))
      (node (ref "SHIFT_12") (pin "3") (pinfunction "QD_3") (pintype "tri_state"))
    )
    (net (code "103") (name "/Q12_4") (class "Default")
      (node (ref "4R_12_1") (pin "1") (pinfunction "1_1") (pintype "passive"))
      (node (ref "4R_12_1") (pin "8") (pinfunction "2_8") (pintype "passive"))
      (node (ref "LED_12_4") (pin "C") (pinfunction "C_C") (pintype "passive"))
      (node (ref "SHIFT_12") (pin "4") (pinfunction "QE_4") (pintype "tri_state"))
    )
    (net (code "104") (name "/Q12_5") (class "Default")
      (node (ref "4R_12_1") (pin "2") (pinfunction "1_2") (pintype "passive"))
      (node (ref "4R_12_1") (pin "7") (pinfunction "2_7") (pintype "passive"))
      (node (ref "LED_12_5") (pin "C") (pinfunction "C_C") (pintype "passive"))
      (node (ref "SHIFT_12") (pin "5") (pinfunction "QF_5") (pintype "tri_state"))
    )
    (net (code "105") (name "/Q12_6") (class "Default")
      (node (ref "4R_12_1") (pin "3") (pinfunction "1_3") (pintype "passive"))
      (node (ref "4R_12_1") (pin "6") (pinfunction "2_6") (pintype "passive"))
      (node (ref "LED_12_6") (pin "C") (pinfunction "C_C") (pintype "passive"))
      (node (ref "SHIFT_12") (pin "6") (pinfunction "QG_6") (pintype "tri_state"))
    )
    (net (code "106") (name "/Q12_7") (class "Default")
      (node (ref "4R_12_1") (pin "4") (pinfunction "1_4") (pintype "passive"))
      (node (ref "4R_12_1") (pin "5") (pinfunction "2_5") (pintype "passive"))
      (node (ref "LED_12_7") (pin "C") (pinfunction "C_C") (pintype "passive"))
      (node (ref "SHIFT_12") (pin "7") (pinfunction "QH_7") (pintype "tri_state"))
    )
    (net (code "107") (name "/Q13_0") (class "Default")
      (node (ref "4R_13_0") (pin "1") (pinfunction "1_1") (pintype "passive"))
      (node (ref "4R_13_0") (pin "8") (pinfunction "2_8") (pintype "passive"))
      (node (ref "LED_13_0") (pin "C") (pinfunction "C_C") (pintype "passive"))
      (node (ref "SHIFT_13") (pin "15") (pinfunction "QA_15") (pintype "tri_state"))
    )
    (net (code "108") (name "/Q13_1") (class "Default")
      (node (ref "4R_13_0") (pin "2") (pinfunction "1_2") (pintype "passive"))
      (node (ref "4R_13_0") (pin "7") (pinfunction "2_7") (pintype "passive"))
      (node (ref "LED_13_1") (pin "C") (pinfunction "C_C") (pintype "passive"))
      (node (ref "SHIFT_13") (pin "1") (pinfunction "QB_1") (pintype "tri_state"))
    )
    (net (code "109") (name "/Q13_2") (class "Default")
      (node (ref "4R_13_0") (pin "3") (pinfunction "1_3") (pintype "passive"))
      (node (ref "4R_13_0") (pin "6") (pinfunction "2_6") (pintype "passive"))
      (node (ref "LED_13_2") (pin "C") (pinfunction "C_C") (pintype "passive"))
      (node (ref "SHIFT_13") (pin "2") (pinfunction "QC_2") (pintype "tri_state"))
    )
    (net (code "110") (name "/Q13_3") (class "Default")
      (node (ref "4R_13_0") (pin "4") (pinfunction "1_4") (pintype "passive"))
      (node (ref "4R_13_0") (pin "5") (pinfunction "2_5") (pintype "passive"))
      (node (ref "LED_13_3") (pin "C") (pinfunction "C_C") (pintype "passive"))
      (node (ref "SHIFT_13") (pin "3") (pinfunction "QD_3") (pintype "tri_state"))
    )
    (net (code "111") (name "/Q13_4") (class "Default")
      (node (ref "4R_13_1") (pin "1") (pinfunction "1_1") (pintype "passive"))
      (node (ref "4R_13_1") (pin "8") (pinfunction "2_8") (pintype "passive"))
      (node (ref "LED_13_4") (pin "C") (pinfunction "C_C") (pintype "passive"))
      (node (ref "SHIFT_13") (pin "4") (pinfunction "QE_4") (pintype "tri_state"))
    )
    (net (code "112") (name "/Q13_5") (class "Default")
      (node (ref "4R_13_1") (pin "2") (pinfunction "1_2") (pintype "passive"))
      (node (ref "4R_13_1") (pin "7") (pinfunction "2_7") (pintype "passive"))
      (node (ref "LED_13_5") (pin "C") (pinfunction "C_C") (pintype "passive"))
      (node (ref "SHIFT_13") (pin "5") (pinfunction "QF_5") (pintype "tri_state"))
    )
    (net (code "113") (name "/Q13_6") (class "Default")
      (node (ref "4R_13_1") (pin "3") (pinfunction "1_3") (pintype "passive"))
      (node (ref "4R_13_1") (pin "6") (pinfunction "2_6") (pintype "passive"))
      (node (ref "LED_13_6") (pin "C") (pinfunction "C_C") (pintype "passive"))
      (node (ref "SHIFT_13") (pin "6") (pinfunction "QG_6") (pintype "tri_state"))
    )
    (net (code "114") (name "/Q13_7") (class "Default")
      (node (ref "4R_13_1") (pin "4") (pinfunction "1_4") (pintype "passive"))
      (node (ref "4R_13_1") (pin "5") (pinfunction "2_5") (pintype "passive"))
      (node (ref "LED_13_7") (pin "C") (pinfunction "C_C") (pintype "passive"))
      (node (ref "SHIFT_13") (pin "7") (pinfunction "QH_7") (pintype "tri_state"))
    )
    (net (code "115") (name "/Q14_0") (class "Default")
      (node (ref "4R_14_0") (pin "1") (pinfunction "1_1") (pintype "passive"))
      (node (ref "4R_14_0") (pin "8") (pinfunction "2_8") (pintype "passive"))
      (node (ref "LED_14_0") (pin "C") (pinfunction "C_C") (pintype "passive"))
      (node (ref "SHIFT_14") (pin "15") (pinfunction "QA_15") (pintype "tri_state"))
    )
    (net (code "116") (name "/Q14_1") (class "Default")
      (node (ref "4R_14_0") (pin "2") (pinfunction "1_2") (pintype "passive"))
      (node (ref "4R_14_0") (pin "7") (pinfunction "2_7") (pintype "passive"))
      (node (ref "LED_14_1") (pin "C") (pinfunction "C_C") (pintype "passive"))
      (node (ref "SHIFT_14") (pin "1") (pinfunction "QB_1") (pintype "tri_state"))
    )
    (net (code "117") (name "/Q14_2") (class "Default")
      (node (ref "4R_14_0") (pin "3") (pinfunction "1_3") (pintype "passive"))
      (node (ref "4R_14_0") (pin "6") (pinfunction "2_6") (pintype "passive"))
      (node (ref "LED_14_2") (pin "C") (pinfunction "C_C") (pintype "passive"))
      (node (ref "SHIFT_14") (pin "2") (pinfunction "QC_2") (pintype "tri_state"))
    )
    (net (code "118") (name "/Q14_3") (class "Default")
      (node (ref "4R_14_0") (pin "4") (pinfunction "1_4") (pintype "passive"))
      (node (ref "4R_14_0") (pin "5") (pinfunction "2_5") (pintype "passive"))
      (node (ref "LED_14_3") (pin "C") (pinfunction "C_C") (pintype "passive"))
      (node (ref "SHIFT_14") (pin "3") (pinfunction "QD_3") (pintype "tri_state"))
    )
    (net (code "119") (name "/Q14_4") (class "Default")
      (node (ref "4R_14_1") (pin "1") (pinfunction "1_1") (pintype "passive"))
      (node (ref "4R_14_1") (pin "8") (pinfunction "2_8") (pintype "passive"))
      (node (ref "LED_14_4") (pin "C") (pinfunction "C_C") (pintype "passive"))
      (node (ref "SHIFT_14") (pin "4") (pinfunction "QE_4") (pintype "tri_state"))
    )
    (net (code "120") (name "/Q14_5") (class "Default")
      (node (ref "4R_14_1") (pin "2") (pinfunction "1_2") (pintype "passive"))
      (node (ref "4R_14_1") (pin "7") (pinfunction "2_7") (pintype "passive"))
      (node (ref "LED_14_5") (pin "C") (pinfunction "C_C") (pintype "passive"))
      (node (ref "SHIFT_14") (pin "5") (pinfunction "QF_5") (pintype "tri_state"))
    )
    (net (code "121") (name "/Q14_6") (class "Default")
      (node (ref "4R_14_1") (pin "3") (pinfunction "1_3") (pintype "passive"))
      (node (ref "4R_14_1") (pin "6") (pinfunction "2_6") (pintype "passive"))
      (node (ref "LED_14_6") (pin "C") (pinfunction "C_C") (pintype "passive"))
      (node (ref "SHIFT_14") (pin "6") (pinfunction "QG_6") (pintype "tri_state"))
    )
    (net (code "122") (name "/Q14_7") (class "Default")
      (node (ref "4R_14_1") (pin "4") (pinfunction "1_4") (pintype "passive"))
      (node (ref "4R_14_1") (pin "5") (pinfunction "2_5") (pintype "passive"))
      (node (ref "LED_14_7") (pin "C") (pinfunction "C_C") (pintype "passive"))
      (node (ref "SHIFT_14") (pin "7") (pinfunction "QH_7") (pintype "tri_state"))
    )
    (net (code "123") (name "/Q15_0") (class "Default")
      (node (ref "4R_15_0") (pin "1") (pinfunction "1_1") (pintype "passive"))
      (node (ref "4R_15_0") (pin "8") (pinfunction "2_8") (pintype "passive"))
      (node (ref "LED_15_0") (pin "C") (pinfunction "C_C") (pintype "passive"))
      (node (ref "SHIFT_15") (pin "15") (pinfunction "QA_15") (pintype "tri_state"))
    )
    (net (code "124") (name "/Q15_1") (class "Default")
      (node (ref "4R_15_0") (pin "2") (pinfunction "1_2") (pintype "passive"))
      (node (ref "4R_15_0") (pin "7") (pinfunction "2_7") (pintype "passive"))
      (node (ref "LED_15_1") (pin "C") (pinfunction "C_C") (pintype "passive"))
      (node (ref "SHIFT_15") (pin "1") (pinfunction "QB_1") (pintype "tri_state"))
    )
    (net (code "125") (name "/Q15_2") (class "Default")
      (node (ref "4R_15_0") (pin "3") (pinfunction "1_3") (pintype "passive"))
      (node (ref "4R_15_0") (pin "6") (pinfunction "2_6") (pintype "passive"))
      (node (ref "LED_15_2") (pin "C") (pinfunction "C_C") (pintype "passive"))
      (node (ref "SHIFT_15") (pin "2") (pinfunction "QC_2") (pintype "tri_state"))
    )
    (net (code "126") (name "/Q15_3") (class "Default")
      (node (ref "4R_15_0") (pin "4") (pinfunction "1_4") (pintype "passive"))
      (node (ref "4R_15_0") (pin "5") (pinfunction "2_5") (pintype "passive"))
      (node (ref "LED_15_3") (pin "C") (pinfunction "C_C") (pintype "passive"))
      (node (ref "SHIFT_15") (pin "3") (pinfunction "QD_3") (pintype "tri_state"))
    )
    (net (code "127") (name "/Q15_4") (class "Default")
      (node (ref "4R_15_1") (pin "1") (pinfunction "1_1") (pintype "passive"))
      (node (ref "4R_15_1") (pin "8") (pinfunction "2_8") (pintype "passive"))
      (node (ref "LED_15_4") (pin "C") (pinfunction "C_C") (pintype "passive"))
      (node (ref "SHIFT_15") (pin "4") (pinfunction "QE_4") (pintype "tri_state"))
    )
    (net (code "128") (name "/Q15_5") (class "Default")
      (node (ref "4R_15_1") (pin "2") (pinfunction "1_2") (pintype "passive"))
      (node (ref "4R_15_1") (pin "7") (pinfunction "2_7") (pintype "passive"))
      (node (ref "LED_15_5") (pin "C") (pinfunction "C_C") (pintype "passive"))
      (node (ref "SHIFT_15") (pin "5") (pinfunction "QF_5") (pintype "tri_state"))
    )
    (net (code "129") (name "/Q15_6") (class "Default")
      (node (ref "4R_15_1") (pin "3") (pinfunction "1_3") (pintype "passive"))
      (node (ref "4R_15_1") (pin "6") (pinfunction "2_6") (pintype "passive"))
      (node (ref "LED_15_6") (pin "C") (pinfunction "C_C") (pintype "passive"))
      (node (ref "SHIFT_15") (pin "6") (pinfunction "QG_6") (pintype "tri_state"))
    )
    (net (code "130") (name "/Q15_7") (class "Default")
      (node (ref "4R_15_1") (pin "4") (pinfunction "1_4") (pintype "passive"))
      (node (ref "4R_15_1") (pin "5") (pinfunction "2_5") (pintype "passive"))
      (node (ref "LED_15_7") (pin "C") (pinfunction "C_C") (pintype "passive"))
      (node (ref "SHIFT_15") (pin "7") (pinfunction "QH_7") (pintype "tri_state"))
    )
    (net (code "131") (name "/Q16_0") (class "Default")
      (node (ref "4R_16_0") (pin "1") (pinfunction "1_1") (pintype "passive"))
      (node (ref "4R_16_0") (pin "8") (pinfunction "2_8") (pintype "passive"))
      (node (ref "LED_16_0") (pin "C") (pinfunction "C_C") (pintype "passive"))
      (node (ref "SHIFT_16") (pin "15") (pinfunction "QA_15") (pintype "tri_state"))
    )
    (net (code "132") (name "/Q16_1") (class "Default")
      (node (ref "4R_16_0") (pin "2") (pinfunction "1_2") (pintype "passive"))
      (node (ref "4R_16_0") (pin "7") (pinfunction "2_7") (pintype "passive"))
      (node (ref "LED_16_1") (pin "C") (pinfunction "C_C") (pintype "passive"))
      (node (ref "SHIFT_16") (pin "1") (pinfunction "QB_1") (pintype "tri_state"))
    )
    (net (code "133") (name "/Q16_2") (class "Default")
      (node (ref "4R_16_0") (pin "3") (pinfunction "1_3") (pintype "passive"))
      (node (ref "4R_16_0") (pin "6") (pinfunction "2_6") (pintype "passive"))
      (node (ref "LED_16_2") (pin "C") (pinfunction "C_C") (pintype "passive"))
      (node (ref "SHIFT_16") (pin "2") (pinfunction "QC_2") (pintype "tri_state"))
    )
    (net (code "134") (name "/Q16_3") (class "Default")
      (node (ref "4R_16_0") (pin "4") (pinfunction "1_4") (pintype "passive"))
      (node (ref "4R_16_0") (pin "5") (pinfunction "2_5") (pintype "passive"))
      (node (ref "LED_16_3") (pin "C") (pinfunction "C_C") (pintype "passive"))
      (node (ref "SHIFT_16") (pin "3") (pinfunction "QD_3") (pintype "tri_state"))
    )
    (net (code "135") (name "/Q16_4") (class "Default")
      (node (ref "4R_16_1") (pin "1") (pinfunction "1_1") (pintype "passive"))
      (node (ref "4R_16_1") (pin "8") (pinfunction "2_8") (pintype "passive"))
      (node (ref "LED_16_4") (pin "C") (pinfunction "C_C") (pintype "passive"))
      (node (ref "SHIFT_16") (pin "4") (pinfunction "QE_4") (pintype "tri_state"))
    )
    (net (code "136") (name "/Q16_5") (class "Default")
      (node (ref "4R_16_1") (pin "2") (pinfunction "1_2") (pintype "passive"))
      (node (ref "4R_16_1") (pin "7") (pinfunction "2_7") (pintype "passive"))
      (node (ref "LED_16_5") (pin "C") (pinfunction "C_C") (pintype "passive"))
      (node (ref "SHIFT_16") (pin "5") (pinfunction "QF_5") (pintype "tri_state"))
    )
    (net (code "137") (name "/Q16_6") (class "Default")
      (node (ref "4R_16_1") (pin "3") (pinfunction "1_3") (pintype "passive"))
      (node (ref "4R_16_1") (pin "6") (pinfunction "2_6") (pintype "passive"))
      (node (ref "LED_16_6") (pin "C") (pinfunction "C_C") (pintype "passive"))
      (node (ref "SHIFT_16") (pin "6") (pinfunction "QG_6") (pintype "tri_state"))
    )
    (net (code "138") (name "/Q16_7") (class "Default")
      (node (ref "4R_16_1") (pin "4") (pinfunction "1_4") (pintype "passive"))
      (node (ref "4R_16_1") (pin "5") (pinfunction "2_5") (pintype "passive"))
      (node (ref "LED_16_7") (pin "C") (pinfunction "C_C") (pintype "passive"))
      (node (ref "SHIFT_16") (pin "7") (pinfunction "QH_7") (pintype "tri_state"))
    )
    (net (code "139") (name "/Q17_0") (class "Default")
      (node (ref "4R_17_0") (pin "1") (pinfunction "1_1") (pintype "passive"))
      (node (ref "4R_17_0") (pin "8") (pinfunction "2_8") (pintype "passive"))
      (node (ref "LED_17_0") (pin "C") (pinfunction "C_C") (pintype "passive"))
      (node (ref "SHIFT_17") (pin "15") (pinfunction "QA_15") (pintype "tri_state"))
    )
    (net (code "140") (name "/Q17_1") (class "Default")
      (node (ref "4R_17_0") (pin "2") (pinfunction "1_2") (pintype "passive"))
      (node (ref "4R_17_0") (pin "7") (pinfunction "2_7") (pintype "passive"))
      (node (ref "LED_17_1") (pin "C") (pinfunction "C_C") (pintype "passive"))
      (node (ref "SHIFT_17") (pin "1") (pinfunction "QB_1") (pintype "tri_state"))
    )
    (net (code "141") (name "/Q17_2") (class "Default")
      (node (ref "4R_17_0") (pin "3") (pinfunction "1_3") (pintype "passive"))
      (node (ref "4R_17_0") (pin "6") (pinfunction "2_6") (pintype "passive"))
      (node (ref "LED_17_2") (pin "C") (pinfunction "C_C") (pintype "passive"))
      (node (ref "SHIFT_17") (pin "2") (pinfunction "QC_2") (pintype "tri_state"))
    )
    (net (code "142") (name "/Q17_3") (class "Default")
      (node (ref "4R_17_0") (pin "4") (pinfunction "1_4") (pintype "passive"))
      (node (ref "4R_17_0") (pin "5") (pinfunction "2_5") (pintype "passive"))
      (node (ref "LED_17_3") (pin "C") (pinfunction "C_C") (pintype "passive"))
      (node (ref "SHIFT_17") (pin "3") (pinfunction "QD_3") (pintype "tri_state"))
    )
    (net (code "143") (name "/Q17_4") (class "Default")
      (node (ref "4R_17_1") (pin "1") (pinfunction "1_1") (pintype "passive"))
      (node (ref "4R_17_1") (pin "8") (pinfunction "2_8") (pintype "passive"))
      (node (ref "LED_17_4") (pin "C") (pinfunction "C_C") (pintype "passive"))
      (node (ref "SHIFT_17") (pin "4") (pinfunction "QE_4") (pintype "tri_state"))
    )
    (net (code "144") (name "/Q17_5") (class "Default")
      (node (ref "4R_17_1") (pin "2") (pinfunction "1_2") (pintype "passive"))
      (node (ref "4R_17_1") (pin "7") (pinfunction "2_7") (pintype "passive"))
      (node (ref "LED_17_5") (pin "C") (pinfunction "C_C") (pintype "passive"))
      (node (ref "SHIFT_17") (pin "5") (pinfunction "QF_5") (pintype "tri_state"))
    )
    (net (code "145") (name "/Q17_6") (class "Default")
      (node (ref "4R_17_1") (pin "3") (pinfunction "1_3") (pintype "passive"))
      (node (ref "4R_17_1") (pin "6") (pinfunction "2_6") (pintype "passive"))
      (node (ref "LED_17_6") (pin "C") (pinfunction "C_C") (pintype "passive"))
      (node (ref "SHIFT_17") (pin "6") (pinfunction "QG_6") (pintype "tri_state"))
    )
    (net (code "146") (name "/Q17_7") (class "Default")
      (node (ref "4R_17_1") (pin "4") (pinfunction "1_4") (pintype "passive"))
      (node (ref "4R_17_1") (pin "5") (pinfunction "2_5") (pintype "passive"))
      (node (ref "LED_17_7") (pin "C") (pinfunction "C_C") (pintype "passive"))
      (node (ref "SHIFT_17") (pin "7") (pinfunction "QH_7") (pintype "tri_state"))
    )
    (net (code "147") (name "/Q18_0") (class "Default")
      (node (ref "4R_18_0") (pin "1") (pinfunction "1_1") (pintype "passive"))
      (node (ref "4R_18_0") (pin "8") (pinfunction "2_8") (pintype "passive"))
      (node (ref "LED_18_0") (pin "C") (pinfunction "C_C") (pintype "passive"))
      (node (ref "SHIFT_18") (pin "15") (pinfunction "QA_15") (pintype "tri_state"))
    )
    (net (code "148") (name "/Q18_1") (class "Default")
      (node (ref "4R_18_0") (pin "2") (pinfunction "1_2") (pintype "passive"))
      (node (ref "4R_18_0") (pin "7") (pinfunction "2_7") (pintype "passive"))
      (node (ref "LED_18_1") (pin "C") (pinfunction "C_C") (pintype "passive"))
      (node (ref "SHIFT_18") (pin "1") (pinfunction "QB_1") (pintype "tri_state"))
    )
    (net (code "149") (name "/Q18_2") (class "Default")
      (node (ref "4R_18_0") (pin "3") (pinfunction "1_3") (pintype "passive"))
      (node (ref "4R_18_0") (pin "6") (pinfunction "2_6") (pintype "passive"))
      (node (ref "LED_18_2") (pin "C") (pinfunction "C_C") (pintype "passive"))
      (node (ref "SHIFT_18") (pin "2") (pinfunction "QC_2") (pintype "tri_state"))
    )
    (net (code "150") (name "/Q18_3") (class "Default")
      (node (ref "4R_18_0") (pin "4") (pinfunction "1_4") (pintype "passive"))
      (node (ref "4R_18_0") (pin "5") (pinfunction "2_5") (pintype "passive"))
      (node (ref "LED_18_3") (pin "C") (pinfunction "C_C") (pintype "passive"))
      (node (ref "SHIFT_18") (pin "3") (pinfunction "QD_3") (pintype "tri_state"))
    )
    (net (code "151") (name "/Q18_4") (class "Default")
      (node (ref "4R_18_1") (pin "1") (pinfunction "1_1") (pintype "passive"))
      (node (ref "4R_18_1") (pin "8") (pinfunction "2_8") (pintype "passive"))
      (node (ref "LED_18_4") (pin "C") (pinfunction "C_C") (pintype "passive"))
      (node (ref "SHIFT_18") (pin "4") (pinfunction "QE_4") (pintype "tri_state"))
    )
    (net (code "152") (name "/Q18_5") (class "Default")
      (node (ref "4R_18_1") (pin "2") (pinfunction "1_2") (pintype "passive"))
      (node (ref "4R_18_1") (pin "7") (pinfunction "2_7") (pintype "passive"))
      (node (ref "LED_18_5") (pin "C") (pinfunction "C_C") (pintype "passive"))
      (node (ref "SHIFT_18") (pin "5") (pinfunction "QF_5") (pintype "tri_state"))
    )
    (net (code "153") (name "/Q18_6") (class "Default")
      (node (ref "4R_18_1") (pin "3") (pinfunction "1_3") (pintype "passive"))
      (node (ref "4R_18_1") (pin "6") (pinfunction "2_6") (pintype "passive"))
      (node (ref "LED_18_6") (pin "C") (pinfunction "C_C") (pintype "passive"))
      (node (ref "SHIFT_18") (pin "6") (pinfunction "QG_6") (pintype "tri_state"))
    )
    (net (code "154") (name "/Q18_7") (class "Default")
      (node (ref "4R_18_1") (pin "4") (pinfunction "1_4") (pintype "passive"))
      (node (ref "4R_18_1") (pin "5") (pinfunction "2_5") (pintype "passive"))
      (node (ref "LED_18_7") (pin "C") (pinfunction "C_C") (pintype "passive"))
      (node (ref "SHIFT_18") (pin "7") (pinfunction "QH_7") (pintype "tri_state"))
    )
    (net (code "155") (name "/Q19_0") (class "Default")
      (node (ref "4R_19_0") (pin "1") (pinfunction "1_1") (pintype "passive"))
      (node (ref "4R_19_0") (pin "8") (pinfunction "2_8") (pintype "passive"))
      (node (ref "LED_19_0") (pin "C") (pinfunction "C_C") (pintype "passive"))
      (node (ref "SHIFT_19") (pin "15") (pinfunction "QA_15") (pintype "tri_state"))
    )
    (net (code "156") (name "/Q19_1") (class "Default")
      (node (ref "4R_19_0") (pin "2") (pinfunction "1_2") (pintype "passive"))
      (node (ref "4R_19_0") (pin "7") (pinfunction "2_7") (pintype "passive"))
      (node (ref "LED_19_1") (pin "C") (pinfunction "C_C") (pintype "passive"))
      (node (ref "SHIFT_19") (pin "1") (pinfunction "QB_1") (pintype "tri_state"))
    )
    (net (code "157") (name "/Q19_2") (class "Default")
      (node (ref "4R_19_0") (pin "3") (pinfunction "1_3") (pintype "passive"))
      (node (ref "4R_19_0") (pin "6") (pinfunction "2_6") (pintype "passive"))
      (node (ref "LED_19_2") (pin "C") (pinfunction "C_C") (pintype "passive"))
      (node (ref "SHIFT_19") (pin "2") (pinfunction "QC_2") (pintype "tri_state"))
    )
    (net (code "158") (name "/Q19_3") (class "Default")
      (node (ref "4R_19_0") (pin "4") (pinfunction "1_4") (pintype "passive"))
      (node (ref "4R_19_0") (pin "5") (pinfunction "2_5") (pintype "passive"))
      (node (ref "LED_19_3") (pin "C") (pinfunction "C_C") (pintype "passive"))
      (node (ref "SHIFT_19") (pin "3") (pinfunction "QD_3") (pintype "tri_state"))
    )
    (net (code "159") (name "/Q19_4") (class "Default")
      (node (ref "4R_19_1") (pin "1") (pinfunction "1_1") (pintype "passive"))
      (node (ref "4R_19_1") (pin "8") (pinfunction "2_8") (pintype "passive"))
      (node (ref "LED_19_4") (pin "C") (pinfunction "C_C") (pintype "passive"))
      (node (ref "SHIFT_19") (pin "4") (pinfunction "QE_4") (pintype "tri_state"))
    )
    (net (code "160") (name "/Q19_5") (class "Default")
      (node (ref "4R_19_1") (pin "2") (pinfunction "1_2") (pintype "passive"))
      (node (ref "4R_19_1") (pin "7") (pinfunction "2_7") (pintype "passive"))
      (node (ref "LED_19_5") (pin "C") (pinfunction "C_C") (pintype "passive"))
      (node (ref "SHIFT_19") (pin "5") (pinfunction "QF_5") (pintype "tri_state"))
    )
    (net (code "161") (name "/Q19_6") (class "Default")
      (node (ref "4R_19_1") (pin "3") (pinfunction "1_3") (pintype "passive"))
      (node (ref "4R_19_1") (pin "6") (pinfunction "2_6") (pintype "passive"))
      (node (ref "LED_19_6") (pin "C") (pinfunction "C_C") (pintype "passive"))
      (node (ref "SHIFT_19") (pin "6") (pinfunction "QG_6") (pintype "tri_state"))
    )
    (net (code "162") (name "/Q19_7") (class "Default")
      (node (ref "4R_19_1") (pin "4") (pinfunction "1_4") (pintype "passive"))
      (node (ref "4R_19_1") (pin "5") (pinfunction "2_5") (pintype "passive"))
      (node (ref "LED_19_7") (pin "C") (pinfunction "C_C") (pintype "passive"))
      (node (ref "SHIFT_19") (pin "7") (pinfunction "QH_7") (pintype "tri_state"))
    )
    (net (code "163") (name "/Q20_0") (class "Default")
      (node (ref "4R_20_0") (pin "1") (pinfunction "1_1") (pintype "passive"))
      (node (ref "4R_20_0") (pin "8") (pinfunction "2_8") (pintype "passive"))
      (node (ref "LED_20_0") (pin "C") (pinfunction "C_C") (pintype "passive"))
      (node (ref "SHIFT_20") (pin "15") (pinfunction "QA_15") (pintype "tri_state"))
    )
    (net (code "164") (name "/Q20_1") (class "Default")
      (node (ref "4R_20_0") (pin "2") (pinfunction "1_2") (pintype "passive"))
      (node (ref "4R_20_0") (pin "7") (pinfunction "2_7") (pintype "passive"))
      (node (ref "LED_20_1") (pin "C") (pinfunction "C_C") (pintype "passive"))
      (node (ref "SHIFT_20") (pin "1") (pinfunction "QB_1") (pintype "tri_state"))
    )
    (net (code "165") (name "/Q20_2") (class "Default")
      (node (ref "4R_20_0") (pin "3") (pinfunction "1_3") (pintype "passive"))
      (node (ref "4R_20_0") (pin "6") (pinfunction "2_6") (pintype "passive"))
      (node (ref "LED_20_2") (pin "C") (pinfunction "C_C") (pintype "passive"))
      (node (ref "SHIFT_20") (pin "2") (pinfunction "QC_2") (pintype "tri_state"))
    )
    (net (code "166") (name "/Q20_3") (class "Default")
      (node (ref "4R_20_0") (pin "4") (pinfunction "1_4") (pintype "passive"))
      (node (ref "4R_20_0") (pin "5") (pinfunction "2_5") (pintype "passive"))
      (node (ref "LED_20_3") (pin "C") (pinfunction "C_C") (pintype "passive"))
      (node (ref "SHIFT_20") (pin "3") (pinfunction "QD_3") (pintype "tri_state"))
    )
    (net (code "167") (name "/Q20_4") (class "Default")
      (node (ref "4R_20_1") (pin "1") (pinfunction "1_1") (pintype "passive"))
      (node (ref "4R_20_1") (pin "8") (pinfunction "2_8") (pintype "passive"))
      (node (ref "LED_20_4") (pin "C") (pinfunction "C_C") (pintype "passive"))
      (node (ref "SHIFT_20") (pin "4") (pinfunction "QE_4") (pintype "tri_state"))
    )
    (net (code "168") (name "/Q20_5") (class "Default")
      (node (ref "4R_20_1") (pin "2") (pinfunction "1_2") (pintype "passive"))
      (node (ref "4R_20_1") (pin "7") (pinfunction "2_7") (pintype "passive"))
      (node (ref "LED_20_5") (pin "C") (pinfunction "C_C") (pintype "passive"))
      (node (ref "SHIFT_20") (pin "5") (pinfunction "QF_5") (pintype "tri_state"))
    )
    (net (code "169") (name "/Q20_6") (class "Default")
      (node (ref "4R_20_1") (pin "3") (pinfunction "1_3") (pintype "passive"))
      (node (ref "4R_20_1") (pin "6") (pinfunction "2_6") (pintype "passive"))
      (node (ref "LED_20_6") (pin "C") (pinfunction "C_C") (pintype "passive"))
      (node (ref "SHIFT_20") (pin "6") (pinfunction "QG_6") (pintype "tri_state"))
    )
    (net (code "170") (name "/Q20_7") (class "Default")
      (node (ref "4R_20_1") (pin "4") (pinfunction "1_4") (pintype "passive"))
      (node (ref "4R_20_1") (pin "5") (pinfunction "2_5") (pintype "passive"))
      (node (ref "LED_20_7") (pin "C") (pinfunction "C_C") (pintype "passive"))
      (node (ref "SHIFT_20") (pin "7") (pinfunction "QH_7") (pintype "tri_state"))
    )
    (net (code "171") (name "/Q21_0") (class "Default")
      (node (ref "4R_21_0") (pin "1") (pinfunction "1_1") (pintype "passive"))
      (node (ref "4R_21_0") (pin "8") (pinfunction "2_8") (pintype "passive"))
      (node (ref "LED_21_0") (pin "C") (pinfunction "C_C") (pintype "passive"))
      (node (ref "SHIFT_21") (pin "15") (pinfunction "QA_15") (pintype "tri_state"))
    )
    (net (code "172") (name "/Q21_1") (class "Default")
      (node (ref "4R_21_0") (pin "2") (pinfunction "1_2") (pintype "passive"))
      (node (ref "4R_21_0") (pin "7") (pinfunction "2_7") (pintype "passive"))
      (node (ref "LED_21_1") (pin "C") (pinfunction "C_C") (pintype "passive"))
      (node (ref "SHIFT_21") (pin "1") (pinfunction "QB_1") (pintype "tri_state"))
    )
    (net (code "173") (name "/Q21_2") (class "Default")
      (node (ref "4R_21_0") (pin "3") (pinfunction "1_3") (pintype "passive"))
      (node (ref "4R_21_0") (pin "6") (pinfunction "2_6") (pintype "passive"))
      (node (ref "LED_21_2") (pin "C") (pinfunction "C_C") (pintype "passive"))
      (node (ref "SHIFT_21") (pin "2") (pinfunction "QC_2") (pintype "tri_state"))
    )
    (net (code "174") (name "/Q21_3") (class "Default")
      (node (ref "4R_21_0") (pin "4") (pinfunction "1_4") (pintype "passive"))
      (node (ref "4R_21_0") (pin "5") (pinfunction "2_5") (pintype "passive"))
      (node (ref "LED_21_3") (pin "C") (pinfunction "C_C") (pintype "passive"))
      (node (ref "SHIFT_21") (pin "3") (pinfunction "QD_3") (pintype "tri_state"))
    )
    (net (code "175") (name "/Q21_4") (class "Default")
      (node (ref "4R_21_1") (pin "1") (pinfunction "1_1") (pintype "passive"))
      (node (ref "4R_21_1") (pin "8") (pinfunction "2_8") (pintype "passive"))
      (node (ref "LED_21_4") (pin "C") (pinfunction "C_C") (pintype "passive"))
      (node (ref "SHIFT_21") (pin "4") (pinfunction "QE_4") (pintype "tri_state"))
    )
    (net (code "176") (name "/Q21_5") (class "Default")
      (node (ref "4R_21_1") (pin "2") (pinfunction "1_2") (pintype "passive"))
      (node (ref "4R_21_1") (pin "7") (pinfunction "2_7") (pintype "passive"))
      (node (ref "LED_21_5") (pin "C") (pinfunction "C_C") (pintype "passive"))
      (node (ref "SHIFT_21") (pin "5") (pinfunction "QF_5") (pintype "tri_state"))
    )
    (net (code "177") (name "/Q21_6") (class "Default")
      (node (ref "4R_21_1") (pin "3") (pinfunction "1_3") (pintype "passive"))
      (node (ref "4R_21_1") (pin "6") (pinfunction "2_6") (pintype "passive"))
      (node (ref "LED_21_6") (pin "C") (pinfunction "C_C") (pintype "passive"))
      (node (ref "SHIFT_21") (pin "6") (pinfunction "QG_6") (pintype "tri_state"))
    )
    (net (code "178") (name "/Q21_7") (class "Default")
      (node (ref "4R_21_1") (pin "4") (pinfunction "1_4") (pintype "passive"))
      (node (ref "4R_21_1") (pin "5") (pinfunction "2_5") (pintype "passive"))
      (node (ref "LED_21_7") (pin "C") (pinfunction "C_C") (pintype "passive"))
      (node (ref "SHIFT_21") (pin "7") (pinfunction "QH_7") (pintype "tri_state"))
    )
    (net (code "179") (name "/Q22_0") (class "Default")
      (node (ref "4R_22_0") (pin "1") (pinfunction "1_1") (pintype "passive"))
      (node (ref "4R_22_0") (pin "8") (pinfunction "2_8") (pintype "passive"))
      (node (ref "LED_22_0") (pin "C") (pinfunction "C_C") (pintype "passive"))
      (node (ref "SHIFT_22") (pin "15") (pinfunction "QA_15") (pintype "tri_state"))
    )
    (net (code "180") (name "/Q22_1") (class "Default")
      (node (ref "4R_22_0") (pin "2") (pinfunction "1_2") (pintype "passive"))
      (node (ref "4R_22_0") (pin "7") (pinfunction "2_7") (pintype "passive"))
      (node (ref "LED_22_1") (pin "C") (pinfunction "C_C") (pintype "passive"))
      (node (ref "SHIFT_22") (pin "1") (pinfunction "QB_1") (pintype "tri_state"))
    )
    (net (code "181") (name "/Q22_2") (class "Default")
      (node (ref "4R_22_0") (pin "3") (pinfunction "1_3") (pintype "passive"))
      (node (ref "4R_22_0") (pin "6") (pinfunction "2_6") (pintype "passive"))
      (node (ref "LED_22_2") (pin "C") (pinfunction "C_C") (pintype "passive"))
      (node (ref "SHIFT_22") (pin "2") (pinfunction "QC_2") (pintype "tri_state"))
    )
    (net (code "182") (name "/Q22_3") (class "Default")
      (node (ref "4R_22_0") (pin "4") (pinfunction "1_4") (pintype "passive"))
      (node (ref "4R_22_0") (pin "5") (pinfunction "2_5") (pintype "passive"))
      (node (ref "LED_22_3") (pin "C") (pinfunction "C_C") (pintype "passive"))
      (node (ref "SHIFT_22") (pin "3") (pinfunction "QD_3") (pintype "tri_state"))
    )
    (net (code "183") (name "/Q22_4") (class "Default")
      (node (ref "4R_22_1") (pin "1") (pinfunction "1_1") (pintype "passive"))
      (node (ref "4R_22_1") (pin "8") (pinfunction "2_8") (pintype "passive"))
      (node (ref "LED_22_4") (pin "C") (pinfunction "C_C") (pintype "passive"))
      (node (ref "SHIFT_22") (pin "4") (pinfunction "QE_4") (pintype "tri_state"))
    )
    (net (code "184") (name "/Q22_5") (class "Default")
      (node (ref "4R_22_1") (pin "2") (pinfunction "1_2") (pintype "passive"))
      (node (ref "4R_22_1") (pin "7") (pinfunction "2_7") (pintype "passive"))
      (node (ref "LED_22_5") (pin "C") (pinfunction "C_C") (pintype "passive"))
      (node (ref "SHIFT_22") (pin "5") (pinfunction "QF_5") (pintype "tri_state"))
    )
    (net (code "185") (name "/Q22_6") (class "Default")
      (node (ref "4R_22_1") (pin "3") (pinfunction "1_3") (pintype "passive"))
      (node (ref "4R_22_1") (pin "6") (pinfunction "2_6") (pintype "passive"))
      (node (ref "LED_22_6") (pin "C") (pinfunction "C_C") (pintype "passive"))
      (node (ref "SHIFT_22") (pin "6") (pinfunction "QG_6") (pintype "tri_state"))
    )
    (net (code "186") (name "/Q22_7") (class "Default")
      (node (ref "4R_22_1") (pin "4") (pinfunction "1_4") (pintype "passive"))
      (node (ref "4R_22_1") (pin "5") (pinfunction "2_5") (pintype "passive"))
      (node (ref "LED_22_7") (pin "C") (pinfunction "C_C") (pintype "passive"))
      (node (ref "SHIFT_22") (pin "7") (pinfunction "QH_7") (pintype "tri_state"))
    )
    (net (code "187") (name "/Q23_0") (class "Default")
      (node (ref "4R_23_0") (pin "1") (pinfunction "1_1") (pintype "passive"))
      (node (ref "4R_23_0") (pin "8") (pinfunction "2_8") (pintype "passive"))
      (node (ref "LED_23_0") (pin "C") (pinfunction "C_C") (pintype "passive"))
      (node (ref "SHIFT_23") (pin "15") (pinfunction "QA_15") (pintype "tri_state"))
    )
    (net (code "188") (name "/Q23_1") (class "Default")
      (node (ref "4R_23_0") (pin "2") (pinfunction "1_2") (pintype "passive"))
      (node (ref "4R_23_0") (pin "7") (pinfunction "2_7") (pintype "passive"))
      (node (ref "LED_23_1") (pin "C") (pinfunction "C_C") (pintype "passive"))
      (node (ref "SHIFT_23") (pin "1") (pinfunction "QB_1") (pintype "tri_state"))
    )
    (net (code "189") (name "/Q23_2") (class "Default")
      (node (ref "4R_23_0") (pin "3") (pinfunction "1_3") (pintype "passive"))
      (node (ref "4R_23_0") (pin "6") (pinfunction "2_6") (pintype "passive"))
      (node (ref "LED_23_2") (pin "C") (pinfunction "C_C") (pintype "passive"))
      (node (ref "SHIFT_23") (pin "2") (pinfunction "QC_2") (pintype "tri_state"))
    )
    (net (code "190") (name "/Q23_3") (class "Default")
      (node (ref "4R_23_0") (pin "4") (pinfunction "1_4") (pintype "passive"))
      (node (ref "4R_23_0") (pin "5") (pinfunction "2_5") (pintype "passive"))
      (node (ref "LED_23_3") (pin "C") (pinfunction "C_C") (pintype "passive"))
      (node (ref "SHIFT_23") (pin "3") (pinfunction "QD_3") (pintype "tri_state"))
    )
    (net (code "191") (name "/Q23_4") (class "Default")
      (node (ref "4R_23_1") (pin "1") (pinfunction "1_1") (pintype "passive"))
      (node (ref "4R_23_1") (pin "8") (pinfunction "2_8") (pintype "passive"))
      (node (ref "LED_23_4") (pin "C") (pinfunction "C_C") (pintype "passive"))
      (node (ref "SHIFT_23") (pin "4") (pinfunction "QE_4") (pintype "tri_state"))
    )
    (net (code "192") (name "/Q23_5") (class "Default")
      (node (ref "4R_23_1") (pin "2") (pinfunction "1_2") (pintype "passive"))
      (node (ref "4R_23_1") (pin "7") (pinfunction "2_7") (pintype "passive"))
      (node (ref "LED_23_5") (pin "C") (pinfunction "C_C") (pintype "passive"))
      (node (ref "SHIFT_23") (pin "5") (pinfunction "QF_5") (pintype "tri_state"))
    )
    (net (code "193") (name "/Q23_6") (class "Default")
      (node (ref "4R_23_1") (pin "3") (pinfunction "1_3") (pintype "passive"))
      (node (ref "4R_23_1") (pin "6") (pinfunction "2_6") (pintype "passive"))
      (node (ref "LED_23_6") (pin "C") (pinfunction "C_C") (pintype "passive"))
      (node (ref "SHIFT_23") (pin "6") (pinfunction "QG_6") (pintype "tri_state"))
    )
    (net (code "194") (name "/Q23_7") (class "Default")
      (node (ref "4R_23_1") (pin "4") (pinfunction "1_4") (pintype "passive"))
      (node (ref "4R_23_1") (pin "5") (pinfunction "2_5") (pintype "passive"))
      (node (ref "LED_23_7") (pin "C") (pinfunction "C_C") (pintype "passive"))
      (node (ref "SHIFT_23") (pin "7") (pinfunction "QH_7") (pintype "tri_state"))
    )
    (net (code "195") (name "/Q24_0") (class "Default")
      (node (ref "4R_24_0") (pin "1") (pinfunction "1_1") (pintype "passive"))
      (node (ref "4R_24_0") (pin "8") (pinfunction "2_8") (pintype "passive"))
      (node (ref "LED_24_0") (pin "C") (pinfunction "C_C") (pintype "passive"))
      (node (ref "SHIFT_24") (pin "15") (pinfunction "QA_15") (pintype "tri_state"))
    )
    (net (code "196") (name "/Q24_1") (class "Default")
      (node (ref "4R_24_0") (pin "2") (pinfunction "1_2") (pintype "passive"))
      (node (ref "4R_24_0") (pin "7") (pinfunction "2_7") (pintype "passive"))
      (node (ref "LED_24_1") (pin "C") (pinfunction "C_C") (pintype "passive"))
      (node (ref "SHIFT_24") (pin "1") (pinfunction "QB_1") (pintype "tri_state"))
    )
    (net (code "197") (name "/Q24_2") (class "Default")
      (node (ref "4R_24_0") (pin "3") (pinfunction "1_3") (pintype "passive"))
      (node (ref "4R_24_0") (pin "6") (pinfunction "2_6") (pintype "passive"))
      (node (ref "LED_24_2") (pin "C") (pinfunction "C_C") (pintype "passive"))
      (node (ref "SHIFT_24") (pin "2") (pinfunction "QC_2") (pintype "tri_state"))
    )
    (net (code "198") (name "/Q24_3") (class "Default")
      (node (ref "4R_24_0") (pin "4") (pinfunction "1_4") (pintype "passive"))
      (node (ref "4R_24_0") (pin "5") (pinfunction "2_5") (pintype "passive"))
      (node (ref "LED_24_3") (pin "C") (pinfunction "C_C") (pintype "passive"))
      (node (ref "SHIFT_24") (pin "3") (pinfunction "QD_3") (pintype "tri_state"))
    )
    (net (code "199") (name "/Q24_4") (class "Default")
      (node (ref "4R_24_1") (pin "1") (pinfunction "1_1") (pintype "passive"))
      (node (ref "4R_24_1") (pin "8") (pinfunction "2_8") (pintype "passive"))
      (node (ref "LED_24_4") (pin "C") (pinfunction "C_C") (pintype "passive"))
      (node (ref "SHIFT_24") (pin "4") (pinfunction "QE_4") (pintype "tri_state"))
    )
    (net (code "200") (name "/Q24_5") (class "Default")
      (node (ref "4R_24_1") (pin "2") (pinfunction "1_2") (pintype "passive"))
      (node (ref "4R_24_1") (pin "7") (pinfunction "2_7") (pintype "passive"))
      (node (ref "LED_24_5") (pin "C") (pinfunction "C_C") (pintype "passive"))
      (node (ref "SHIFT_24") (pin "5") (pinfunction "QF_5") (pintype "tri_state"))
    )
    (net (code "201") (name "/Q24_6") (class "Default")
      (node (ref "4R_24_1") (pin "3") (pinfunction "1_3") (pintype "passive"))
      (node (ref "4R_24_1") (pin "6") (pinfunction "2_6") (pintype "passive"))
      (node (ref "LED_24_6") (pin "C") (pinfunction "C_C") (pintype "passive"))
      (node (ref "SHIFT_24") (pin "6") (pinfunction "QG_6") (pintype "tri_state"))
    )
    (net (code "202") (name "/Q24_7") (class "Default")
      (node (ref "4R_24_1") (pin "4") (pinfunction "1_4") (pintype "passive"))
      (node (ref "4R_24_1") (pin "5") (pinfunction "2_5") (pintype "passive"))
      (node (ref "LED_24_7") (pin "C") (pinfunction "C_C") (pintype "passive"))
      (node (ref "SHIFT_24") (pin "7") (pinfunction "QH_7") (pintype "tri_state"))
    )
    (net (code "203") (name "/Q25_0") (class "Default")
      (node (ref "4R_25_0") (pin "1") (pinfunction "1_1") (pintype "passive"))
      (node (ref "4R_25_0") (pin "8") (pinfunction "2_8") (pintype "passive"))
      (node (ref "LED_25_0") (pin "C") (pinfunction "C_C") (pintype "passive"))
      (node (ref "SHIFT_25") (pin "15") (pinfunction "QA_15") (pintype "tri_state"))
    )
    (net (code "204") (name "/Q25_1") (class "Default")
      (node (ref "4R_25_0") (pin "2") (pinfunction "1_2") (pintype "passive"))
      (node (ref "4R_25_0") (pin "7") (pinfunction "2_7") (pintype "passive"))
      (node (ref "LED_25_1") (pin "C") (pinfunction "C_C") (pintype "passive"))
      (node (ref "SHIFT_25") (pin "1") (pinfunction "QB_1") (pintype "tri_state"))
    )
    (net (code "205") (name "/Q25_2") (class "Default")
      (node (ref "4R_25_0") (pin "3") (pinfunction "1_3") (pintype "passive"))
      (node (ref "4R_25_0") (pin "6") (pinfunction "2_6") (pintype "passive"))
      (node (ref "LED_25_2") (pin "C") (pinfunction "C_C") (pintype "passive"))
      (node (ref "SHIFT_25") (pin "2") (pinfunction "QC_2") (pintype "tri_state"))
    )
    (net (code "206") (name "/Q25_3") (class "Default")
      (node (ref "4R_25_0") (pin "4") (pinfunction "1_4") (pintype "passive"))
      (node (ref "4R_25_0") (pin "5") (pinfunction "2_5") (pintype "passive"))
      (node (ref "LED_25_3") (pin "C") (pinfunction "C_C") (pintype "passive"))
      (node (ref "SHIFT_25") (pin "3") (pinfunction "QD_3") (pintype "tri_state"))
    )
    (net (code "207") (name "/Q25_4") (class "Default")
      (node (ref "4R_25_1") (pin "1") (pinfunction "1_1") (pintype "passive"))
      (node (ref "4R_25_1") (pin "8") (pinfunction "2_8") (pintype "passive"))
      (node (ref "LED_25_4") (pin "C") (pinfunction "C_C") (pintype "passive"))
      (node (ref "SHIFT_25") (pin "4") (pinfunction "QE_4") (pintype "tri_state"))
    )
    (net (code "208") (name "/Q25_5") (class "Default")
      (node (ref "4R_25_1") (pin "2") (pinfunction "1_2") (pintype "passive"))
      (node (ref "4R_25_1") (pin "7") (pinfunction "2_7") (pintype "passive"))
      (node (ref "LED_25_5") (pin "C") (pinfunction "C_C") (pintype "passive"))
      (node (ref "SHIFT_25") (pin "5") (pinfunction "QF_5") (pintype "tri_state"))
    )
    (net (code "209") (name "/Q25_6") (class "Default")
      (node (ref "4R_25_1") (pin "3") (pinfunction "1_3") (pintype "passive"))
      (node (ref "4R_25_1") (pin "6") (pinfunction "2_6") (pintype "passive"))
      (node (ref "LED_25_6") (pin "C") (pinfunction "C_C") (pintype "passive"))
      (node (ref "SHIFT_25") (pin "6") (pinfunction "QG_6") (pintype "tri_state"))
    )
    (net (code "210") (name "/Q25_7") (class "Default")
      (node (ref "4R_25_1") (pin "4") (pinfunction "1_4") (pintype "passive"))
      (node (ref "4R_25_1") (pin "5") (pinfunction "2_5") (pintype "passive"))
      (node (ref "LED_25_7") (pin "C") (pinfunction "C_C") (pintype "passive"))
      (node (ref "SHIFT_25") (pin "7") (pinfunction "QH_7") (pintype "tri_state"))
    )
    (net (code "211") (name "/Q26_0") (class "Default")
      (node (ref "4R_26_0") (pin "1") (pinfunction "1_1") (pintype "passive"))
      (node (ref "4R_26_0") (pin "8") (pinfunction "2_8") (pintype "passive"))
      (node (ref "LED_26_0") (pin "C") (pinfunction "C_C") (pintype "passive"))
      (node (ref "SHIFT_26") (pin "15") (pinfunction "QA_15") (pintype "tri_state"))
    )
    (net (code "212") (name "/Q26_1") (class "Default")
      (node (ref "4R_26_0") (pin "2") (pinfunction "1_2") (pintype "passive"))
      (node (ref "4R_26_0") (pin "7") (pinfunction "2_7") (pintype "passive"))
      (node (ref "LED_26_1") (pin "C") (pinfunction "C_C") (pintype "passive"))
      (node (ref "SHIFT_26") (pin "1") (pinfunction "QB_1") (pintype "tri_state"))
    )
    (net (code "213") (name "/Q26_2") (class "Default")
      (node (ref "4R_26_0") (pin "3") (pinfunction "1_3") (pintype "passive"))
      (node (ref "4R_26_0") (pin "6") (pinfunction "2_6") (pintype "passive"))
      (node (ref "LED_26_2") (pin "C") (pinfunction "C_C") (pintype "passive"))
      (node (ref "SHIFT_26") (pin "2") (pinfunction "QC_2") (pintype "tri_state"))
    )
    (net (code "214") (name "/Q26_3") (class "Default")
      (node (ref "4R_26_0") (pin "4") (pinfunction "1_4") (pintype "passive"))
      (node (ref "4R_26_0") (pin "5") (pinfunction "2_5") (pintype "passive"))
      (node (ref "LED_26_3") (pin "C") (pinfunction "C_C") (pintype "passive"))
      (node (ref "SHIFT_26") (pin "3") (pinfunction "QD_3") (pintype "tri_state"))
    )
    (net (code "215") (name "/Q26_4") (class "Default")
      (node (ref "4R_26_1") (pin "1") (pinfunction "1_1") (pintype "passive"))
      (node (ref "4R_26_1") (pin "8") (pinfunction "2_8") (pintype "passive"))
      (node (ref "LED_26_4") (pin "C") (pinfunction "C_C") (pintype "passive"))
      (node (ref "SHIFT_26") (pin "4") (pinfunction "QE_4") (pintype "tri_state"))
    )
    (net (code "216") (name "/Q26_5") (class "Default")
      (node (ref "4R_26_1") (pin "2") (pinfunction "1_2") (pintype "passive"))
      (node (ref "4R_26_1") (pin "7") (pinfunction "2_7") (pintype "passive"))
      (node (ref "LED_26_5") (pin "C") (pinfunction "C_C") (pintype "passive"))
      (node (ref "SHIFT_26") (pin "5") (pinfunction "QF_5") (pintype "tri_state"))
    )
    (net (code "217") (name "/Q26_6") (class "Default")
      (node (ref "4R_26_1") (pin "3") (pinfunction "1_3") (pintype "passive"))
      (node (ref "4R_26_1") (pin "6") (pinfunction "2_6") (pintype "passive"))
      (node (ref "LED_26_6") (pin "C") (pinfunction "C_C") (pintype "passive"))
      (node (ref "SHIFT_26") (pin "6") (pinfunction "QG_6") (pintype "tri_state"))
    )
    (net (code "218") (name "/Q26_7") (class "Default")
      (node (ref "4R_26_1") (pin "4") (pinfunction "1_4") (pintype "passive"))
      (node (ref "4R_26_1") (pin "5") (pinfunction "2_5") (pintype "passive"))
      (node (ref "LED_26_7") (pin "C") (pinfunction "C_C") (pintype "passive"))
      (node (ref "SHIFT_26") (pin "7") (pinfunction "QH_7") (pintype "tri_state"))
    )
    (net (code "219") (name "/Q27_0") (class "Default")
      (node (ref "4R_27_0") (pin "1") (pinfunction "1_1") (pintype "passive"))
      (node (ref "4R_27_0") (pin "8") (pinfunction "2_8") (pintype "passive"))
      (node (ref "LED_27_0") (pin "C") (pinfunction "C_C") (pintype "passive"))
      (node (ref "SHIFT_27") (pin "15") (pinfunction "QA_15") (pintype "tri_state"))
    )
    (net (code "220") (name "/Q27_1") (class "Default")
      (node (ref "4R_27_0") (pin "2") (pinfunction "1_2") (pintype "passive"))
      (node (ref "4R_27_0") (pin "7") (pinfunction "2_7") (pintype "passive"))
      (node (ref "LED_27_1") (pin "C") (pinfunction "C_C") (pintype "passive"))
      (node (ref "SHIFT_27") (pin "1") (pinfunction "QB_1") (pintype "tri_state"))
    )
    (net (code "221") (name "/Q27_2") (class "Default")
      (node (ref "4R_27_0") (pin "3") (pinfunction "1_3") (pintype "passive"))
      (node (ref "4R_27_0") (pin "6") (pinfunction "2_6") (pintype "passive"))
      (node (ref "LED_27_2") (pin "C") (pinfunction "C_C") (pintype "passive"))
      (node (ref "SHIFT_27") (pin "2") (pinfunction "QC_2") (pintype "tri_state"))
    )
    (net (code "222") (name "/Q27_3") (class "Default")
      (node (ref "4R_27_0") (pin "4") (pinfunction "1_4") (pintype "passive"))
      (node (ref "4R_27_0") (pin "5") (pinfunction "2_5") (pintype "passive"))
      (node (ref "LED_27_3") (pin "C") (pinfunction "C_C") (pintype "passive"))
      (node (ref "SHIFT_27") (pin "3") (pinfunction "QD_3") (pintype "tri_state"))
    )
    (net (code "223") (name "/Q27_4") (class "Default")
      (node (ref "4R_27_1") (pin "1") (pinfunction "1_1") (pintype "passive"))
      (node (ref "4R_27_1") (pin "8") (pinfunction "2_8") (pintype "passive"))
      (node (ref "LED_27_4") (pin "C") (pinfunction "C_C") (pintype "passive"))
      (node (ref "SHIFT_27") (pin "4") (pinfunction "QE_4") (pintype "tri_state"))
    )
    (net (code "224") (name "/Q27_5") (class "Default")
      (node (ref "4R_27_1") (pin "2") (pinfunction "1_2") (pintype "passive"))
      (node (ref "4R_27_1") (pin "7") (pinfunction "2_7") (pintype "passive"))
      (node (ref "LED_27_5") (pin "C") (pinfunction "C_C") (pintype "passive"))
      (node (ref "SHIFT_27") (pin "5") (pinfunction "QF_5") (pintype "tri_state"))
    )
    (net (code "225") (name "/Q27_6") (class "Default")
      (node (ref "4R_27_1") (pin "3") (pinfunction "1_3") (pintype "passive"))
      (node (ref "4R_27_1") (pin "6") (pinfunction "2_6") (pintype "passive"))
      (node (ref "LED_27_6") (pin "C") (pinfunction "C_C") (pintype "passive"))
      (node (ref "SHIFT_27") (pin "6") (pinfunction "QG_6") (pintype "tri_state"))
    )
    (net (code "226") (name "/Q27_7") (class "Default")
      (node (ref "4R_27_1") (pin "4") (pinfunction "1_4") (pintype "passive"))
      (node (ref "4R_27_1") (pin "5") (pinfunction "2_5") (pintype "passive"))
      (node (ref "LED_27_7") (pin "C") (pinfunction "C_C") (pintype "passive"))
      (node (ref "SHIFT_27") (pin "7") (pinfunction "QH_7") (pintype "tri_state"))
    )
    (net (code "227") (name "/Q28_0") (class "Default")
      (node (ref "4R_28_0") (pin "1") (pinfunction "1_1") (pintype "passive"))
      (node (ref "4R_28_0") (pin "8") (pinfunction "2_8") (pintype "passive"))
      (node (ref "LED_28_0") (pin "C") (pinfunction "C_C") (pintype "passive"))
      (node (ref "SHIFT_28") (pin "15") (pinfunction "QA_15") (pintype "tri_state"))
    )
    (net (code "228") (name "/Q28_1") (class "Default")
      (node (ref "4R_28_0") (pin "2") (pinfunction "1_2") (pintype "passive"))
      (node (ref "4R_28_0") (pin "7") (pinfunction "2_7") (pintype "passive"))
      (node (ref "LED_28_1") (pin "C") (pinfunction "C_C") (pintype "passive"))
      (node (ref "SHIFT_28") (pin "1") (pinfunction "QB_1") (pintype "tri_state"))
    )
    (net (code "229") (name "/Q28_2") (class "Default")
      (node (ref "4R_28_0") (pin "3") (pinfunction "1_3") (pintype "passive"))
      (node (ref "4R_28_0") (pin "6") (pinfunction "2_6") (pintype "passive"))
      (node (ref "LED_28_2") (pin "C") (pinfunction "C_C") (pintype "passive"))
      (node (ref "SHIFT_28") (pin "2") (pinfunction "QC_2") (pintype "tri_state"))
    )
    (net (code "230") (name "/Q28_3") (class "Default")
      (node (ref "4R_28_0") (pin "4") (pinfunction "1_4") (pintype "passive"))
      (node (ref "4R_28_0") (pin "5") (pinfunction "2_5") (pintype "passive"))
      (node (ref "LED_28_3") (pin "C") (pinfunction "C_C") (pintype "passive"))
      (node (ref "SHIFT_28") (pin "3") (pinfunction "QD_3") (pintype "tri_state"))
    )
    (net (code "231") (name "/Q28_4") (class "Default")
      (node (ref "4R_28_1") (pin "1") (pinfunction "1_1") (pintype "passive"))
      (node (ref "4R_28_1") (pin "8") (pinfunction "2_8") (pintype "passive"))
      (node (ref "LED_28_4") (pin "C") (pinfunction "C_C") (pintype "passive"))
      (node (ref "SHIFT_28") (pin "4") (pinfunction "QE_4") (pintype "tri_state"))
    )
    (net (code "232") (name "/Q28_5") (class "Default")
      (node (ref "4R_28_1") (pin "2") (pinfunction "1_2") (pintype "passive"))
      (node (ref "4R_28_1") (pin "7") (pinfunction "2_7") (pintype "passive"))
      (node (ref "LED_28_5") (pin "C") (pinfunction "C_C") (pintype "passive"))
      (node (ref "SHIFT_28") (pin "5") (pinfunction "QF_5") (pintype "tri_state"))
    )
    (net (code "233") (name "/Q28_6") (class "Default")
      (node (ref "4R_28_1") (pin "3") (pinfunction "1_3") (pintype "passive"))
      (node (ref "4R_28_1") (pin "6") (pinfunction "2_6") (pintype "passive"))
      (node (ref "LED_28_6") (pin "C") (pinfunction "C_C") (pintype "passive"))
      (node (ref "SHIFT_28") (pin "6") (pinfunction "QG_6") (pintype "tri_state"))
    )
    (net (code "234") (name "/Q28_7") (class "Default")
      (node (ref "4R_28_1") (pin "4") (pinfunction "1_4") (pintype "passive"))
      (node (ref "4R_28_1") (pin "5") (pinfunction "2_5") (pintype "passive"))
      (node (ref "LED_28_7") (pin "C") (pinfunction "C_C") (pintype "passive"))
      (node (ref "SHIFT_28") (pin "7") (pinfunction "QH_7") (pintype "tri_state"))
    )
    (net (code "235") (name "/Q29_0") (class "Default")
      (node (ref "4R_29_0") (pin "1") (pinfunction "1_1") (pintype "passive"))
      (node (ref "4R_29_0") (pin "8") (pinfunction "2_8") (pintype "passive"))
      (node (ref "LED_29_0") (pin "C") (pinfunction "C_C") (pintype "passive"))
      (node (ref "SHIFT_29") (pin "15") (pinfunction "QA_15") (pintype "tri_state"))
    )
    (net (code "236") (name "/Q29_1") (class "Default")
      (node (ref "4R_29_0") (pin "2") (pinfunction "1_2") (pintype "passive"))
      (node (ref "4R_29_0") (pin "7") (pinfunction "2_7") (pintype "passive"))
      (node (ref "LED_29_1") (pin "C") (pinfunction "C_C") (pintype "passive"))
      (node (ref "SHIFT_29") (pin "1") (pinfunction "QB_1") (pintype "tri_state"))
    )
    (net (code "237") (name "/Q29_2") (class "Default")
      (node (ref "4R_29_0") (pin "3") (pinfunction "1_3") (pintype "passive"))
      (node (ref "4R_29_0") (pin "6") (pinfunction "2_6") (pintype "passive"))
      (node (ref "LED_29_2") (pin "C") (pinfunction "C_C") (pintype "passive"))
      (node (ref "SHIFT_29") (pin "2") (pinfunction "QC_2") (pintype "tri_state"))
    )
    (net (code "238") (name "/Q29_3") (class "Default")
      (node (ref "4R_29_0") (pin "4") (pinfunction "1_4") (pintype "passive"))
      (node (ref "4R_29_0") (pin "5") (pinfunction "2_5") (pintype "passive"))
      (node (ref "LED_29_3") (pin "C") (pinfunction "C_C") (pintype "passive"))
      (node (ref "SHIFT_29") (pin "3") (pinfunction "QD_3") (pintype "tri_state"))
    )
    (net (code "239") (name "/Q29_4") (class "Default")
      (node (ref "4R_29_1") (pin "1") (pinfunction "1_1") (pintype "passive"))
      (node (ref "4R_29_1") (pin "8") (pinfunction "2_8") (pintype "passive"))
      (node (ref "LED_29_4") (pin "C") (pinfunction "C_C") (pintype "passive"))
      (node (ref "SHIFT_29") (pin "4") (pinfunction "QE_4") (pintype "tri_state"))
    )
    (net (code "240") (name "/Q29_5") (class "Default")
      (node (ref "4R_29_1") (pin "2") (pinfunction "1_2") (pintype "passive"))
      (node (ref "4R_29_1") (pin "7") (pinfunction "2_7") (pintype "passive"))
      (node (ref "LED_29_5") (pin "C") (pinfunction "C_C") (pintype "passive"))
      (node (ref "SHIFT_29") (pin "5") (pinfunction "QF_5") (pintype "tri_state"))
    )
    (net (code "241") (name "/Q29_6") (class "Default")
      (node (ref "4R_29_1") (pin "3") (pinfunction "1_3") (pintype "passive"))
      (node (ref "4R_29_1") (pin "6") (pinfunction "2_6") (pintype "passive"))
      (node (ref "LED_29_6") (pin "C") (pinfunction "C_C") (pintype "passive"))
      (node (ref "SHIFT_29") (pin "6") (pinfunction "QG_6") (pintype "tri_state"))
    )
    (net (code "242") (name "/Q29_7") (class "Default")
      (node (ref "4R_29_1") (pin "4") (pinfunction "1_4") (pintype "passive"))
      (node (ref "4R_29_1") (pin "5") (pinfunction "2_5") (pintype "passive"))
      (node (ref "LED_29_7") (pin "C") (pinfunction "C_C") (pintype "passive"))
      (node (ref "SHIFT_29") (pin "7") (pinfunction "QH_7") (pintype "tri_state"))
    )
    (net (code "243") (name "/Q30_0") (class "Default")
      (node (ref "4R_30_0") (pin "1") (pinfunction "1_1") (pintype "passive"))
      (node (ref "4R_30_0") (pin "8") (pinfunction "2_8") (pintype "passive"))
      (node (ref "LED_30_0") (pin "C") (pinfunction "C_C") (pintype "passive"))
      (node (ref "SHIFT_30") (pin "15") (pinfunction "QA_15") (pintype "tri_state"))
    )
    (net (code "244") (name "/Q30_1") (class "Default")
      (node (ref "4R_30_0") (pin "2") (pinfunction "1_2") (pintype "passive"))
      (node (ref "4R_30_0") (pin "7") (pinfunction "2_7") (pintype "passive"))
      (node (ref "LED_30_1") (pin "C") (pinfunction "C_C") (pintype "passive"))
      (node (ref "SHIFT_30") (pin "1") (pinfunction "QB_1") (pintype "tri_state"))
    )
    (net (code "245") (name "/Q30_2") (class "Default")
      (node (ref "4R_30_0") (pin "3") (pinfunction "1_3") (pintype "passive"))
      (node (ref "4R_30_0") (pin "6") (pinfunction "2_6") (pintype "passive"))
      (node (ref "LED_30_2") (pin "C") (pinfunction "C_C") (pintype "passive"))
      (node (ref "SHIFT_30") (pin "2") (pinfunction "QC_2") (pintype "tri_state"))
    )
    (net (code "246") (name "/Q30_3") (class "Default")
      (node (ref "4R_30_0") (pin "4") (pinfunction "1_4") (pintype "passive"))
      (node (ref "4R_30_0") (pin "5") (pinfunction "2_5") (pintype "passive"))
      (node (ref "LED_30_3") (pin "C") (pinfunction "C_C") (pintype "passive"))
      (node (ref "SHIFT_30") (pin "3") (pinfunction "QD_3") (pintype "tri_state"))
    )
    (net (code "247") (name "/Q30_4") (class "Default")
      (node (ref "4R_30_1") (pin "1") (pinfunction "1_1") (pintype "passive"))
      (node (ref "4R_30_1") (pin "8") (pinfunction "2_8") (pintype "passive"))
      (node (ref "LED_30_4") (pin "C") (pinfunction "C_C") (pintype "passive"))
      (node (ref "SHIFT_30") (pin "4") (pinfunction "QE_4") (pintype "tri_state"))
    )
    (net (code "248") (name "/Q30_5") (class "Default")
      (node (ref "4R_30_1") (pin "2") (pinfunction "1_2") (pintype "passive"))
      (node (ref "4R_30_1") (pin "7") (pinfunction "2_7") (pintype "passive"))
      (node (ref "LED_30_5") (pin "C") (pinfunction "C_C") (pintype "passive"))
      (node (ref "SHIFT_30") (pin "5") (pinfunction "QF_5") (pintype "tri_state"))
    )
    (net (code "249") (name "/Q30_6") (class "Default")
      (node (ref "4R_30_1") (pin "3") (pinfunction "1_3") (pintype "passive"))
      (node (ref "4R_30_1") (pin "6") (pinfunction "2_6") (pintype "passive"))
      (node (ref "LED_30_6") (pin "C") (pinfunction "C_C") (pintype "passive"))
      (node (ref "SHIFT_30") (pin "6") (pinfunction "QG_6") (pintype "tri_state"))
    )
    (net (code "250") (name "/Q30_7") (class "Default")
      (node (ref "4R_30_1") (pin "4") (pinfunction "1_4") (pintype "passive"))
      (node (ref "4R_30_1") (pin "5") (pinfunction "2_5") (pintype "passive"))
      (node (ref "LED_30_7") (pin "C") (pinfunction "C_C") (pintype "passive"))
      (node (ref "SHIFT_30") (pin "7") (pinfunction "QH_7") (pintype "tri_state"))
    )
    (net (code "251") (name "/Q31_0") (class "Default")
      (node (ref "4R_31_0") (pin "1") (pinfunction "1_1") (pintype "passive"))
      (node (ref "4R_31_0") (pin "8") (pinfunction "2_8") (pintype "passive"))
      (node (ref "LED_31_0") (pin "C") (pinfunction "C_C") (pintype "passive"))
      (node (ref "SHIFT_31") (pin "15") (pinfunction "QA_15") (pintype "tri_state"))
    )
    (net (code "252") (name "/Q31_1") (class "Default")
      (node (ref "4R_31_0") (pin "2") (pinfunction "1_2") (pintype "passive"))
      (node (ref "4R_31_0") (pin "7") (pinfunction "2_7") (pintype "passive"))
      (node (ref "LED_31_1") (pin "C") (pinfunction "C_C") (pintype "passive"))
      (node (ref "SHIFT_31") (pin "1") (pinfunction "QB_1") (pintype "tri_state"))
    )
    (net (code "253") (name "/Q31_2") (class "Default")
      (node (ref "4R_31_0") (pin "3") (pinfunction "1_3") (pintype "passive"))
      (node (ref "4R_31_0") (pin "6") (pinfunction "2_6") (pintype "passive"))
      (node (ref "LED_31_2") (pin "C") (pinfunction "C_C") (pintype "passive"))
      (node (ref "SHIFT_31") (pin "2") (pinfunction "QC_2") (pintype "tri_state"))
    )
    (net (code "254") (name "/Q31_3") (class "Default")
      (node (ref "4R_31_0") (pin "4") (pinfunction "1_4") (pintype "passive"))
      (node (ref "4R_31_0") (pin "5") (pinfunction "2_5") (pintype "passive"))
      (node (ref "LED_31_3") (pin "C") (pinfunction "C_C") (pintype "passive"))
      (node (ref "SHIFT_31") (pin "3") (pinfunction "QD_3") (pintype "tri_state"))
    )
    (net (code "255") (name "/Q31_4") (class "Default")
      (node (ref "4R_31_1") (pin "1") (pinfunction "1_1") (pintype "passive"))
      (node (ref "4R_31_1") (pin "8") (pinfunction "2_8") (pintype "passive"))
      (node (ref "LED_31_4") (pin "C") (pinfunction "C_C") (pintype "passive"))
      (node (ref "SHIFT_31") (pin "4") (pinfunction "QE_4") (pintype "tri_state"))
    )
    (net (code "256") (name "/Q31_5") (class "Default")
      (node (ref "4R_31_1") (pin "2") (pinfunction "1_2") (pintype "passive"))
      (node (ref "4R_31_1") (pin "7") (pinfunction "2_7") (pintype "passive"))
      (node (ref "LED_31_5") (pin "C") (pinfunction "C_C") (pintype "passive"))
      (node (ref "SHIFT_31") (pin "5") (pinfunction "QF_5") (pintype "tri_state"))
    )
    (net (code "257") (name "/Q31_6") (class "Default")
      (node (ref "4R_31_1") (pin "3") (pinfunction "1_3") (pintype "passive"))
      (node (ref "4R_31_1") (pin "6") (pinfunction "2_6") (pintype "passive"))
      (node (ref "LED_31_6") (pin "C") (pinfunction "C_C") (pintype "passive"))
      (node (ref "SHIFT_31") (pin "6") (pinfunction "QG_6") (pintype "tri_state"))
    )
    (net (code "258") (name "/Q31_7") (class "Default")
      (node (ref "4R_31_1") (pin "4") (pinfunction "1_4") (pintype "passive"))
      (node (ref "4R_31_1") (pin "5") (pinfunction "2_5") (pintype "passive"))
      (node (ref "LED_31_7") (pin "C") (pinfunction "C_C") (pintype "passive"))
      (node (ref "SHIFT_31") (pin "7") (pinfunction "QH_7") (pintype "tri_state"))
    )
    (net (code "259") (name "/TRIG") (class "Default")
      (node (ref "J1") (pin "5") (pinfunction "5_5") (pintype "passive"))
      (node (ref "J3") (pin "3") (pinfunction "3_3") (pintype "passive"))
    )
    (net (code "260") (name "/VCC") (class "Default")
      (node (ref "C1") (pin "+") (pinfunction "+_+") (pintype "passive"))
      (node (ref "J2") (pin "1") (pinfunction "1_1") (pintype "passive"))
      (node (ref "J3") (pin "1") (pinfunction "1_1") (pintype "passive"))
      (node (ref "SHIFT_0") (pin "10") (pinfunction "SCL_10") (pintype "input"))
      (node (ref "SHIFT_0") (pin "16") (pinfunction "VCC_16") (pintype "power_in"))
      (node (ref "SHIFT_1") (pin "10") (pinfunction "SCL_10") (pintype "input"))
      (node (ref "SHIFT_1") (pin "16") (pinfunction "VCC_16") (pintype "power_in"))
      (node (ref "SHIFT_10") (pin "10") (pinfunction "SCL_10") (pintype "input"))
      (node (ref "SHIFT_10") (pin "16") (pinfunction "VCC_16") (pintype "power_in"))
      (node (ref "SHIFT_11") (pin "10") (pinfunction "SCL_10") (pintype "input"))
      (node (ref "SHIFT_11") (pin "16") (pinfunction "VCC_16") (pintype "power_in"))
      (node (ref "SHIFT_12") (pin "10") (pinfunction "SCL_10") (pintype "input"))
      (node (ref "SHIFT_12") (pin "16") (pinfunction "VCC_16") (pintype "power_in"))
      (node (ref "SHIFT_13") (pin "10") (pinfunction "SCL_10") (pintype "input"))
      (node (ref "SHIFT_13") (pin "16") (pinfunction "VCC_16") (pintype "power_in"))
      (node (ref "SHIFT_14") (pin "10") (pinfunction "SCL_10") (pintype "input"))
      (node (ref "SHIFT_14") (pin "16") (pinfunction "VCC_16") (pintype "power_in"))
      (node (ref "SHIFT_15") (pin "10") (pinfunction "SCL_10") (pintype "input"))
      (node (ref "SHIFT_15") (pin "16") (pinfunction "VCC_16") (pintype "power_in"))
      (node (ref "SHIFT_16") (pin "10") (pinfunction "SCL_10") (pintype "input"))
      (node (ref "SHIFT_16") (pin "16") (pinfunction "VCC_16") (pintype "power_in"))
      (node (ref "SHIFT_17") (pin "10") (pinfunction "SCL_10") (pintype "input"))
      (node (ref "SHIFT_17") (pin "16") (pinfunction "VCC_16") (pintype "power_in"))
      (node (ref "SHIFT_18") (pin "10") (pinfunction "SCL_10") (pintype "input"))
      (node (ref "SHIFT_18") (pin "16") (pinfunction "VCC_16") (pintype "power_in"))
      (node (ref "SHIFT_19") (pin "10") (pinfunction "SCL_10") (pintype "input"))
      (node (ref "SHIFT_19") (pin "16") (pinfunction "VCC_16") (pintype "power_in"))
      (node (ref "SHIFT_2") (pin "10") (pinfunction "SCL_10") (pintype "input"))
      (node (ref "SHIFT_2") (pin "16") (pinfunction "VCC_16") (pintype "power_in"))
      (node (ref "SHIFT_20") (pin "10") (pinfunction "SCL_10") (pintype "input"))
      (node (ref "SHIFT_20") (pin "16") (pinfunction "VCC_16") (pintype "power_in"))
      (node (ref "SHIFT_21") (pin "10") (pinfunction "SCL_10") (pintype "input"))
      (node (ref "SHIFT_21") (pin "16") (pinfunction "VCC_16") (pintype "power_in"))
      (node (ref "SHIFT_22") (pin "10") (pinfunction "SCL_10") (pintype "input"))
      (node (ref "SHIFT_22") (pin "16") (pinfunction "VCC_16") (pintype "power_in"))
      (node (ref "SHIFT_23") (pin "10") (pinfunction "SCL_10") (pintype "input"))
      (node (ref "SHIFT_23") (pin "16") (pinfunction "VCC_16") (pintype "power_in"))
      (node (ref "SHIFT_24") (pin "10") (pinfunction "SCL_10") (pintype "input"))
      (node (ref "SHIFT_24") (pin "16") (pinfunction "VCC_16") (pintype "power_in"))
      (node (ref "SHIFT_25") (pin "10") (pinfunction "SCL_10") (pintype "input"))
      (node (ref "SHIFT_25") (pin "16") (pinfunction "VCC_16") (pintype "power_in"))
      (node (ref "SHIFT_26") (pin "10") (pinfunction "SCL_10") (pintype "input"))
      (node (ref "SHIFT_26") (pin "16") (pinfunction "VCC_16") (pintype "power_in"))
      (node (ref "SHIFT_27") (pin "10") (pinfunction "SCL_10") (pintype "input"))
      (node (ref "SHIFT_27") (pin "16") (pinfunction "VCC_16") (pintype "power_in"))
      (node (ref "SHIFT_28") (pin "10") (pinfunction "SCL_10") (pintype "input"))
      (node (ref "SHIFT_28") (pin "16") (pinfunction "VCC_16") (pintype "power_in"))
      (node (ref "SHIFT_29") (pin "10") (pinfunction "SCL_10") (pintype "input"))
      (node (ref "SHIFT_29") (pin "16") (pinfunction "VCC_16") (pintype "power_in"))
      (node (ref "SHIFT_3") (pin "10") (pinfunction "SCL_10") (pintype "input"))
      (node (ref "SHIFT_3") (pin "16") (pinfunction "VCC_16") (pintype "power_in"))
      (node (ref "SHIFT_30") (pin "10") (pinfunction "SCL_10") (pintype "input"))
      (node (ref "SHIFT_30") (pin "16") (pinfunction "VCC_16") (pintype "power_in"))
      (node (ref "SHIFT_31") (pin "10") (pinfunction "SCL_10") (pintype "input"))
      (node (ref "SHIFT_31") (pin "16") (pinfunction "VCC_16") (pintype "power_in"))
      (node (ref "SHIFT_4") (pin "10") (pinfunction "SCL_10") (pintype "input"))
      (node (ref "SHIFT_4") (pin "16") (pinfunction "VCC_16") (pintype "power_in"))
      (node (ref "SHIFT_5") (pin "10") (pinfunction "SCL_10") (pintype "input"))
      (node (ref "SHIFT_5") (pin "16") (pinfunction "VCC_16") (pintype "power_in"))
      (node (ref "SHIFT_6") (pin "10") (pinfunction "SCL_10") (pintype "input"))
      (node (ref "SHIFT_6") (pin "16") (pinfunction "VCC_16") (pintype "power_in"))
      (node (ref "SHIFT_7") (pin "10") (pinfunction "SCL_10") (pintype "input"))
      (node (ref "SHIFT_7") (pin "16") (pinfunction "VCC_16") (pintype "power_in"))
      (node (ref "SHIFT_8") (pin "10") (pinfunction "SCL_10") (pintype "input"))
      (node (ref "SHIFT_8") (pin "16") (pinfunction "VCC_16") (pintype "power_in"))
      (node (ref "SHIFT_9") (pin "10") (pinfunction "SCL_10") (pintype "input"))
      (node (ref "SHIFT_9") (pin "16") (pinfunction "VCC_16") (pintype "power_in"))
    )
    (net (code "261") (name "Net-(SHIFT_0-QH*)") (class "Default")
      (node (ref "SHIFT_0") (pin "9") (pinfunction "QH*_9") (pintype "tri_state"))
      (node (ref "SHIFT_1") (pin "14") (pinfunction "SER_14") (pintype "input"))
    )
    (net (code "262") (name "Net-(SHIFT_0-RCK)") (class "Default")
      (node (ref "J1") (pin "3") (pinfunction "3_3") (pintype "passive"))
      (node (ref "SHIFT_0") (pin "12") (pinfunction "RCK_12") (pintype "input"))
      (node (ref "SHIFT_1") (pin "12") (pinfunction "RCK_12") (pintype "input"))
      (node (ref "SHIFT_10") (pin "12") (pinfunction "RCK_12") (pintype "input"))
      (node (ref "SHIFT_11") (pin "12") (pinfunction "RCK_12") (pintype "input"))
      (node (ref "SHIFT_12") (pin "12") (pinfunction "RCK_12") (pintype "input"))
      (node (ref "SHIFT_13") (pin "12") (pinfunction "RCK_12") (pintype "input"))
      (node (ref "SHIFT_14") (pin "12") (pinfunction "RCK_12") (pintype "input"))
      (node (ref "SHIFT_15") (pin "12") (pinfunction "RCK_12") (pintype "input"))
      (node (ref "SHIFT_16") (pin "12") (pinfunction "RCK_12") (pintype "input"))
      (node (ref "SHIFT_17") (pin "12") (pinfunction "RCK_12") (pintype "input"))
      (node (ref "SHIFT_18") (pin "12") (pinfunction "RCK_12") (pintype "input"))
      (node (ref "SHIFT_19") (pin "12") (pinfunction "RCK_12") (pintype "input"))
      (node (ref "SHIFT_2") (pin "12") (pinfunction "RCK_12") (pintype "input"))
      (node (ref "SHIFT_20") (pin "12") (pinfunction "RCK_12") (pintype "input"))
      (node (ref "SHIFT_21") (pin "12") (pinfunction "RCK_12") (pintype "input"))
      (node (ref "SHIFT_22") (pin "12") (pinfunction "RCK_12") (pintype "input"))
      (node (ref "SHIFT_23") (pin "12") (pinfunction "RCK_12") (pintype "input"))
      (node (ref "SHIFT_24") (pin "12") (pinfunction "RCK_12") (pintype "input"))
      (node (ref "SHIFT_25") (pin "12") (pinfunction "RCK_12") (pintype "input"))
      (node (ref "SHIFT_26") (pin "12") (pinfunction "RCK_12") (pintype "input"))
      (node (ref "SHIFT_27") (pin "12") (pinfunction "RCK_12") (pintype "input"))
      (node (ref "SHIFT_28") (pin "12") (pinfunction "RCK_12") (pintype "input"))
      (node (ref "SHIFT_29") (pin "12") (pinfunction "RCK_12") (pintype "input"))
      (node (ref "SHIFT_3") (pin "12") (pinfunction "RCK_12") (pintype "input"))
      (node (ref "SHIFT_30") (pin "12") (pinfunction "RCK_12") (pintype "input"))
      (node (ref "SHIFT_31") (pin "12") (pinfunction "RCK_12") (pintype "input"))
      (node (ref "SHIFT_4") (pin "12") (pinfunction "RCK_12") (pintype "input"))
      (node (ref "SHIFT_5") (pin "12") (pinfunction "RCK_12") (pintype "input"))
      (node (ref "SHIFT_6") (pin "12") (pinfunction "RCK_12") (pintype "input"))
      (node (ref "SHIFT_7") (pin "12") (pinfunction "RCK_12") (pintype "input"))
      (node (ref "SHIFT_8") (pin "12") (pinfunction "RCK_12") (pintype "input"))
      (node (ref "SHIFT_9") (pin "12") (pinfunction "RCK_12") (pintype "input"))
    )
    (net (code "263") (name "Net-(SHIFT_0-SCK)") (class "Default")
      (node (ref "J1") (pin "4") (pinfunction "4_4") (pintype "passive"))
      (node (ref "SHIFT_0") (pin "11") (pinfunction "SCK_11") (pintype "input"))
      (node (ref "SHIFT_1") (pin "11") (pinfunction "SCK_11") (pintype "input"))
      (node (ref "SHIFT_10") (pin "11") (pinfunction "SCK_11") (pintype "input"))
      (node (ref "SHIFT_11") (pin "11") (pinfunction "SCK_11") (pintype "input"))
      (node (ref "SHIFT_12") (pin "11") (pinfunction "SCK_11") (pintype "input"))
      (node (ref "SHIFT_13") (pin "11") (pinfunction "SCK_11") (pintype "input"))
      (node (ref "SHIFT_14") (pin "11") (pinfunction "SCK_11") (pintype "input"))
      (node (ref "SHIFT_15") (pin "11") (pinfunction "SCK_11") (pintype "input"))
      (node (ref "SHIFT_16") (pin "11") (pinfunction "SCK_11") (pintype "input"))
      (node (ref "SHIFT_17") (pin "11") (pinfunction "SCK_11") (pintype "input"))
      (node (ref "SHIFT_18") (pin "11") (pinfunction "SCK_11") (pintype "input"))
      (node (ref "SHIFT_19") (pin "11") (pinfunction "SCK_11") (pintype "input"))
      (node (ref "SHIFT_2") (pin "11") (pinfunction "SCK_11") (pintype "input"))
      (node (ref "SHIFT_20") (pin "11") (pinfunction "SCK_11") (pintype "input"))
      (node (ref "SHIFT_21") (pin "11") (pinfunction "SCK_11") (pintype "input"))
      (node (ref "SHIFT_22") (pin "11") (pinfunction "SCK_11") (pintype "input"))
      (node (ref "SHIFT_23") (pin "11") (pinfunction "SCK_11") (pintype "input"))
      (node (ref "SHIFT_24") (pin "11") (pinfunction "SCK_11") (pintype "input"))
      (node (ref "SHIFT_25") (pin "11") (pinfunction "SCK_11") (pintype "input"))
      (node (ref "SHIFT_26") (pin "11") (pinfunction "SCK_11") (pintype "input"))
      (node (ref "SHIFT_27") (pin "11") (pinfunction "SCK_11") (pintype "input"))
      (node (ref "SHIFT_28") (pin "11") (pinfunction "SCK_11") (pintype "input"))
      (node (ref "SHIFT_29") (pin "11") (pinfunction "SCK_11") (pintype "input"))
      (node (ref "SHIFT_3") (pin "11") (pinfunction "SCK_11") (pintype "input"))
      (node (ref "SHIFT_30") (pin "11") (pinfunction "SCK_11") (pintype "input"))
      (node (ref "SHIFT_31") (pin "11") (pinfunction "SCK_11") (pintype "input"))
      (node (ref "SHIFT_4") (pin "11") (pinfunction "SCK_11") (pintype "input"))
      (node (ref "SHIFT_5") (pin "11") (pinfunction "SCK_11") (pintype "input"))
      (node (ref "SHIFT_6") (pin "11") (pinfunction "SCK_11") (pintype "input"))
      (node (ref "SHIFT_7") (pin "11") (pinfunction "SCK_11") (pintype "input"))
      (node (ref "SHIFT_8") (pin "11") (pinfunction "SCK_11") (pintype "input"))
      (node (ref "SHIFT_9") (pin "11") (pinfunction "SCK_11") (pintype "input"))
    )
    (net (code "264") (name "Net-(SHIFT_1-QH*)") (class "Default")
      (node (ref "SHIFT_1") (pin "9") (pinfunction "QH*_9") (pintype "tri_state"))
      (node (ref "SHIFT_2") (pin "14") (pinfunction "SER_14") (pintype "input"))
    )
    (net (code "265") (name "Net-(SHIFT_2-QH*)") (class "Default")
      (node (ref "SHIFT_2") (pin "9") (pinfunction "QH*_9") (pintype "tri_state"))
      (node (ref "SHIFT_3") (pin "14") (pinfunction "SER_14") (pintype "input"))
    )
    (net (code "266") (name "Net-(SHIFT_3-QH*)") (class "Default")
      (node (ref "SHIFT_3") (pin "9") (pinfunction "QH*_9") (pintype "tri_state"))
      (node (ref "SHIFT_4") (pin "14") (pinfunction "SER_14") (pintype "input"))
    )
    (net (code "267") (name "Net-(SHIFT_4-QH*)") (class "Default")
      (node (ref "SHIFT_4") (pin "9") (pinfunction "QH*_9") (pintype "tri_state"))
      (node (ref "SHIFT_5") (pin "14") (pinfunction "SER_14") (pintype "input"))
    )
    (net (code "268") (name "Net-(SHIFT_5-QH*)") (class "Default")
      (node (ref "SHIFT_5") (pin "9") (pinfunction "QH*_9") (pintype "tri_state"))
      (node (ref "SHIFT_6") (pin "14") (pinfunction "SER_14") (pintype "input"))
    )
    (net (code "269") (name "Net-(SHIFT_6-QH*)") (class "Default")
      (node (ref "SHIFT_6") (pin "9") (pinfunction "QH*_9") (pintype "tri_state"))
      (node (ref "SHIFT_7") (pin "14") (pinfunction "SER_14") (pintype "input"))
    )
    (net (code "270") (name "Net-(SHIFT_7-QH*)") (class "Default")
      (node (ref "SHIFT_7") (pin "9") (pinfunction "QH*_9") (pintype "tri_state"))
      (node (ref "SHIFT_8") (pin "14") (pinfunction "SER_14") (pintype "input"))
    )
    (net (code "271") (name "Net-(SHIFT_8-QH*)") (class "Default")
      (node (ref "SHIFT_8") (pin "9") (pinfunction "QH*_9") (pintype "tri_state"))
      (node (ref "SHIFT_9") (pin "14") (pinfunction "SER_14") (pintype "input"))
    )
    (net (code "272") (name "Net-(SHIFT_10-QH*)") (class "Default")
      (node (ref "SHIFT_10") (pin "9") (pinfunction "QH*_9") (pintype "tri_state"))
      (node (ref "SHIFT_11") (pin "14") (pinfunction "SER_14") (pintype "input"))
    )
    (net (code "273") (name "Net-(SHIFT_10-SER)") (class "Default")
      (node (ref "SHIFT_10") (pin "14") (pinfunction "SER_14") (pintype "input"))
      (node (ref "SHIFT_9") (pin "9") (pinfunction "QH*_9") (pintype "tri_state"))
    )
    (net (code "274") (name "Net-(SHIFT_11-QH*)") (class "Default")
      (node (ref "SHIFT_11") (pin "9") (pinfunction "QH*_9") (pintype "tri_state"))
      (node (ref "SHIFT_12") (pin "14") (pinfunction "SER_14") (pintype "input"))
    )
    (net (code "275") (name "Net-(SHIFT_12-QH*)") (class "Default")
      (node (ref "SHIFT_12") (pin "9") (pinfunction "QH*_9") (pintype "tri_state"))
      (node (ref "SHIFT_13") (pin "14") (pinfunction "SER_14") (pintype "input"))
    )
    (net (code "276") (name "Net-(SHIFT_13-QH*)") (class "Default")
      (node (ref "SHIFT_13") (pin "9") (pinfunction "QH*_9") (pintype "tri_state"))
      (node (ref "SHIFT_14") (pin "14") (pinfunction "SER_14") (pintype "input"))
    )
    (net (code "277") (name "Net-(SHIFT_14-QH*)") (class "Default")
      (node (ref "SHIFT_14") (pin "9") (pinfunction "QH*_9") (pintype "tri_state"))
      (node (ref "SHIFT_15") (pin "14") (pinfunction "SER_14") (pintype "input"))
    )
    (net (code "278") (name "Net-(SHIFT_15-QH*)") (class "Default")
      (node (ref "SHIFT_15") (pin "9") (pinfunction "QH*_9") (pintype "tri_state"))
      (node (ref "SHIFT_16") (pin "14") (pinfunction "SER_14") (pintype "input"))
    )
    (net (code "279") (name "Net-(SHIFT_16-QH*)") (class "Default")
      (node (ref "SHIFT_16") (pin "9") (pinfunction "QH*_9") (pintype "tri_state"))
      (node (ref "SHIFT_17") (pin "14") (pinfunction "SER_14") (pintype "input"))
    )
    (net (code "280") (name "Net-(SHIFT_17-QH*)") (class "Default")
      (node (ref "SHIFT_17") (pin "9") (pinfunction "QH*_9") (pintype "tri_state"))
      (node (ref "SHIFT_18") (pin "14") (pinfunction "SER_14") (pintype "input"))
    )
    (net (code "281") (name "Net-(SHIFT_18-QH*)") (class "Default")
      (node (ref "SHIFT_18") (pin "9") (pinfunction "QH*_9") (pintype "tri_state"))
      (node (ref "SHIFT_19") (pin "14") (pinfunction "SER_14") (pintype "input"))
    )
    (net (code "282") (name "Net-(SHIFT_19-QH*)") (class "Default")
      (node (ref "SHIFT_19") (pin "9") (pinfunction "QH*_9") (pintype "tri_state"))
      (node (ref "SHIFT_20") (pin "14") (pinfunction "SER_14") (pintype "input"))
    )
    (net (code "283") (name "Net-(SHIFT_20-QH*)") (class "Default")
      (node (ref "SHIFT_20") (pin "9") (pinfunction "QH*_9") (pintype "tri_state"))
      (node (ref "SHIFT_21") (pin "14") (pinfunction "SER_14") (pintype "input"))
    )
    (net (code "284") (name "Net-(SHIFT_21-QH*)") (class "Default")
      (node (ref "SHIFT_21") (pin "9") (pinfunction "QH*_9") (pintype "tri_state"))
      (node (ref "SHIFT_22") (pin "14") (pinfunction "SER_14") (pintype "input"))
    )
    (net (code "285") (name "Net-(SHIFT_22-QH*)") (class "Default")
      (node (ref "SHIFT_22") (pin "9") (pinfunction "QH*_9") (pintype "tri_state"))
      (node (ref "SHIFT_23") (pin "14") (pinfunction "SER_14") (pintype "input"))
    )
    (net (code "286") (name "Net-(SHIFT_23-QH*)") (class "Default")
      (node (ref "SHIFT_23") (pin "9") (pinfunction "QH*_9") (pintype "tri_state"))
      (node (ref "SHIFT_24") (pin "14") (pinfunction "SER_14") (pintype "input"))
    )
    (net (code "287") (name "Net-(SHIFT_24-QH*)") (class "Default")
      (node (ref "SHIFT_24") (pin "9") (pinfunction "QH*_9") (pintype "tri_state"))
      (node (ref "SHIFT_25") (pin "14") (pinfunction "SER_14") (pintype "input"))
    )
    (net (code "288") (name "Net-(SHIFT_25-QH*)") (class "Default")
      (node (ref "SHIFT_25") (pin "9") (pinfunction "QH*_9") (pintype "tri_state"))
      (node (ref "SHIFT_26") (pin "14") (pinfunction "SER_14") (pintype "input"))
    )
    (net (code "289") (name "Net-(SHIFT_26-QH*)") (class "Default")
      (node (ref "SHIFT_26") (pin "9") (pinfunction "QH*_9") (pintype "tri_state"))
      (node (ref "SHIFT_27") (pin "14") (pinfunction "SER_14") (pintype "input"))
    )
    (net (code "290") (name "Net-(SHIFT_27-QH*)") (class "Default")
      (node (ref "SHIFT_27") (pin "9") (pinfunction "QH*_9") (pintype "tri_state"))
      (node (ref "SHIFT_28") (pin "14") (pinfunction "SER_14") (pintype "input"))
    )
    (net (code "291") (name "Net-(SHIFT_28-QH*)") (class "Default")
      (node (ref "SHIFT_28") (pin "9") (pinfunction "QH*_9") (pintype "tri_state"))
      (node (ref "SHIFT_29") (pin "14") (pinfunction "SER_14") (pintype "input"))
    )
    (net (code "292") (name "Net-(SHIFT_29-QH*)") (class "Default")
      (node (ref "SHIFT_29") (pin "9") (pinfunction "QH*_9") (pintype "tri_state"))
      (node (ref "SHIFT_30") (pin "14") (pinfunction "SER_14") (pintype "input"))
    )
    (net (code "293") (name "Net-(SHIFT_30-QH*)") (class "Default")
      (node (ref "J1") (pin "1") (pinfunction "1_1") (pintype "passive"))
      (node (ref "SHIFT_30") (pin "9") (pinfunction "QH*_9") (pintype "tri_state"))
      (node (ref "SHIFT_31") (pin "14") (pinfunction "SER_14") (pintype "input"))
    )
    (net (code "294") (name "unconnected-(H1-MOUNT-PadB3,2)") (class "Default")
      (node (ref "H1") (pin "B3,2") (pinfunction "MOUNT_B3,2") (pintype "passive"))
    )
    (net (code "295") (name "unconnected-(H2-MOUNT-PadB3,2)") (class "Default")
      (node (ref "H2") (pin "B3,2") (pinfunction "MOUNT_B3,2") (pintype "passive"))
    )
    (net (code "296") (name "unconnected-(H3-MOUNT-PadB3,2)") (class "Default")
      (node (ref "H3") (pin "B3,2") (pinfunction "MOUNT_B3,2") (pintype "passive"))
    )
    (net (code "297") (name "unconnected-(H4-MOUNT-PadB3,2)") (class "Default")
      (node (ref "H4") (pin "B3,2") (pinfunction "MOUNT_B3,2") (pintype "passive"))
    )
    (net (code "298") (name "unconnected-(SHIFT_0-SER-Pad14)") (class "Default")
      (node (ref "SHIFT_0") (pin "14") (pinfunction "SER_14") (pintype "input"))
    )
    (net (code "299") (name "unconnected-(SHIFT_31-QH*-Pad9)") (class "Default")
      (node (ref "SHIFT_31") (pin "9") (pinfunction "QH*_9") (pintype "tri_state"))
    )
  )
)
